# MEM_MUX_2W_1.net
KiCad netlist of a schematic drawn in EAGLE
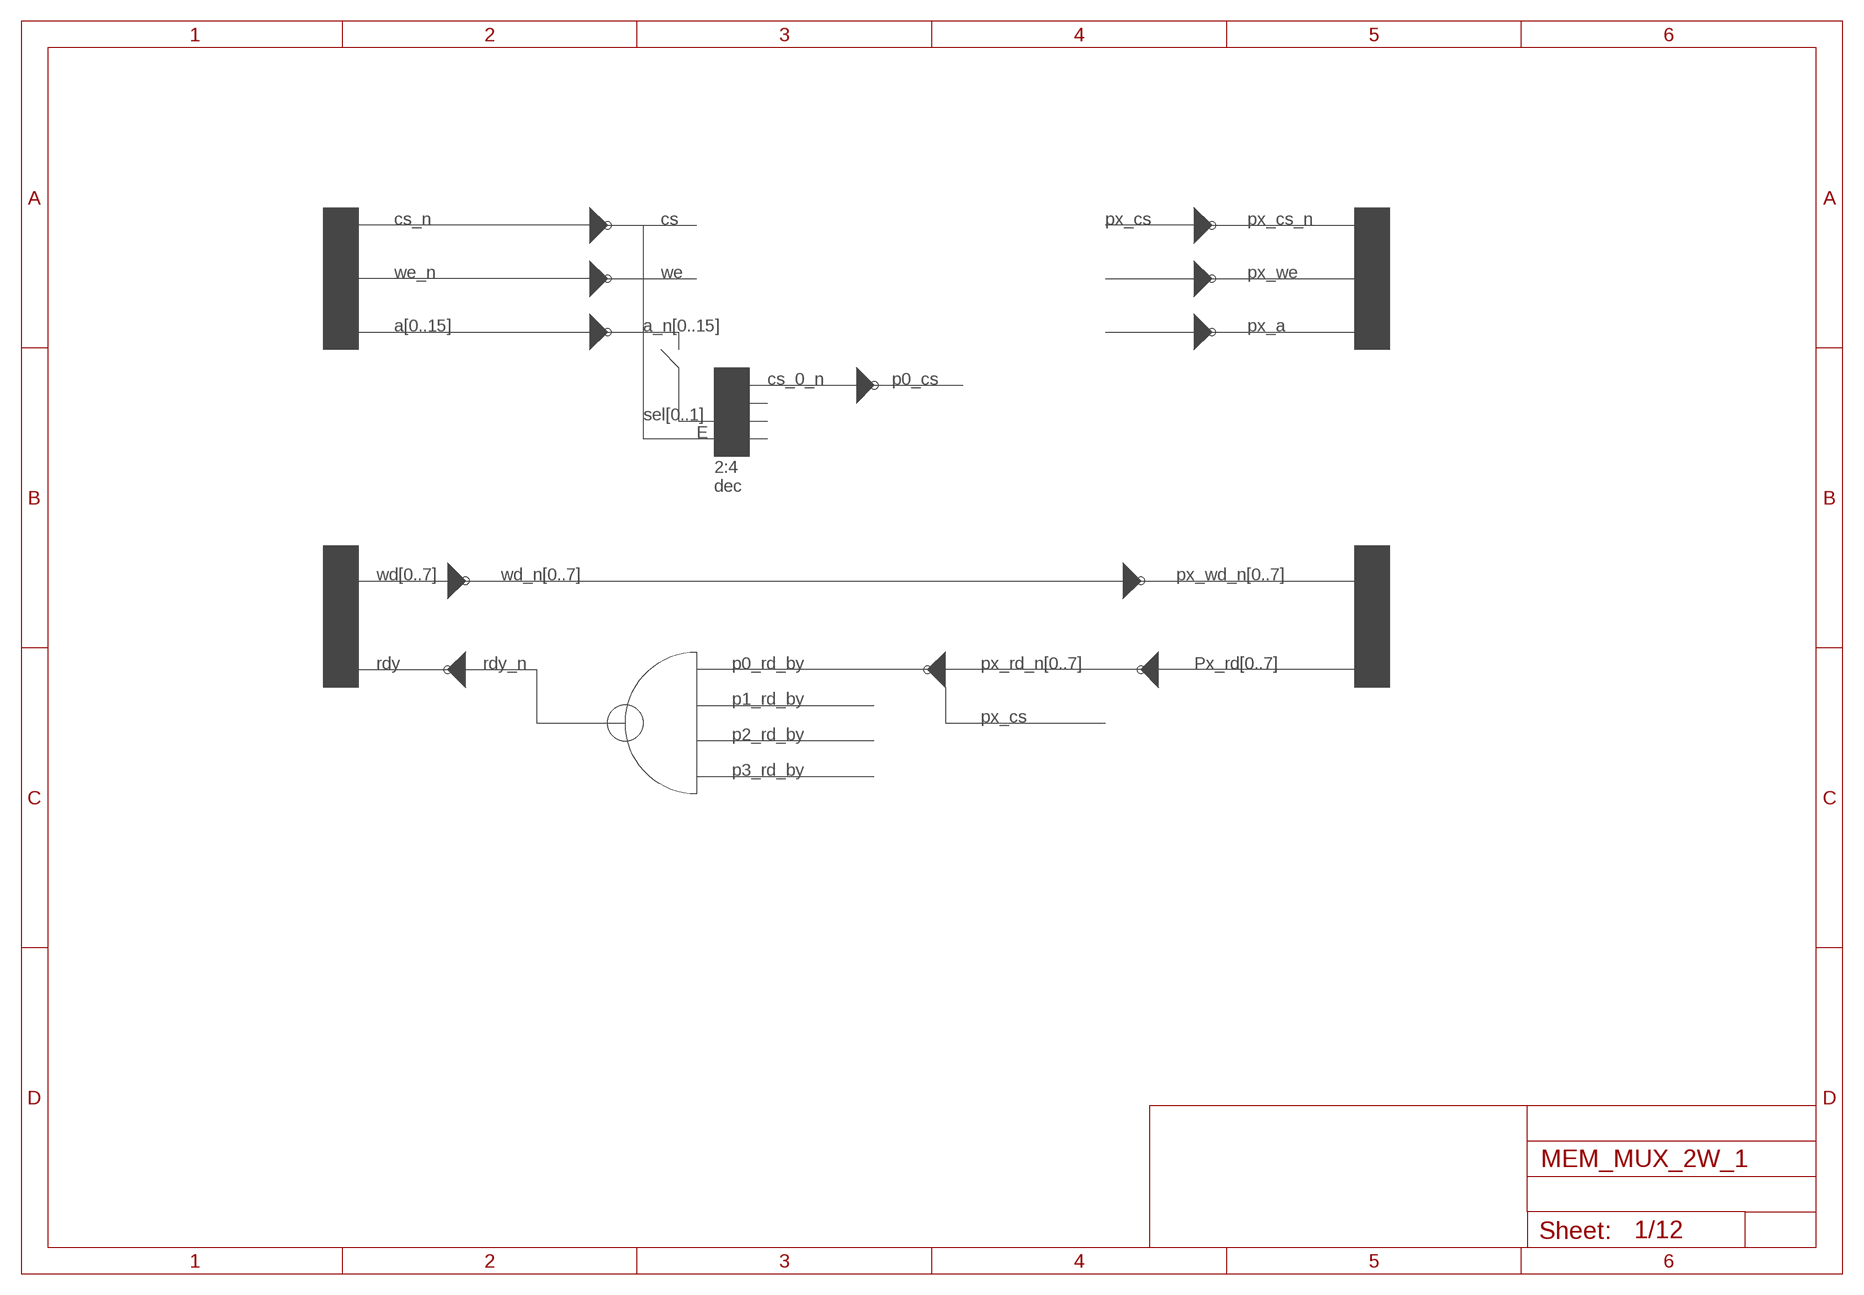
[diagram p0: schematic, sheet 1]
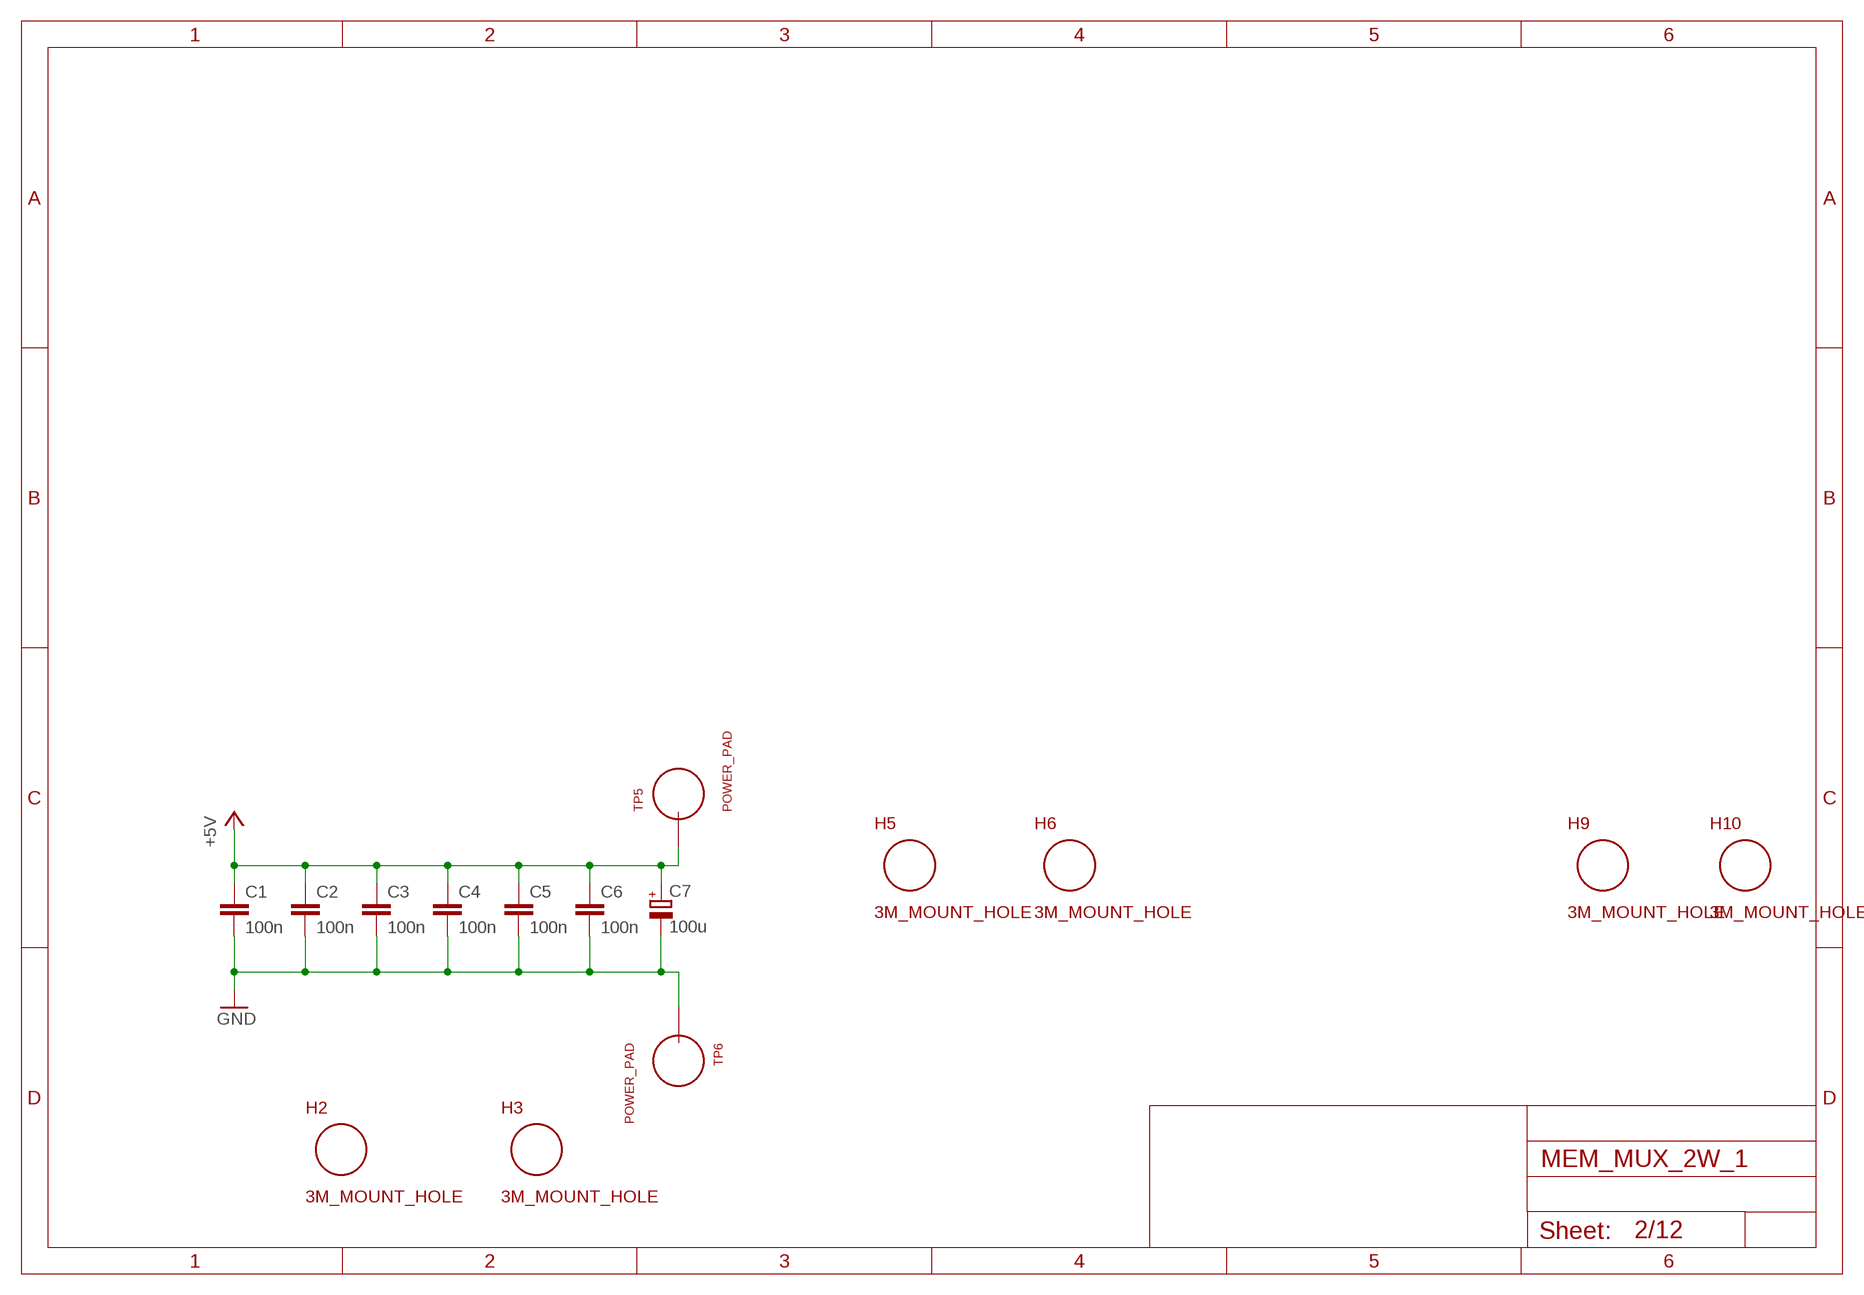
[diagram p1: schematic, sheet 2]
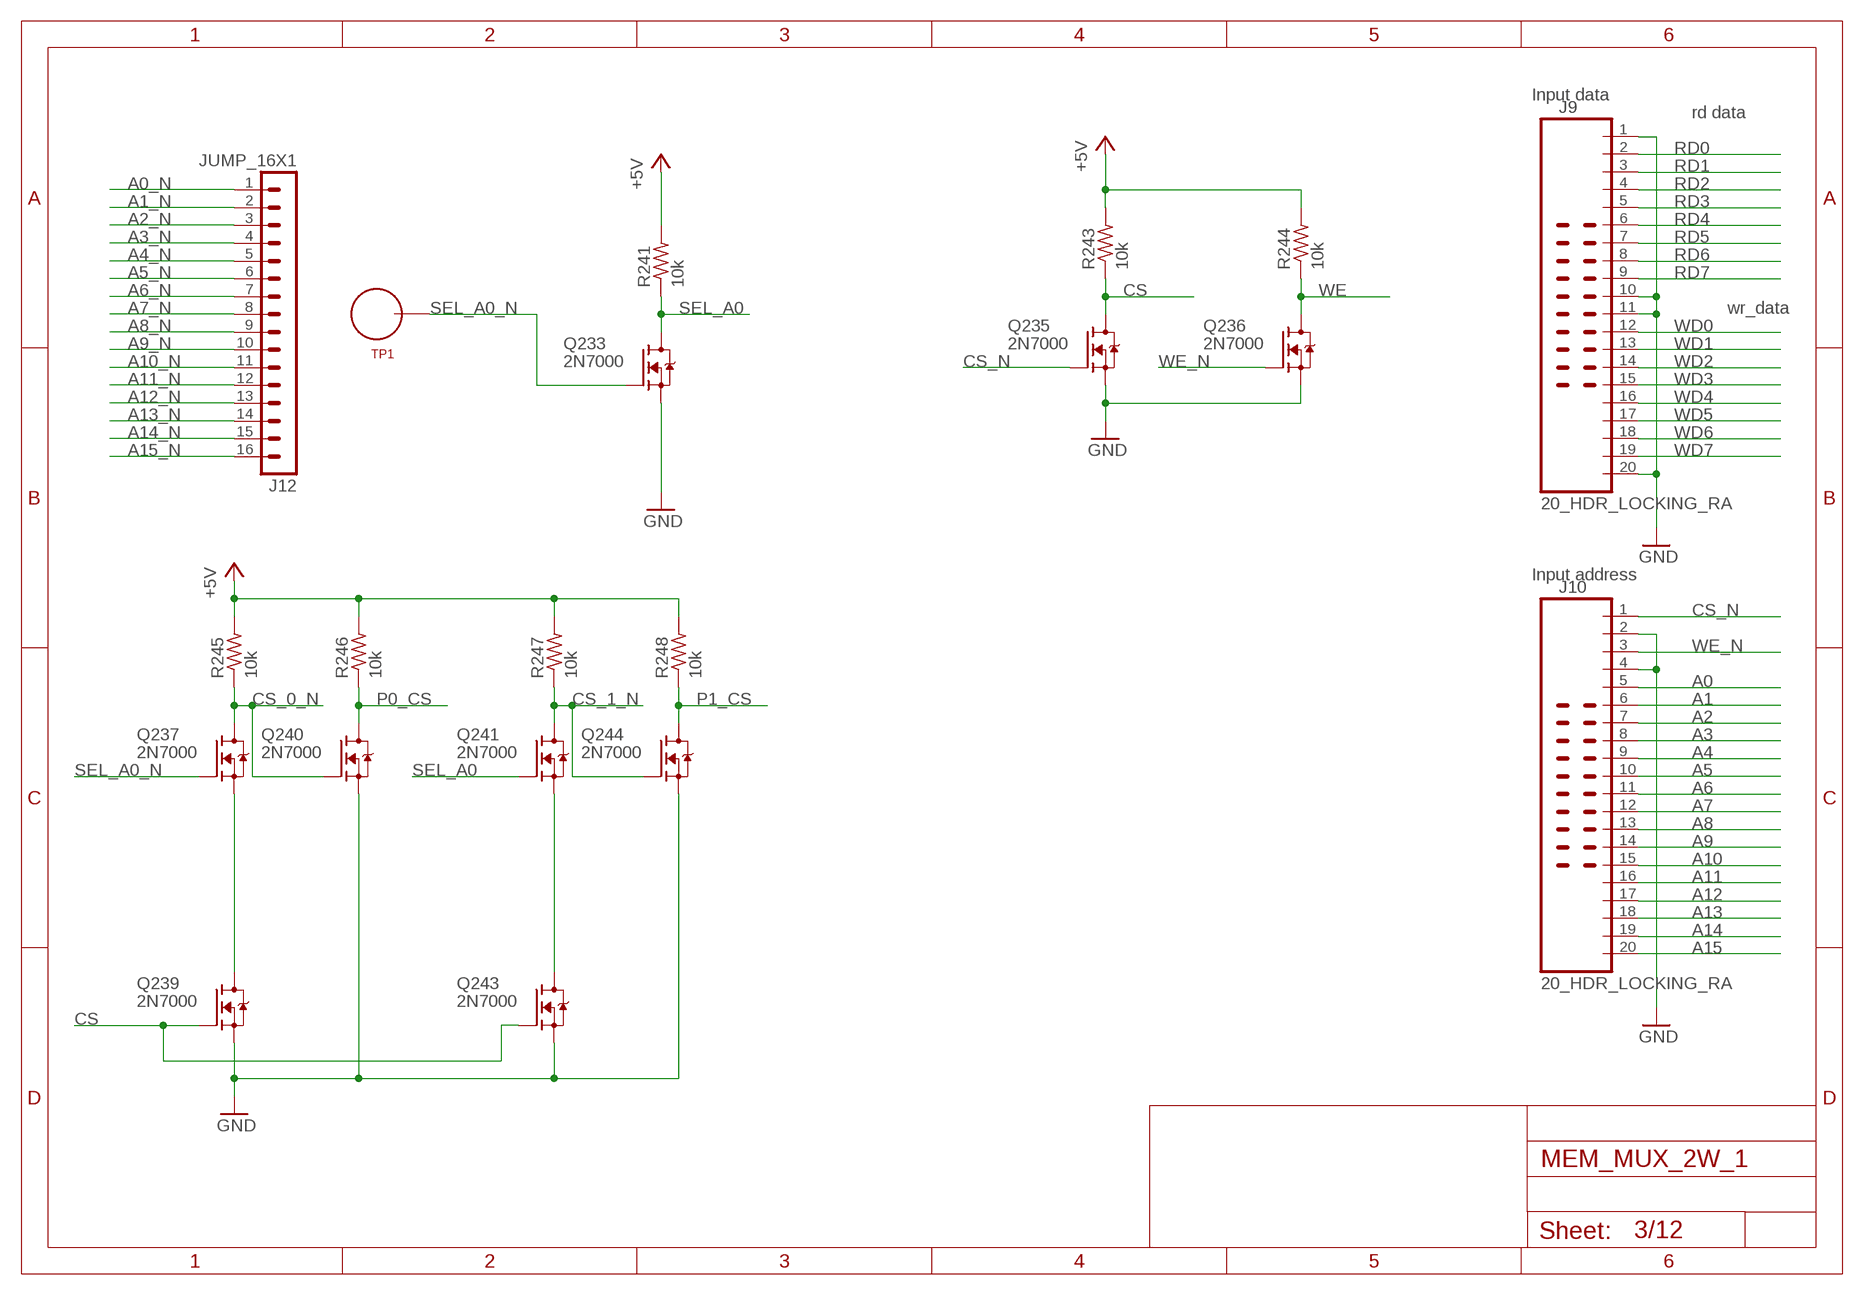
[diagram p2: schematic, sheet 3]
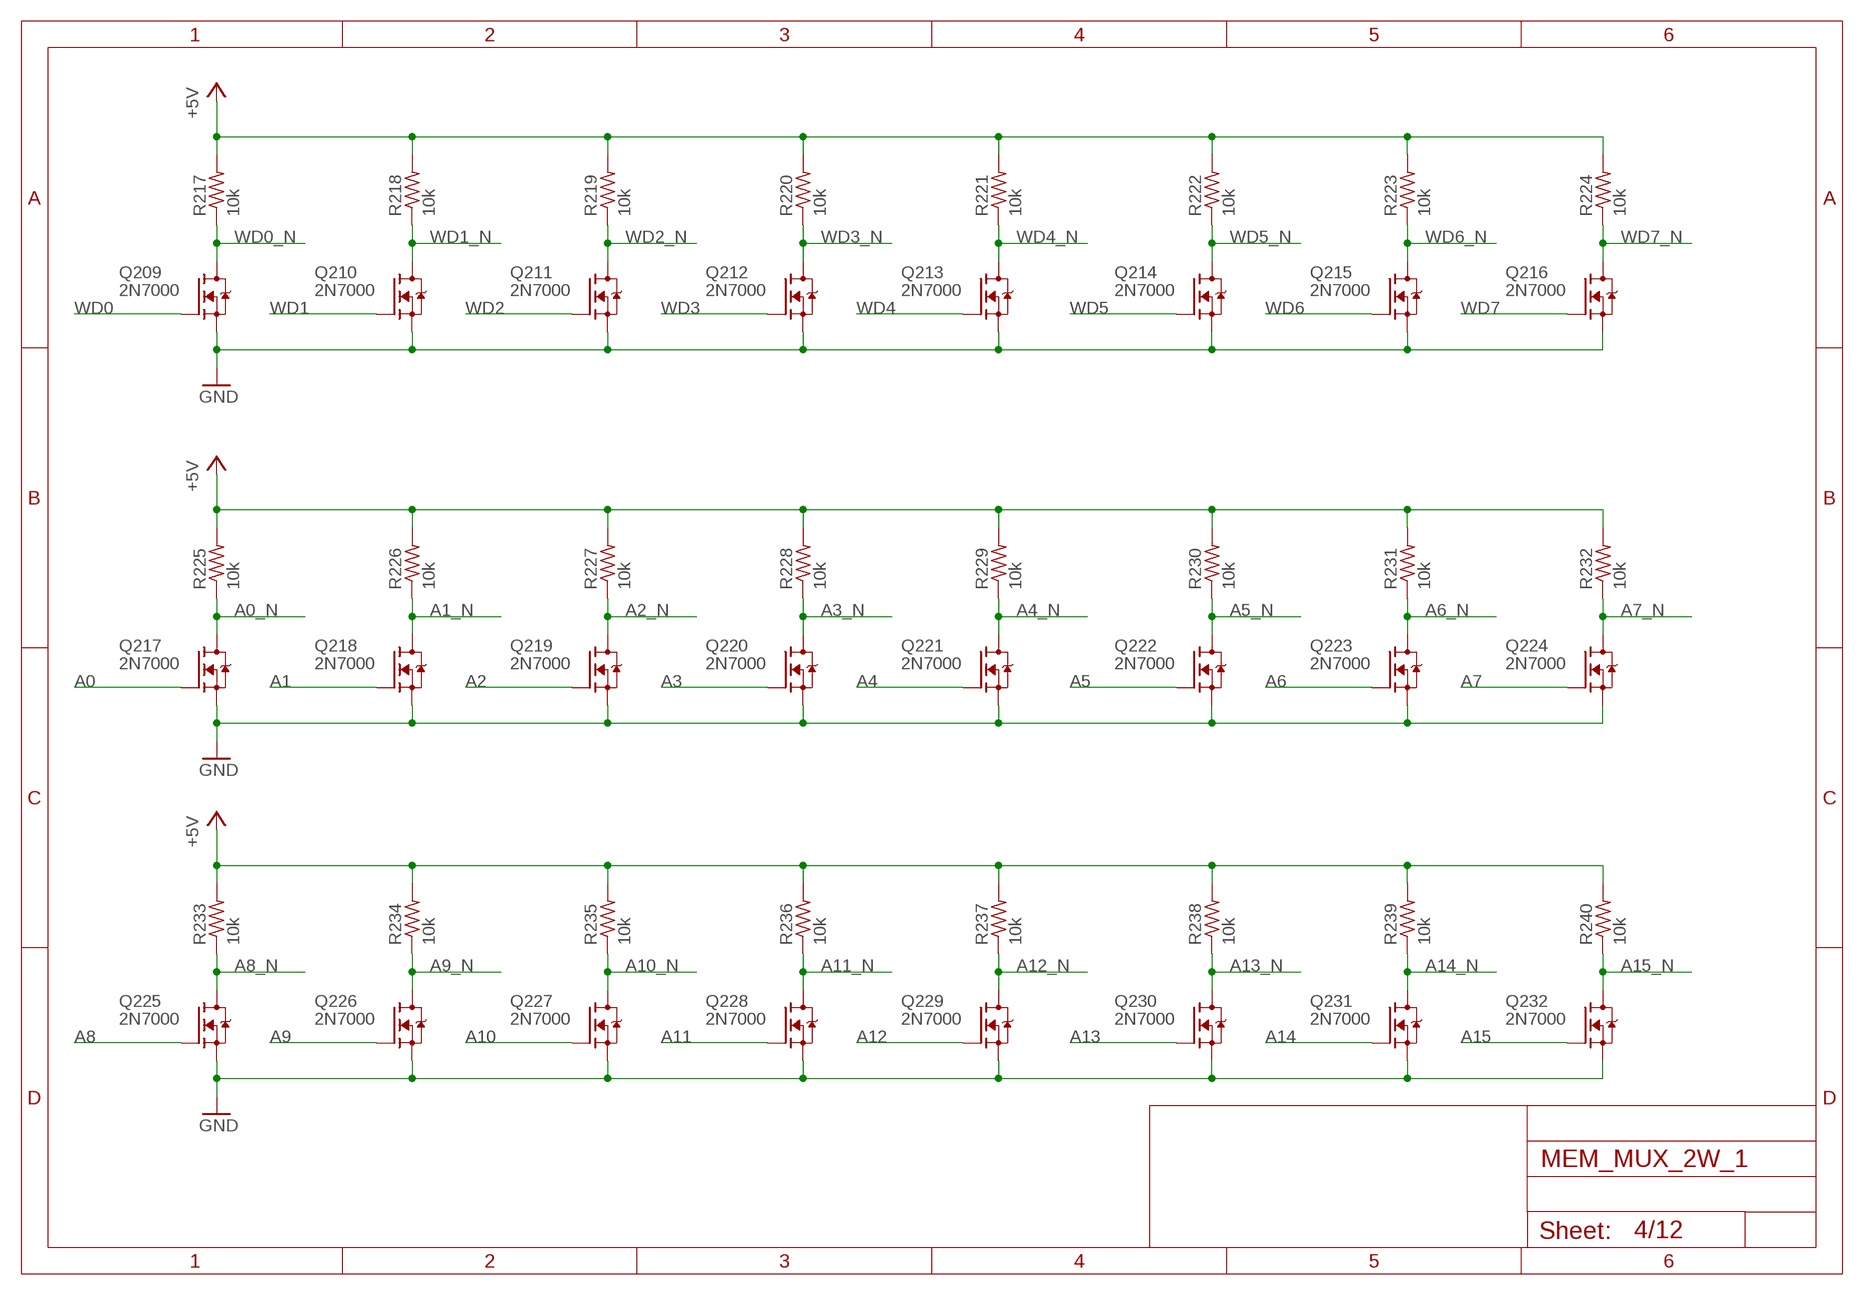
[diagram p3: schematic, sheet 4]
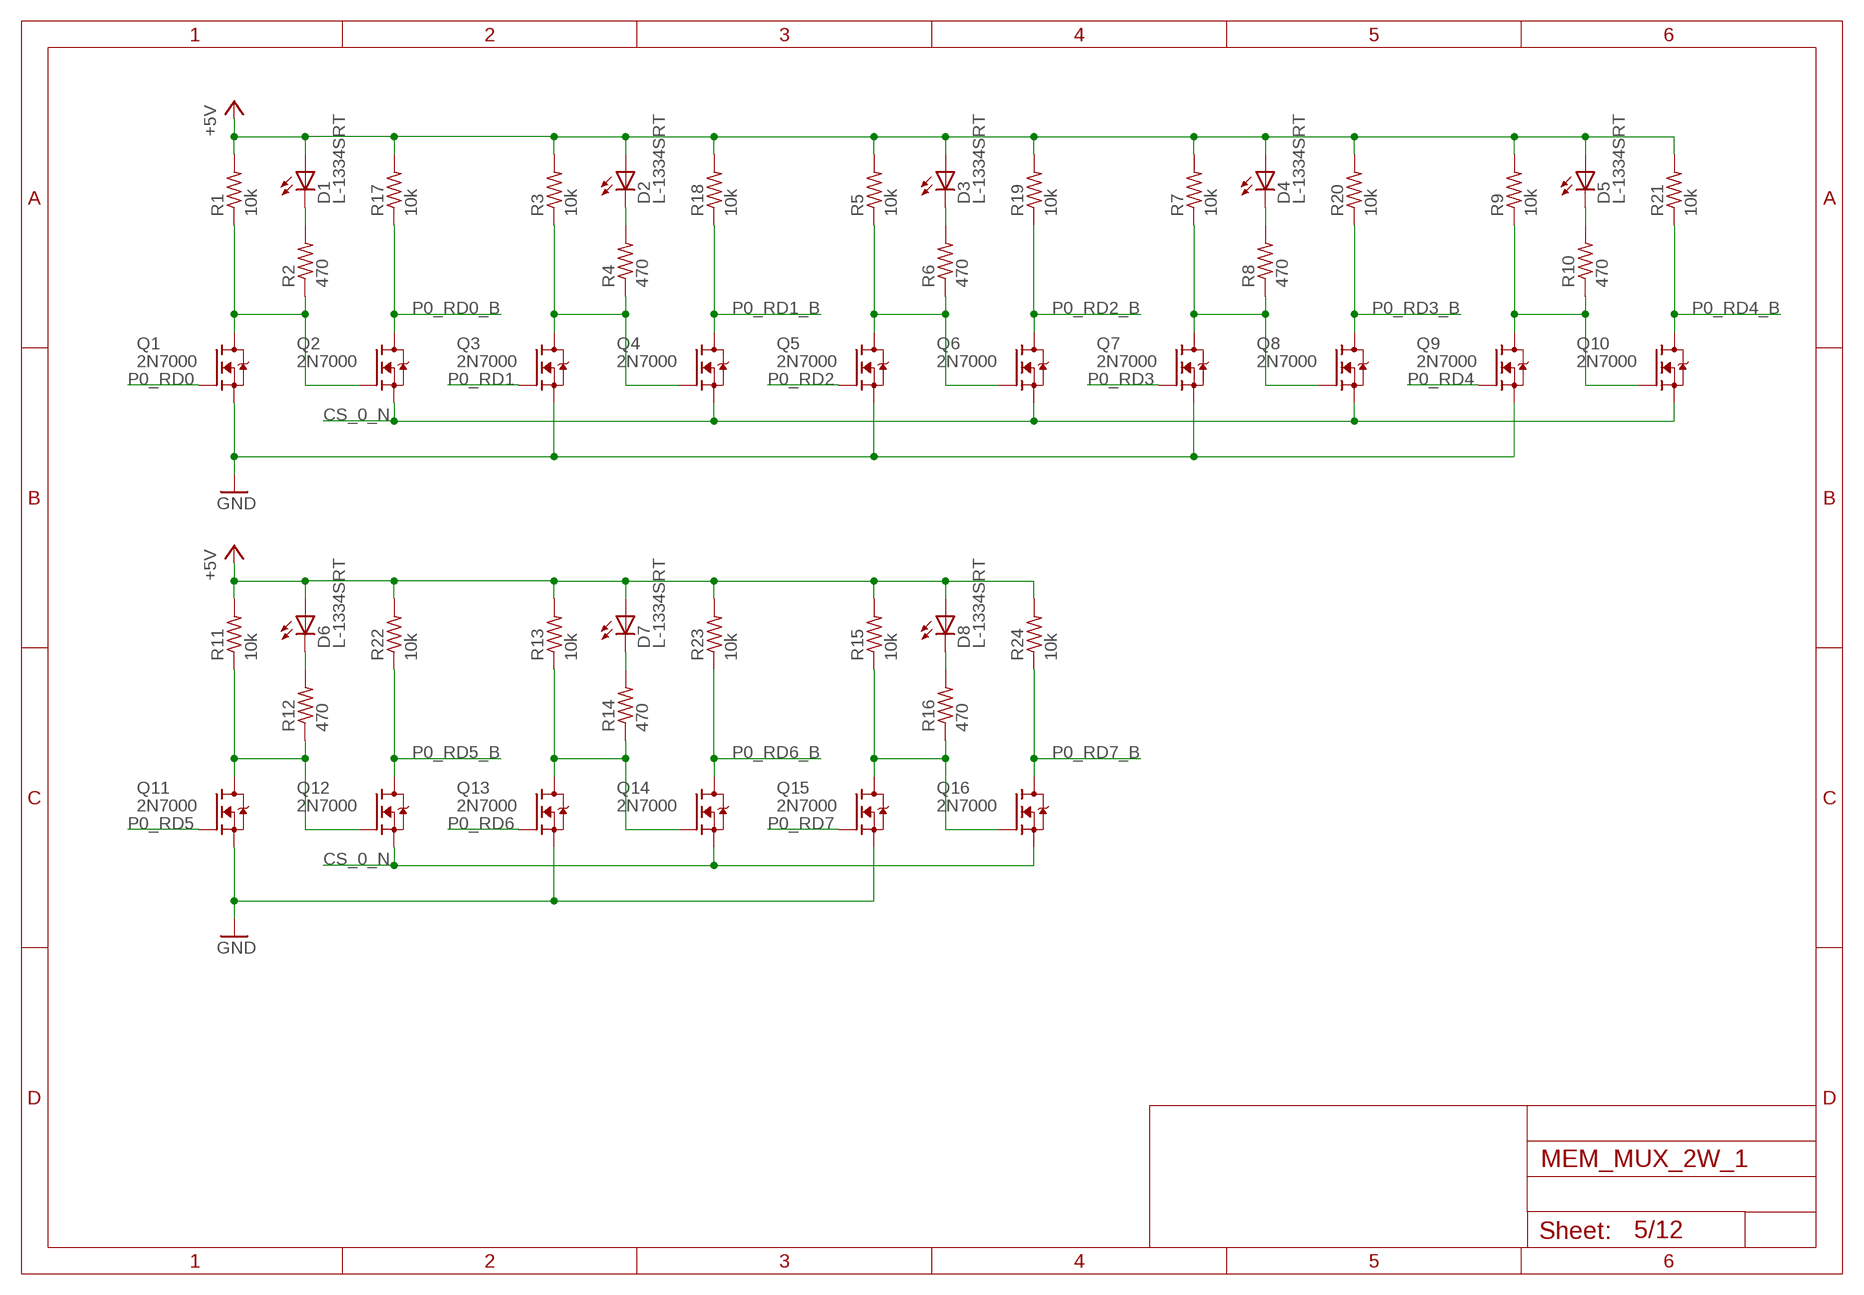
[diagram p4: schematic, sheet 5]
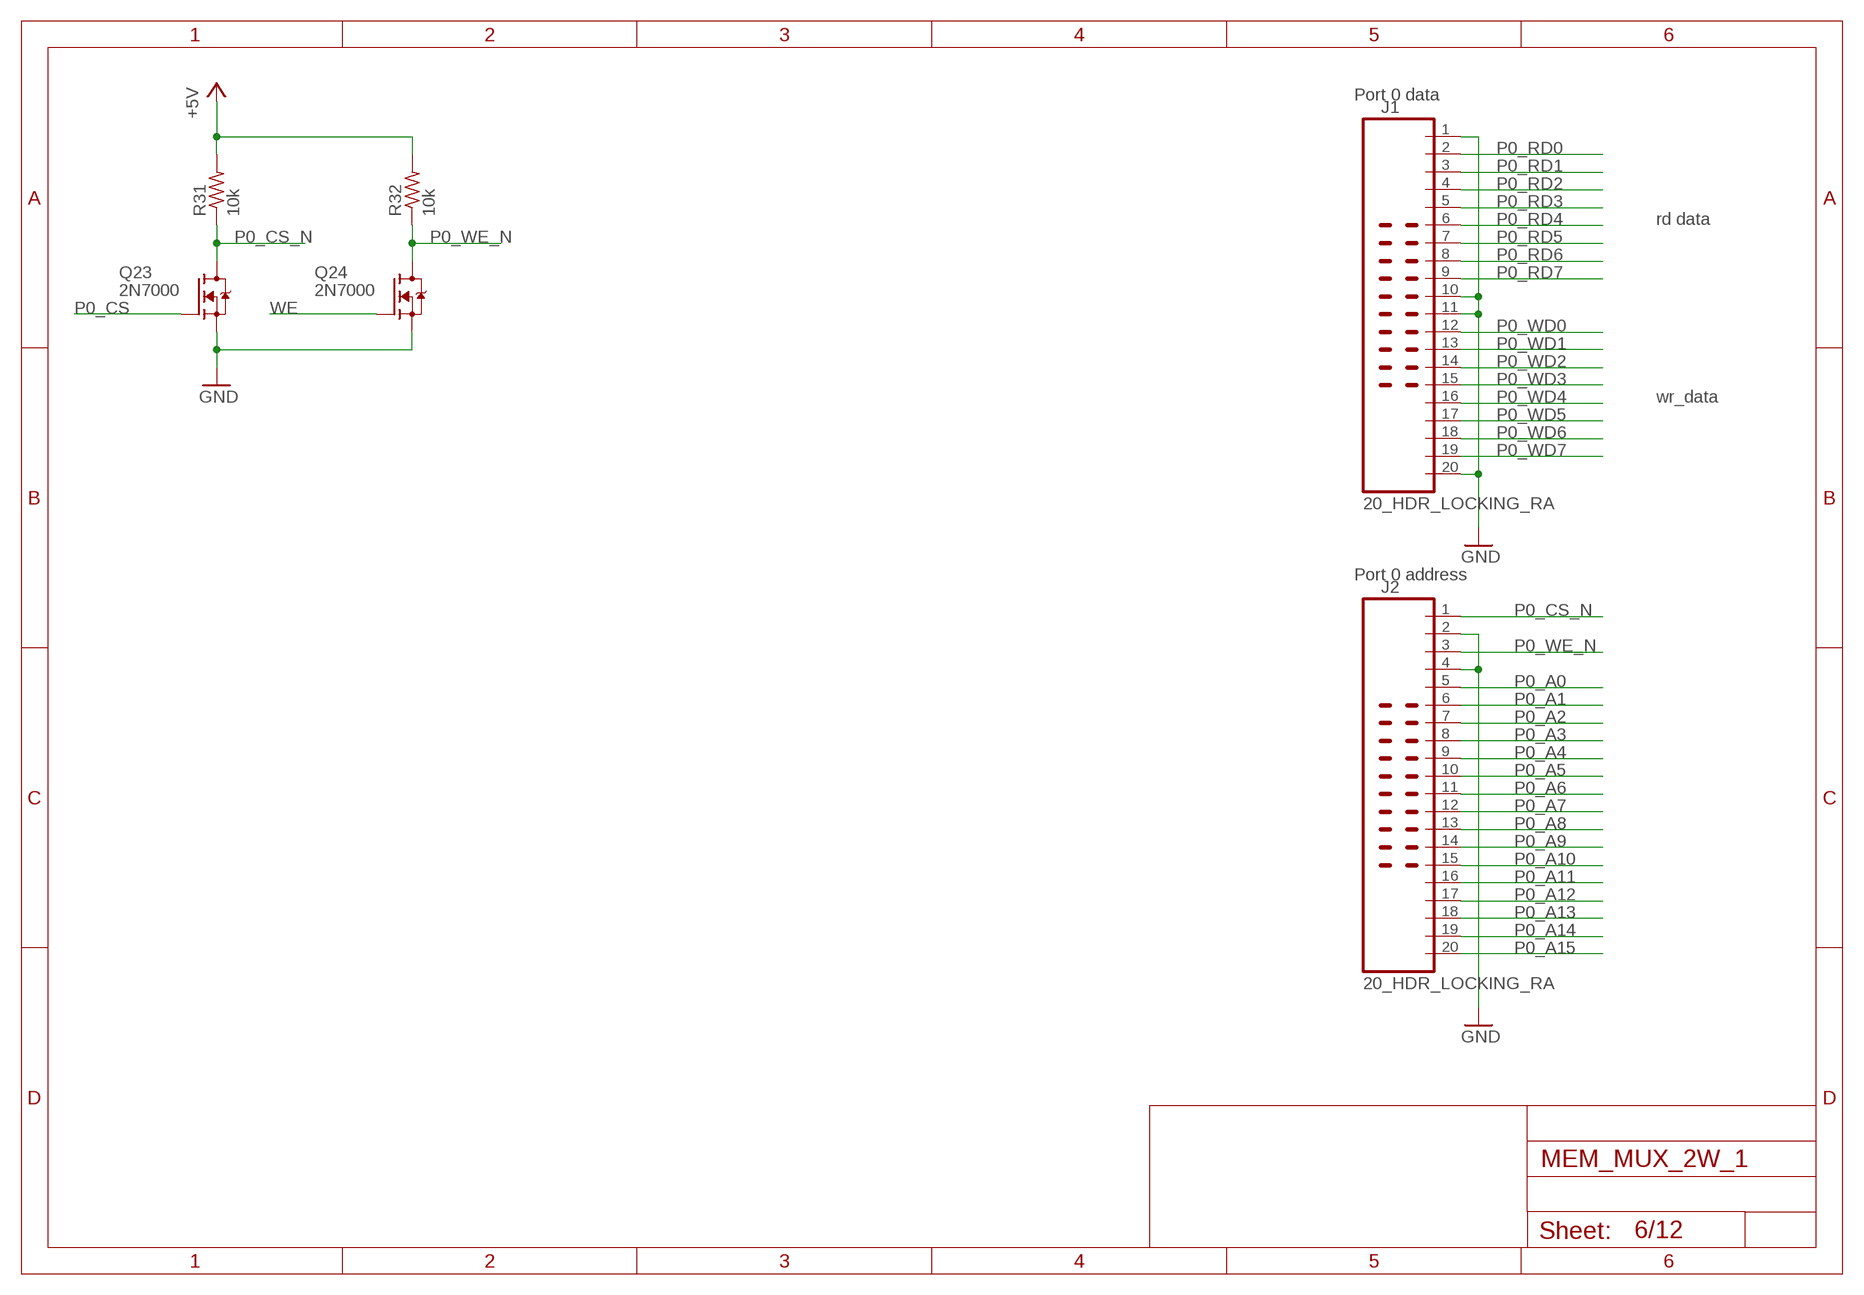
[diagram p5: schematic, sheet 6]
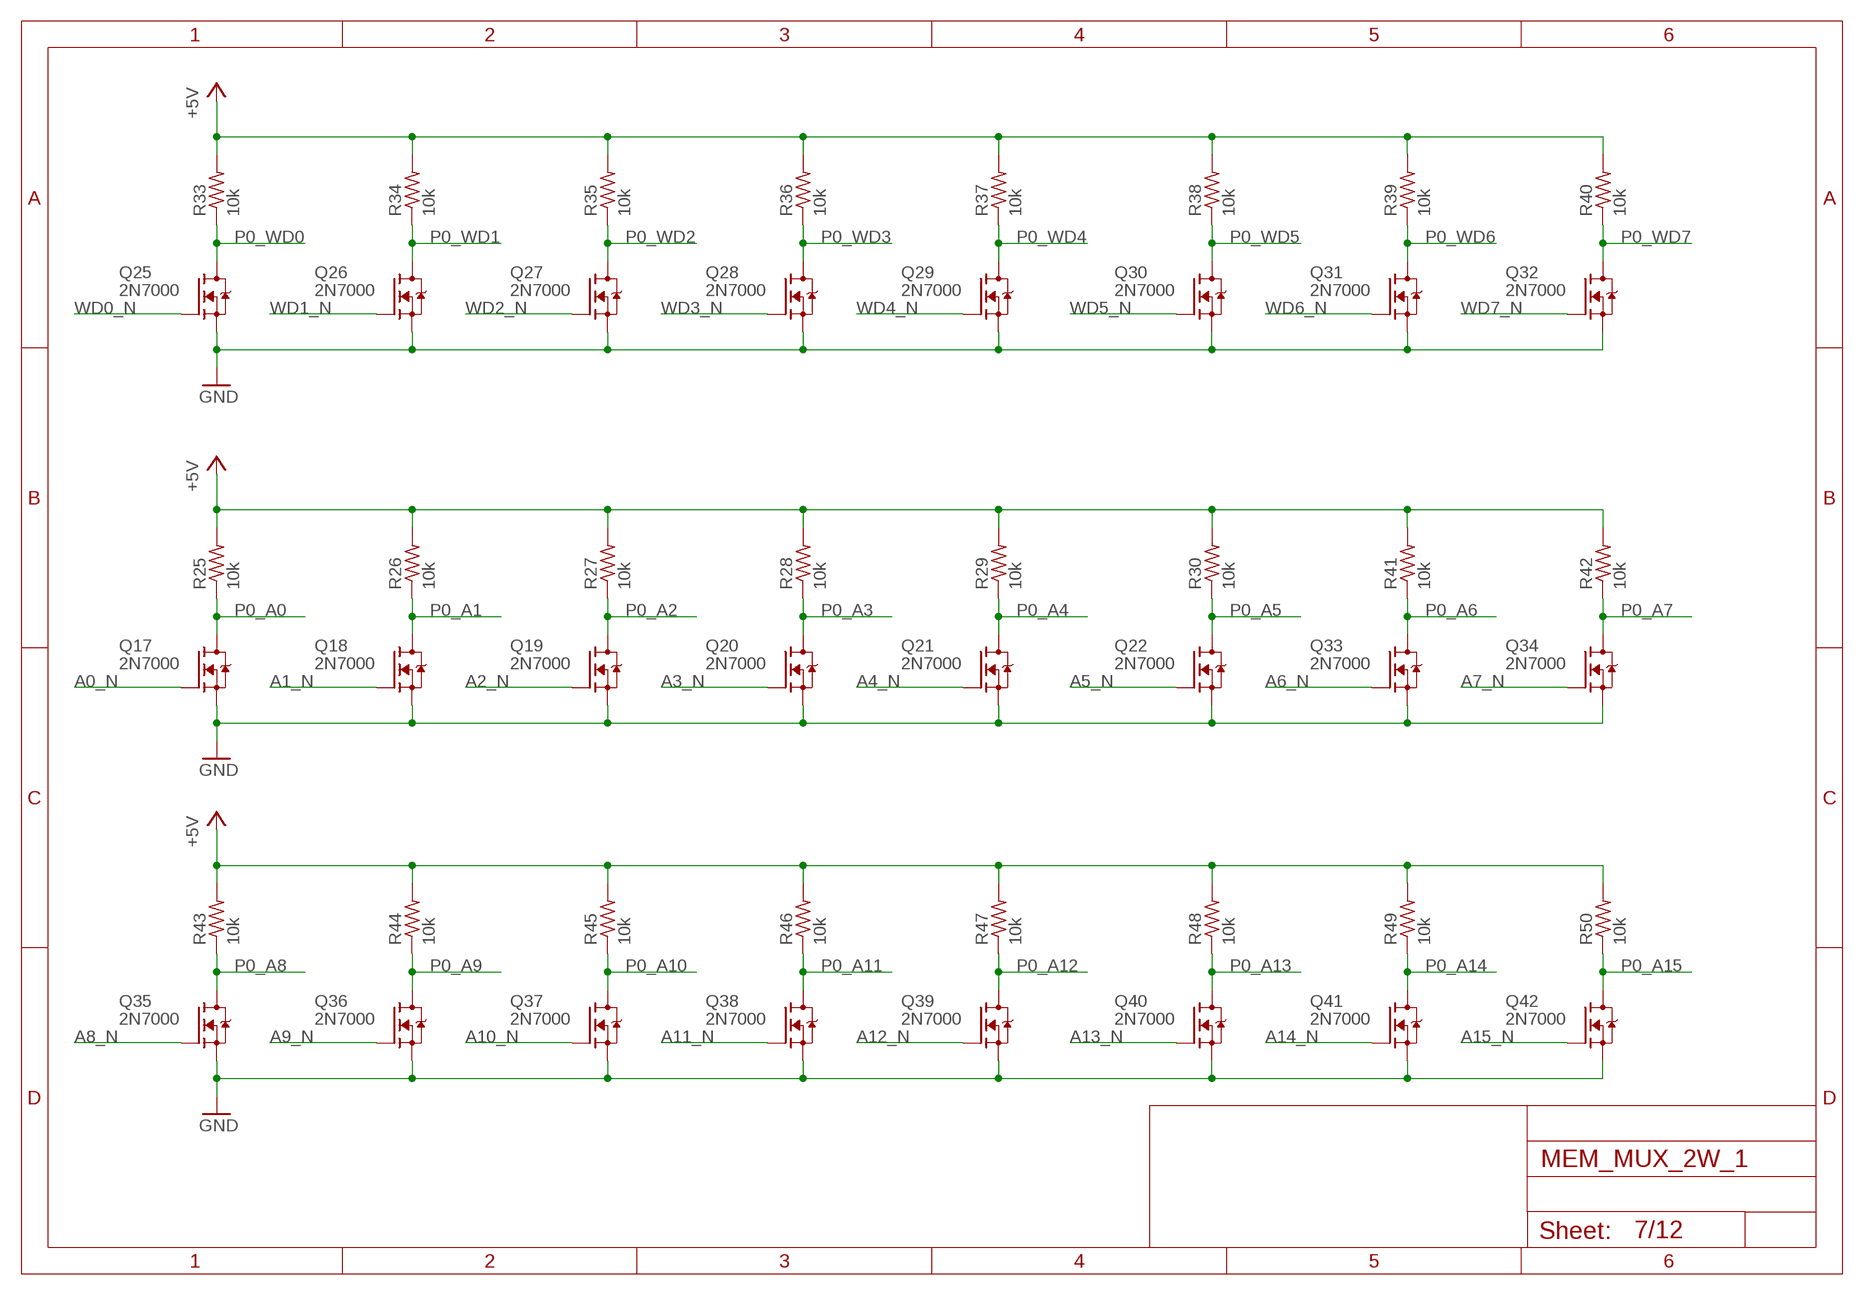
[diagram p6: schematic, sheet 7]
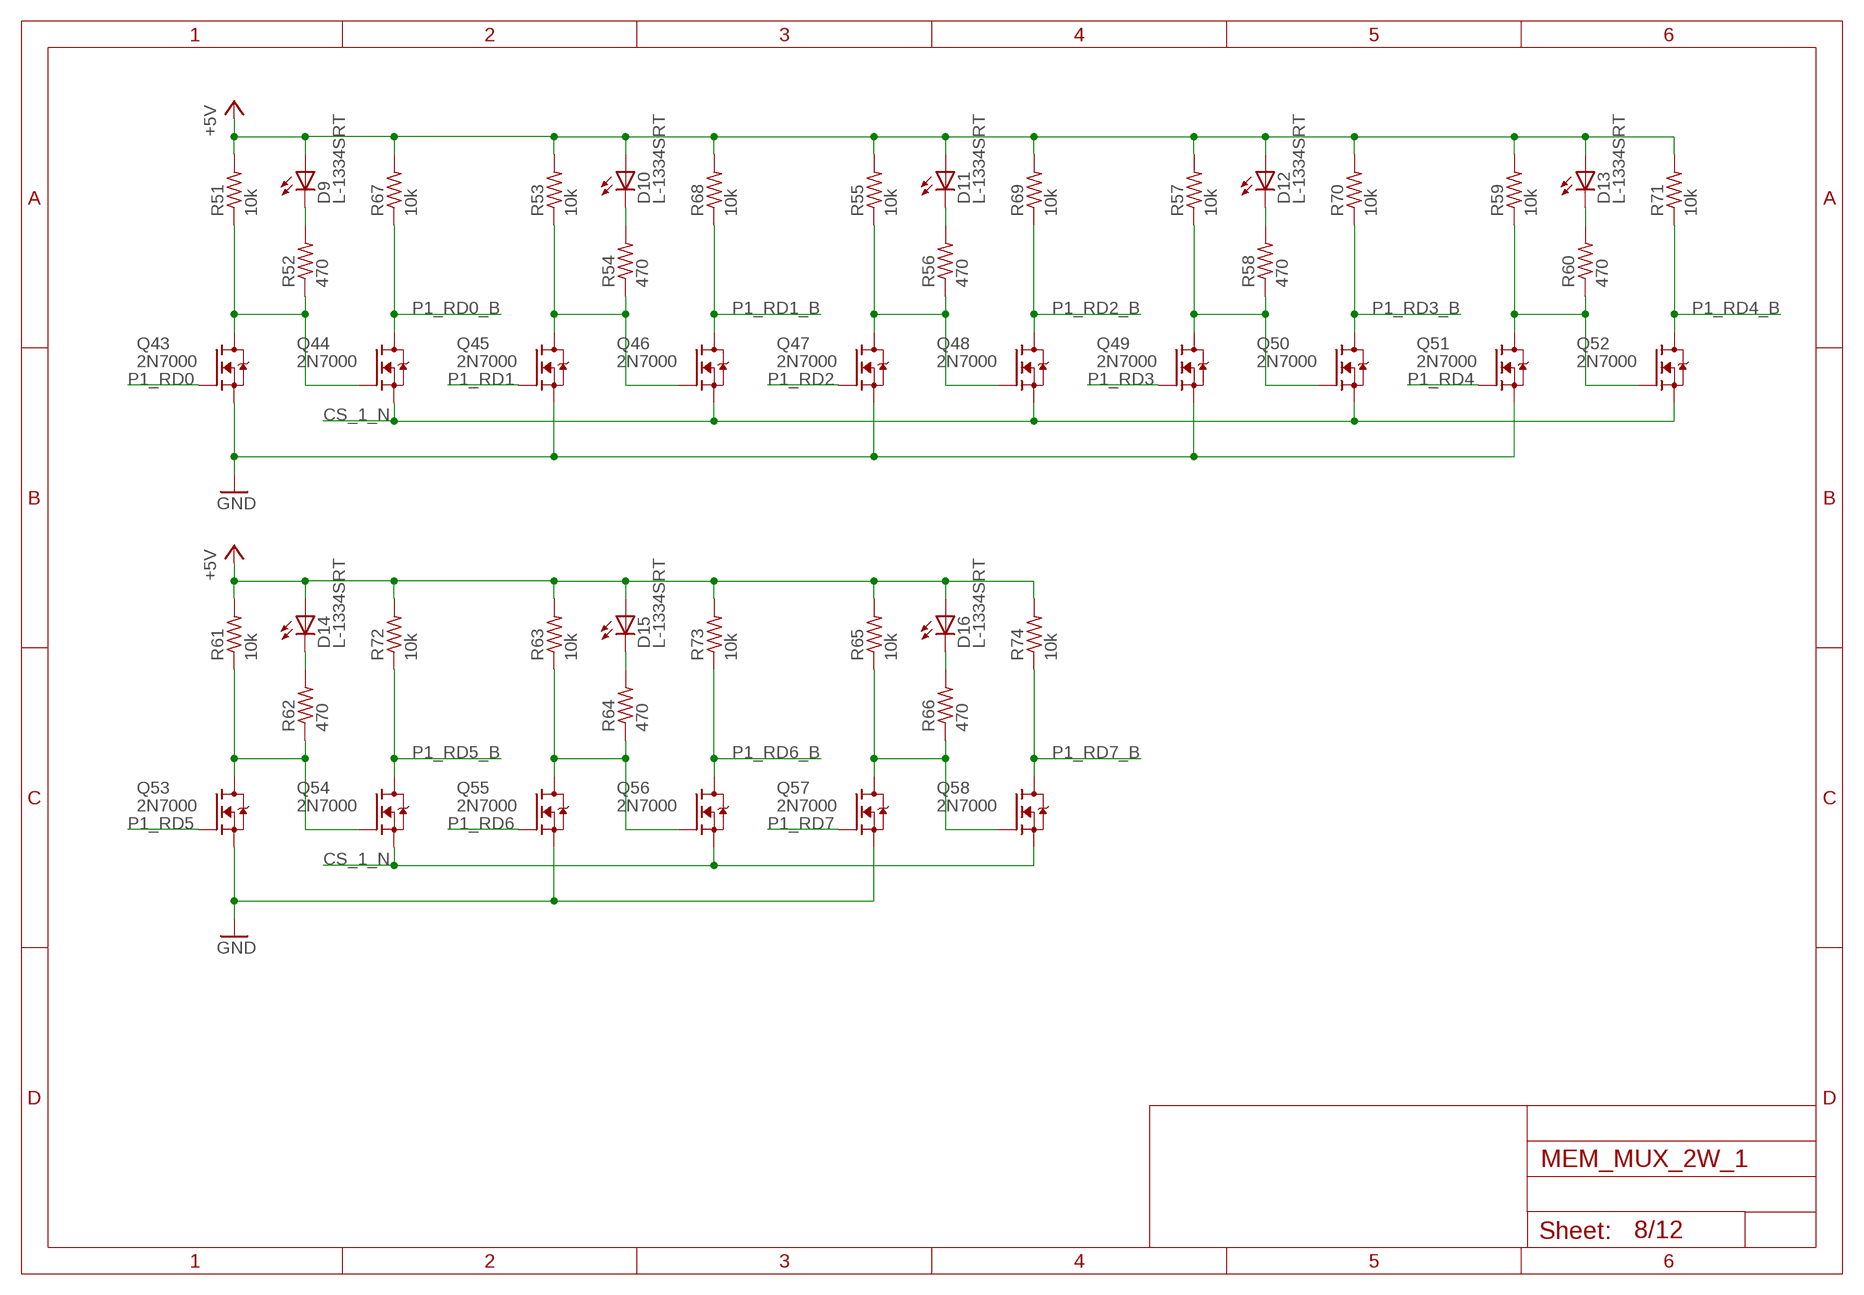
[diagram p7: schematic, sheet 8]
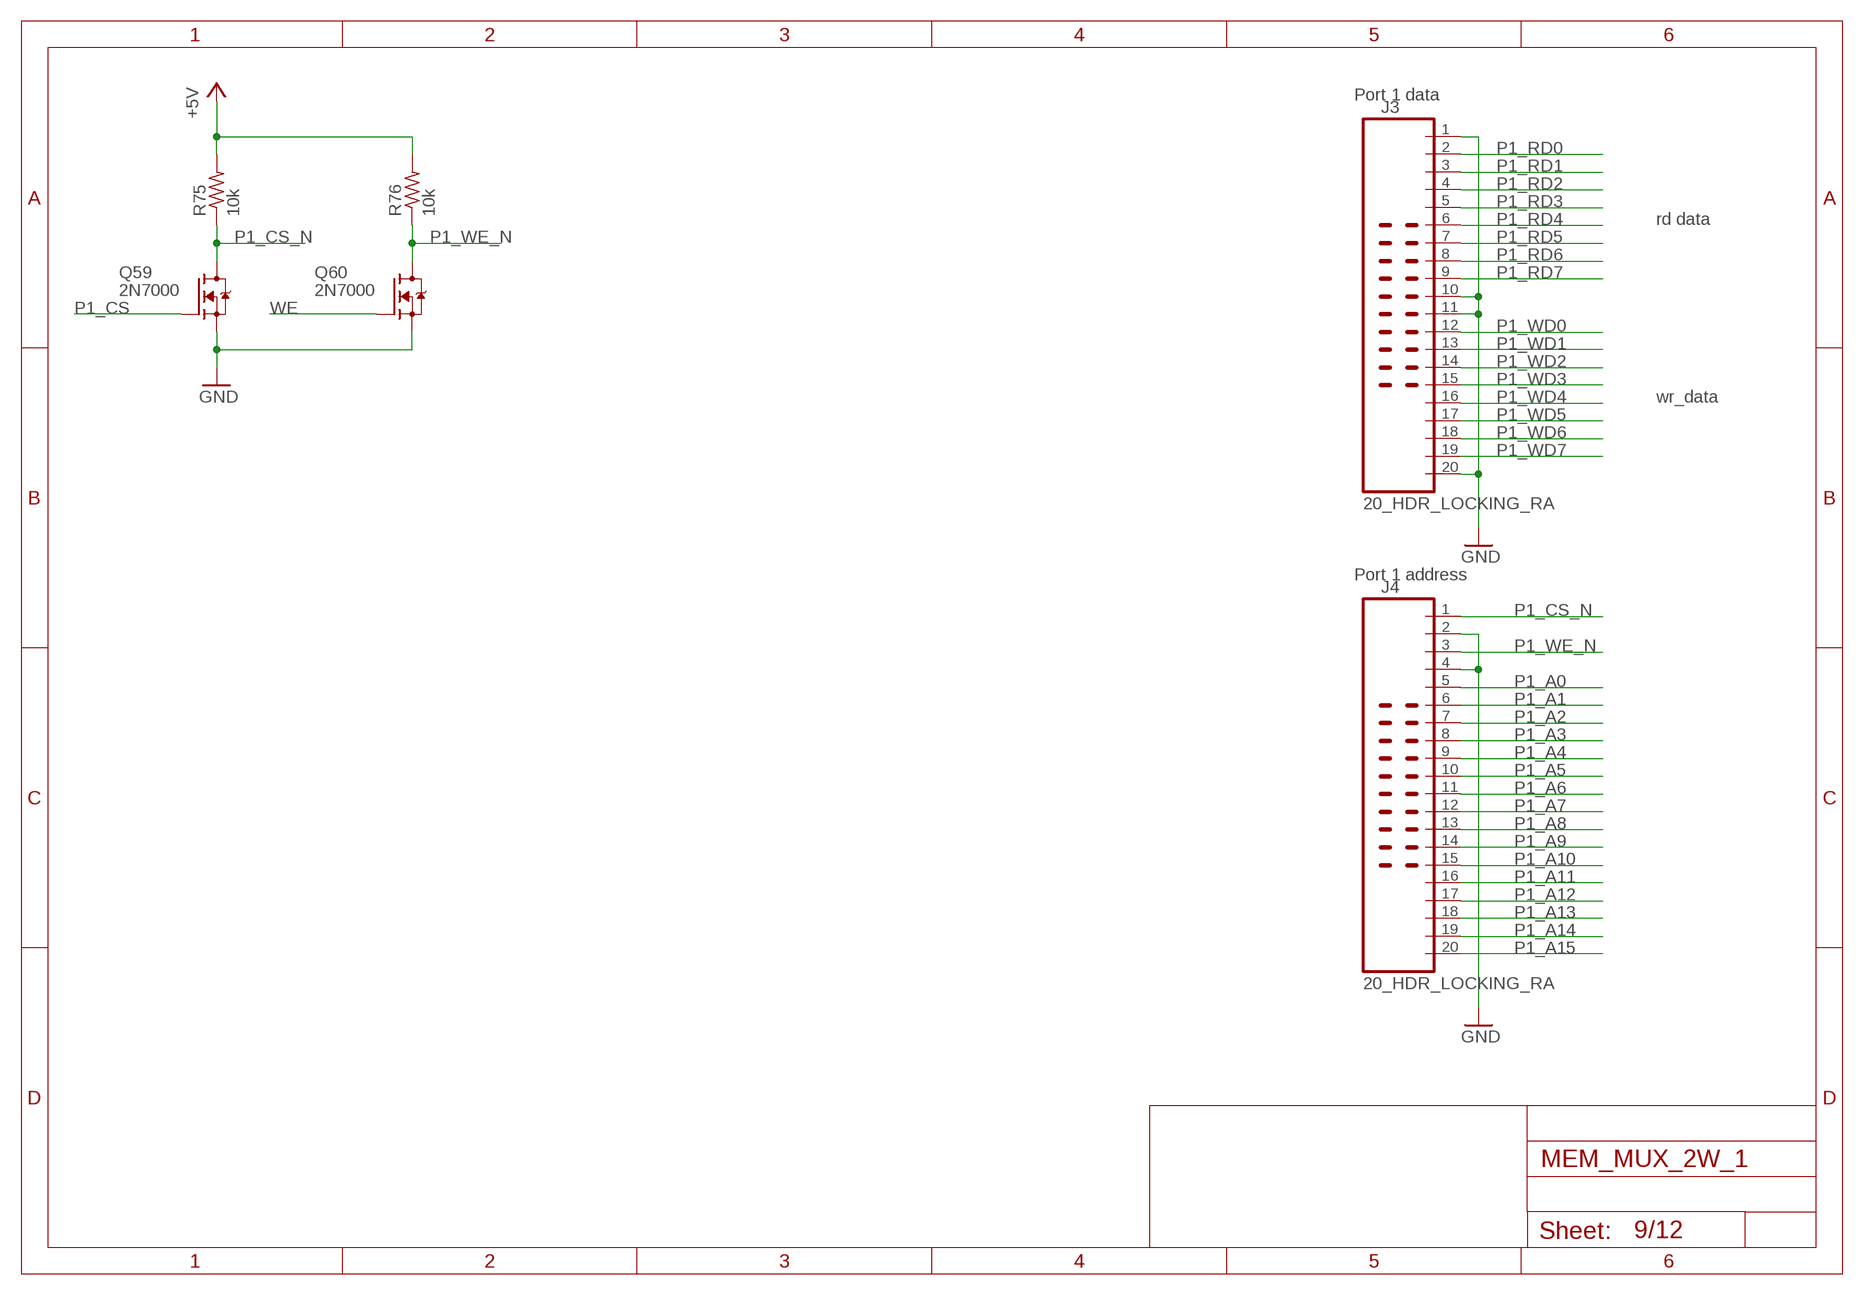
[diagram p8: schematic, sheet 9]
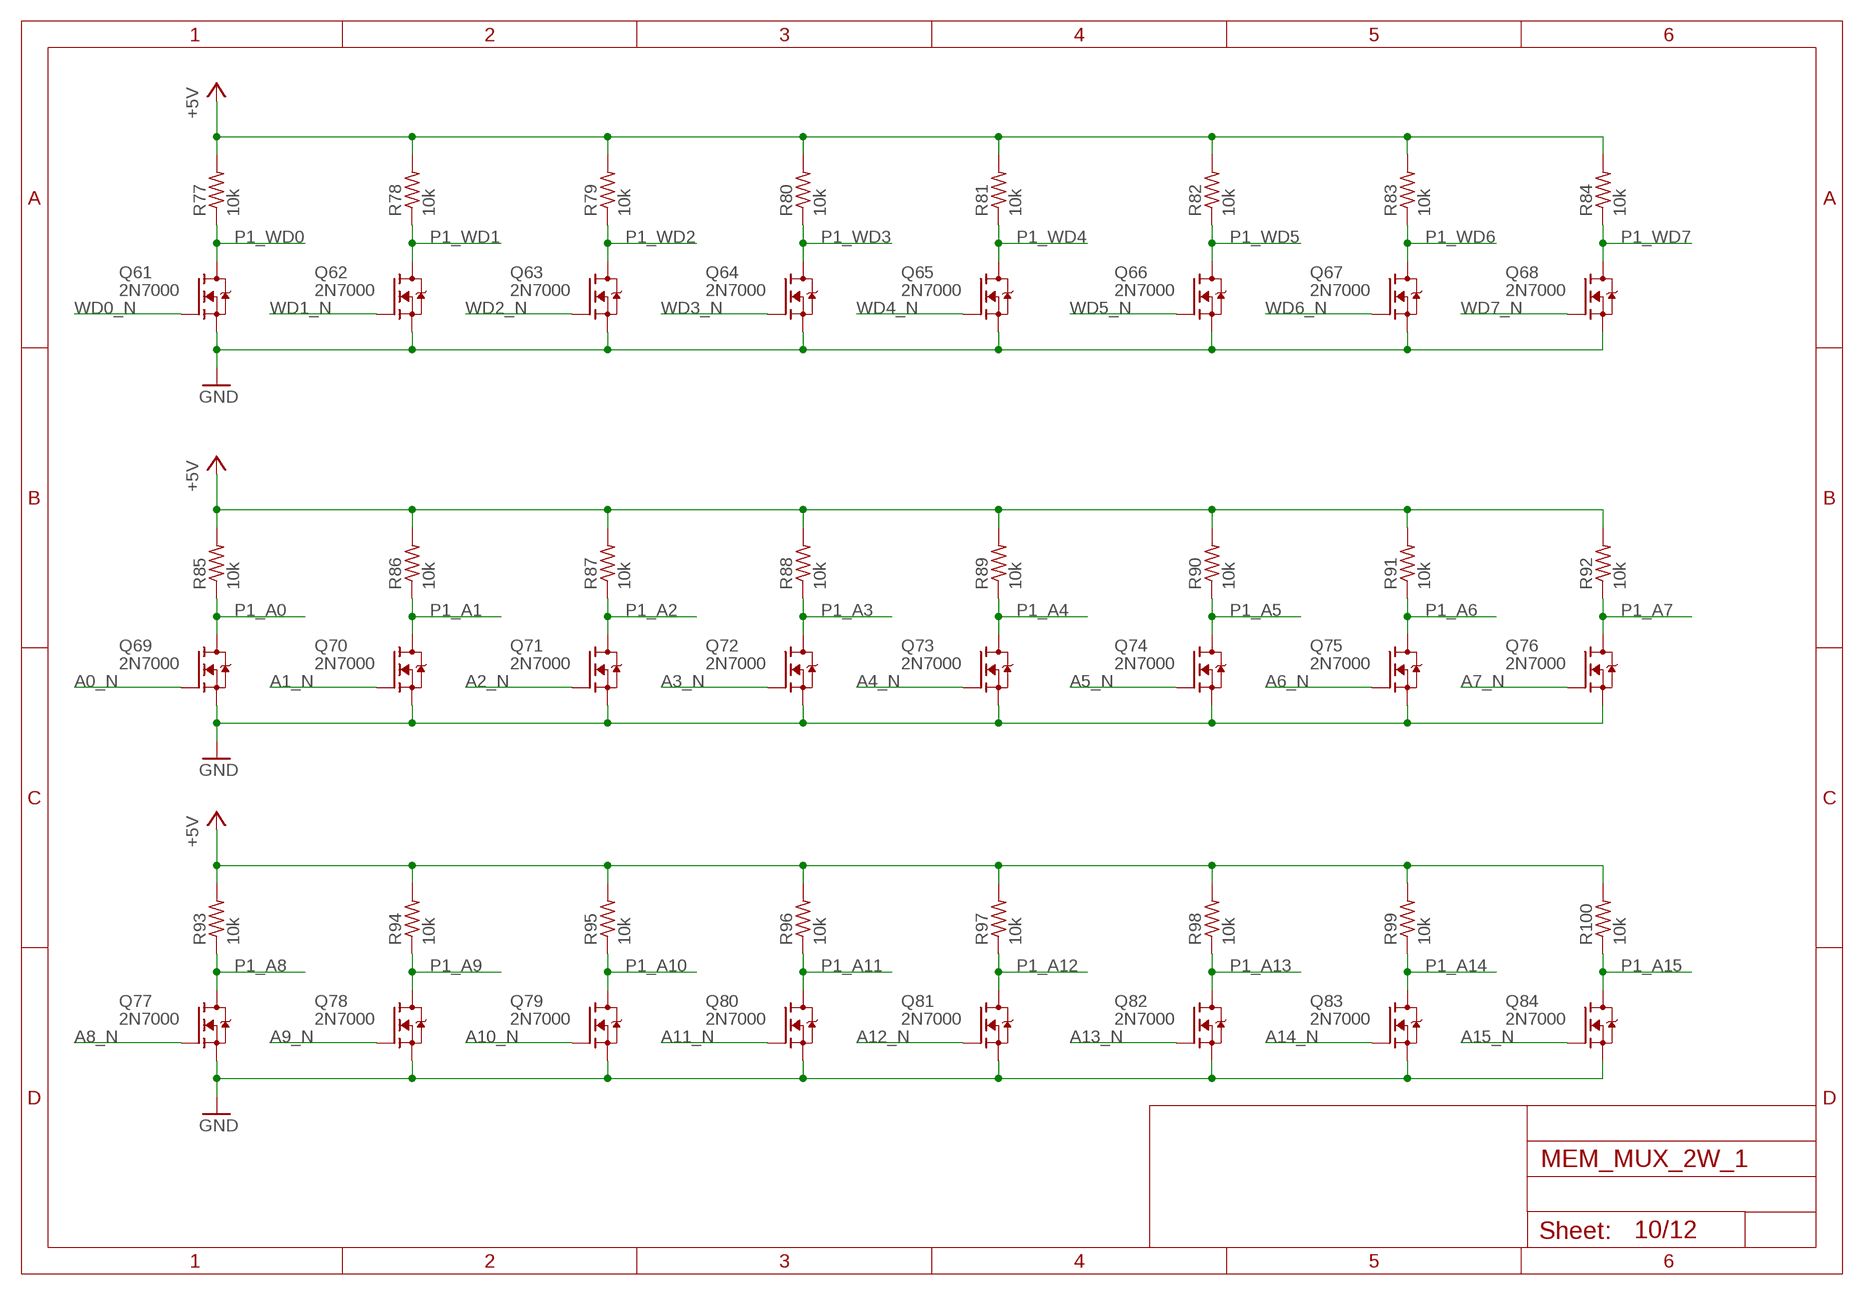
[diagram p9: schematic, sheet 10]
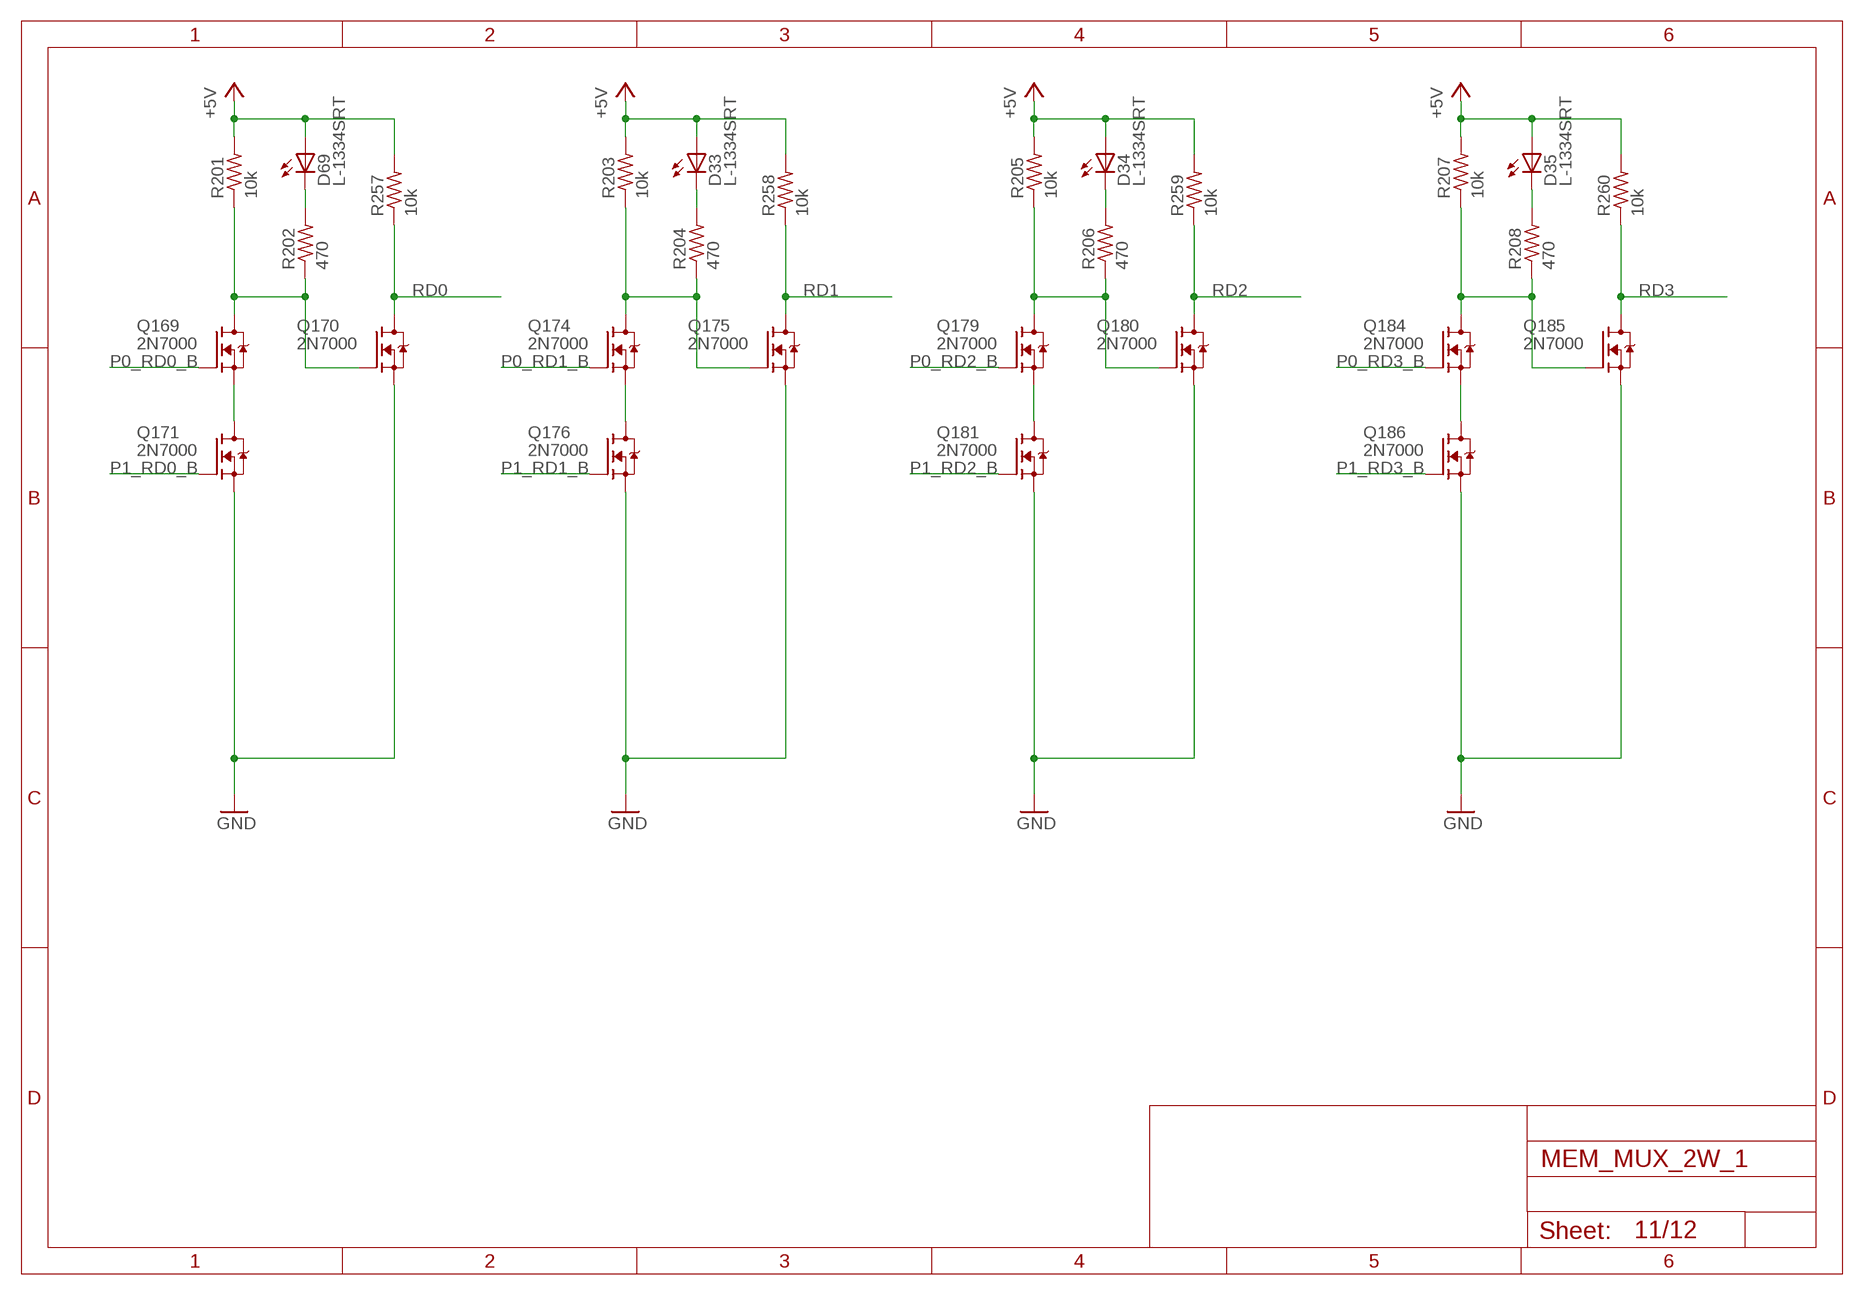
[diagram p10: schematic, sheet 11]
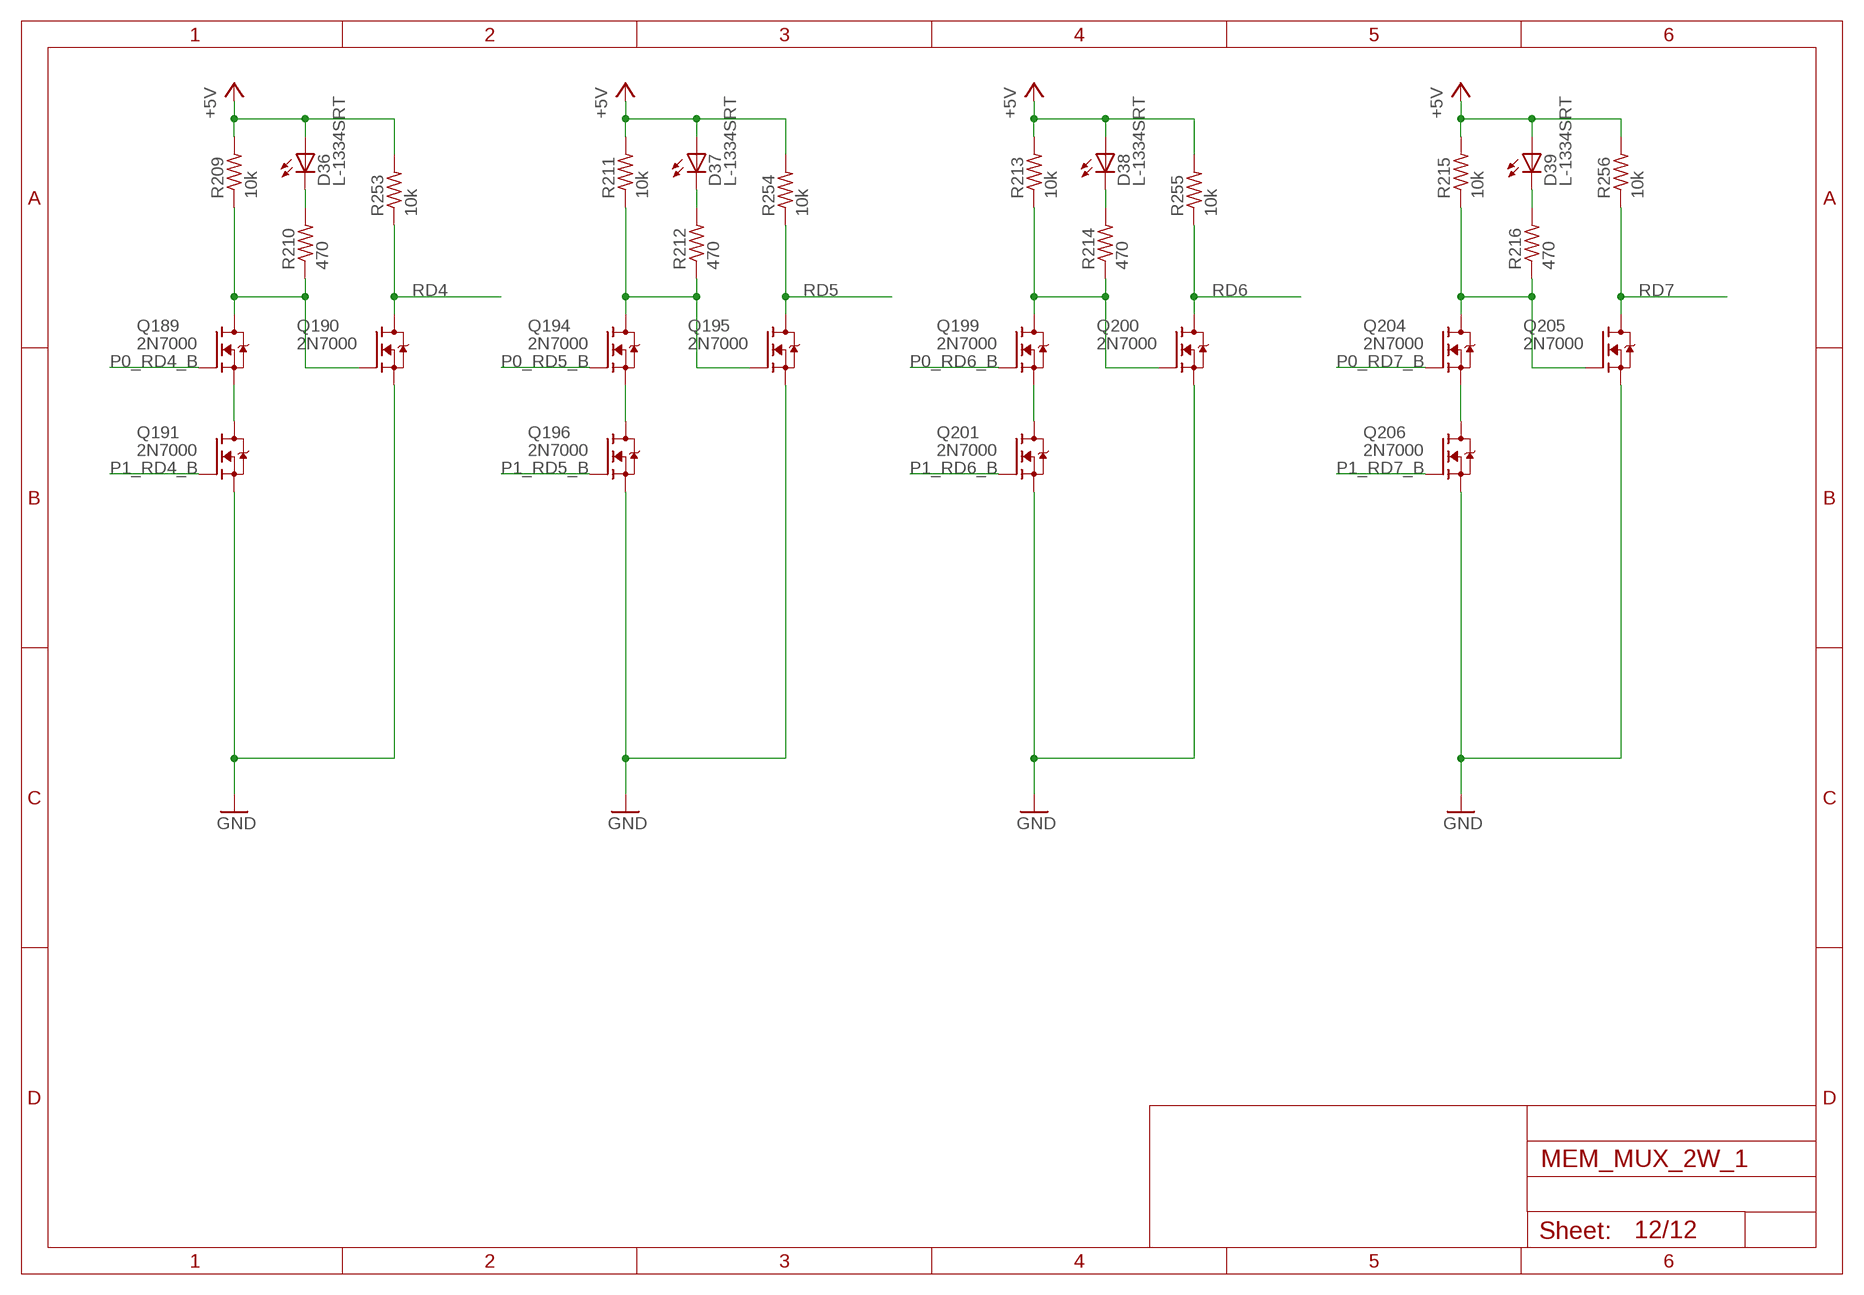
[diagram p11: schematic, sheet 12]

(export (version "E")
  (design (tool "Eeschema 10.0.6"))
  (components
    (comp (ref "Q61")
      (value "2N7000")
      (footprint "eagle-import:TO92-DGS")
      (libsource (lib "eagle-import") (part "2N7000"))
    )
    (comp (ref "Q62")
      (value "2N7000")
      (footprint "eagle-import:TO92-DGS")
      (libsource (lib "eagle-import") (part "2N7000"))
    )
    (comp (ref "Q63")
      (value "2N7000")
      (footprint "eagle-import:TO92-DGS")
      (libsource (lib "eagle-import") (part "2N7000"))
    )
    (comp (ref "Q64")
      (value "2N7000")
      (footprint "eagle-import:TO92-DGS")
      (libsource (lib "eagle-import") (part "2N7000"))
    )
    (comp (ref "Q65")
      (value "2N7000")
      (footprint "eagle-import:TO92-DGS")
      (libsource (lib "eagle-import") (part "2N7000"))
    )
    (comp (ref "Q66")
      (value "2N7000")
      (footprint "eagle-import:TO92-DGS")
      (libsource (lib "eagle-import") (part "2N7000"))
    )
    (comp (ref "Q67")
      (value "2N7000")
      (footprint "eagle-import:TO92-DGS")
      (libsource (lib "eagle-import") (part "2N7000"))
    )
    (comp (ref "Q68")
      (value "2N7000")
      (footprint "eagle-import:TO92-DGS")
      (libsource (lib "eagle-import") (part "2N7000"))
    )
    (comp (ref "Q69")
      (value "2N7000")
      (footprint "eagle-import:TO92-DGS")
      (libsource (lib "eagle-import") (part "2N7000"))
    )
    (comp (ref "Q70")
      (value "2N7000")
      (footprint "eagle-import:TO92-DGS")
      (libsource (lib "eagle-import") (part "2N7000"))
    )
    (comp (ref "Q71")
      (value "2N7000")
      (footprint "eagle-import:TO92-DGS")
      (libsource (lib "eagle-import") (part "2N7000"))
    )
    (comp (ref "Q72")
      (value "2N7000")
      (footprint "eagle-import:TO92-DGS")
      (libsource (lib "eagle-import") (part "2N7000"))
    )
    (comp (ref "Q73")
      (value "2N7000")
      (footprint "eagle-import:TO92-DGS")
      (libsource (lib "eagle-import") (part "2N7000"))
    )
    (comp (ref "Q74")
      (value "2N7000")
      (footprint "eagle-import:TO92-DGS")
      (libsource (lib "eagle-import") (part "2N7000"))
    )
    (comp (ref "Q75")
      (value "2N7000")
      (footprint "eagle-import:TO92-DGS")
      (libsource (lib "eagle-import") (part "2N7000"))
    )
    (comp (ref "Q76")
      (value "2N7000")
      (footprint "eagle-import:TO92-DGS")
      (libsource (lib "eagle-import") (part "2N7000"))
    )
    (comp (ref "Q77")
      (value "2N7000")
      (footprint "eagle-import:TO92-DGS")
      (libsource (lib "eagle-import") (part "2N7000"))
    )
    (comp (ref "Q78")
      (value "2N7000")
      (footprint "eagle-import:TO92-DGS")
      (libsource (lib "eagle-import") (part "2N7000"))
    )
    (comp (ref "Q79")
      (value "2N7000")
      (footprint "eagle-import:TO92-DGS")
      (libsource (lib "eagle-import") (part "2N7000"))
    )
    (comp (ref "Q80")
      (value "2N7000")
      (footprint "eagle-import:TO92-DGS")
      (libsource (lib "eagle-import") (part "2N7000"))
    )
    (comp (ref "Q81")
      (value "2N7000")
      (footprint "eagle-import:TO92-DGS")
      (libsource (lib "eagle-import") (part "2N7000"))
    )
    (comp (ref "Q82")
      (value "2N7000")
      (footprint "eagle-import:TO92-DGS")
      (libsource (lib "eagle-import") (part "2N7000"))
    )
    (comp (ref "Q83")
      (value "2N7000")
      (footprint "eagle-import:TO92-DGS")
      (libsource (lib "eagle-import") (part "2N7000"))
    )
    (comp (ref "Q84")
      (value "2N7000")
      (footprint "eagle-import:TO92-DGS")
      (libsource (lib "eagle-import") (part "2N7000"))
    )
    (comp (ref "R77")
      (value "10k")
      (footprint "eagle-import:R_P2INCH")
      (libsource (lib "eagle-import") (part "R_P2INCH"))
    )
    (comp (ref "R78")
      (value "10k")
      (footprint "eagle-import:R_P2INCH")
      (libsource (lib "eagle-import") (part "R_P2INCH"))
    )
    (comp (ref "R79")
      (value "10k")
      (footprint "eagle-import:R_P2INCH")
      (libsource (lib "eagle-import") (part "R_P2INCH"))
    )
    (comp (ref "R80")
      (value "10k")
      (footprint "eagle-import:R_P2INCH")
      (libsource (lib "eagle-import") (part "R_P2INCH"))
    )
    (comp (ref "R81")
      (value "10k")
      (footprint "eagle-import:R_P2INCH")
      (libsource (lib "eagle-import") (part "R_P2INCH"))
    )
    (comp (ref "R82")
      (value "10k")
      (footprint "eagle-import:R_P2INCH")
      (libsource (lib "eagle-import") (part "R_P2INCH"))
    )
    (comp (ref "R83")
      (value "10k")
      (footprint "eagle-import:R_P2INCH")
      (libsource (lib "eagle-import") (part "R_P2INCH"))
    )
    (comp (ref "R84")
      (value "10k")
      (footprint "eagle-import:R_P2INCH")
      (libsource (lib "eagle-import") (part "R_P2INCH"))
    )
    (comp (ref "R85")
      (value "10k")
      (footprint "eagle-import:R_P2INCH")
      (libsource (lib "eagle-import") (part "R_P2INCH"))
    )
    (comp (ref "R86")
      (value "10k")
      (footprint "eagle-import:R_P2INCH")
      (libsource (lib "eagle-import") (part "R_P2INCH"))
    )
    (comp (ref "R87")
      (value "10k")
      (footprint "eagle-import:R_P2INCH")
      (libsource (lib "eagle-import") (part "R_P2INCH"))
    )
    (comp (ref "R88")
      (value "10k")
      (footprint "eagle-import:R_P2INCH")
      (libsource (lib "eagle-import") (part "R_P2INCH"))
    )
    (comp (ref "R89")
      (value "10k")
      (footprint "eagle-import:R_P2INCH")
      (libsource (lib "eagle-import") (part "R_P2INCH"))
    )
    (comp (ref "R90")
      (value "10k")
      (footprint "eagle-import:R_P2INCH")
      (libsource (lib "eagle-import") (part "R_P2INCH"))
    )
    (comp (ref "R91")
      (value "10k")
      (footprint "eagle-import:R_P2INCH")
      (libsource (lib "eagle-import") (part "R_P2INCH"))
    )
    (comp (ref "R92")
      (value "10k")
      (footprint "eagle-import:R_P2INCH")
      (libsource (lib "eagle-import") (part "R_P2INCH"))
    )
    (comp (ref "R93")
      (value "10k")
      (footprint "eagle-import:R_P2INCH")
      (libsource (lib "eagle-import") (part "R_P2INCH"))
    )
    (comp (ref "R94")
      (value "10k")
      (footprint "eagle-import:R_P2INCH")
      (libsource (lib "eagle-import") (part "R_P2INCH"))
    )
    (comp (ref "R95")
      (value "10k")
      (footprint "eagle-import:R_P2INCH")
      (libsource (lib "eagle-import") (part "R_P2INCH"))
    )
    (comp (ref "R96")
      (value "10k")
      (footprint "eagle-import:R_P2INCH")
      (libsource (lib "eagle-import") (part "R_P2INCH"))
    )
    (comp (ref "R97")
      (value "10k")
      (footprint "eagle-import:R_P2INCH")
      (libsource (lib "eagle-import") (part "R_P2INCH"))
    )
    (comp (ref "R98")
      (value "10k")
      (footprint "eagle-import:R_P2INCH")
      (libsource (lib "eagle-import") (part "R_P2INCH"))
    )
    (comp (ref "R99")
      (value "10k")
      (footprint "eagle-import:R_P2INCH")
      (libsource (lib "eagle-import") (part "R_P2INCH"))
    )
    (comp (ref "R100")
      (value "10k")
      (footprint "eagle-import:R_P2INCH")
      (libsource (lib "eagle-import") (part "R_P2INCH"))
    )
    (comp (ref "D36")
      (value "L-1334SRT")
      (footprint "eagle-import:LED3MM")
      (libsource (lib "eagle-import") (part "L-1334SRT"))
    )
    (comp (ref "D37")
      (value "L-1334SRT")
      (footprint "eagle-import:LED3MM")
      (libsource (lib "eagle-import") (part "L-1334SRT"))
    )
    (comp (ref "D38")
      (value "L-1334SRT")
      (footprint "eagle-import:LED3MM")
      (libsource (lib "eagle-import") (part "L-1334SRT"))
    )
    (comp (ref "D39")
      (value "L-1334SRT")
      (footprint "eagle-import:LED3MM")
      (libsource (lib "eagle-import") (part "L-1334SRT"))
    )
    (comp (ref "Q189")
      (value "2N7000")
      (footprint "eagle-import:TO92-DGS")
      (libsource (lib "eagle-import") (part "2N7000"))
    )
    (comp (ref "Q190")
      (value "2N7000")
      (footprint "eagle-import:TO92-DGS")
      (libsource (lib "eagle-import") (part "2N7000"))
    )
    (comp (ref "Q191")
      (value "2N7000")
      (footprint "eagle-import:TO92-DGS")
      (libsource (lib "eagle-import") (part "2N7000"))
    )
    (comp (ref "Q194")
      (value "2N7000")
      (footprint "eagle-import:TO92-DGS")
      (libsource (lib "eagle-import") (part "2N7000"))
    )
    (comp (ref "Q195")
      (value "2N7000")
      (footprint "eagle-import:TO92-DGS")
      (libsource (lib "eagle-import") (part "2N7000"))
    )
    (comp (ref "Q196")
      (value "2N7000")
      (footprint "eagle-import:TO92-DGS")
      (libsource (lib "eagle-import") (part "2N7000"))
    )
    (comp (ref "Q199")
      (value "2N7000")
      (footprint "eagle-import:TO92-DGS")
      (libsource (lib "eagle-import") (part "2N7000"))
    )
    (comp (ref "Q200")
      (value "2N7000")
      (footprint "eagle-import:TO92-DGS")
      (libsource (lib "eagle-import") (part "2N7000"))
    )
    (comp (ref "Q201")
      (value "2N7000")
      (footprint "eagle-import:TO92-DGS")
      (libsource (lib "eagle-import") (part "2N7000"))
    )
    (comp (ref "Q204")
      (value "2N7000")
      (footprint "eagle-import:TO92-DGS")
      (libsource (lib "eagle-import") (part "2N7000"))
    )
    (comp (ref "Q205")
      (value "2N7000")
      (footprint "eagle-import:TO92-DGS")
      (libsource (lib "eagle-import") (part "2N7000"))
    )
    (comp (ref "Q206")
      (value "2N7000")
      (footprint "eagle-import:TO92-DGS")
      (libsource (lib "eagle-import") (part "2N7000"))
    )
    (comp (ref "R209")
      (value "10k")
      (footprint "eagle-import:R_P2INCH")
      (libsource (lib "eagle-import") (part "R_P2INCH"))
    )
    (comp (ref "R210")
      (value "470")
      (footprint "eagle-import:R_P2INCH")
      (libsource (lib "eagle-import") (part "R_P2INCH"))
    )
    (comp (ref "R211")
      (value "10k")
      (footprint "eagle-import:R_P2INCH")
      (libsource (lib "eagle-import") (part "R_P2INCH"))
    )
    (comp (ref "R212")
      (value "470")
      (footprint "eagle-import:R_P2INCH")
      (libsource (lib "eagle-import") (part "R_P2INCH"))
    )
    (comp (ref "R213")
      (value "10k")
      (footprint "eagle-import:R_P2INCH")
      (libsource (lib "eagle-import") (part "R_P2INCH"))
    )
    (comp (ref "R214")
      (value "470")
      (footprint "eagle-import:R_P2INCH")
      (libsource (lib "eagle-import") (part "R_P2INCH"))
    )
    (comp (ref "R215")
      (value "10k")
      (footprint "eagle-import:R_P2INCH")
      (libsource (lib "eagle-import") (part "R_P2INCH"))
    )
    (comp (ref "R216")
      (value "470")
      (footprint "eagle-import:R_P2INCH")
      (libsource (lib "eagle-import") (part "R_P2INCH"))
    )
    (comp (ref "R253")
      (value "10k")
      (footprint "eagle-import:R_P2INCH")
      (libsource (lib "eagle-import") (part "R_P2INCH"))
    )
    (comp (ref "R254")
      (value "10k")
      (footprint "eagle-import:R_P2INCH")
      (libsource (lib "eagle-import") (part "R_P2INCH"))
    )
    (comp (ref "R255")
      (value "10k")
      (footprint "eagle-import:R_P2INCH")
      (libsource (lib "eagle-import") (part "R_P2INCH"))
    )
    (comp (ref "R256")
      (value "10k")
      (footprint "eagle-import:R_P2INCH")
      (libsource (lib "eagle-import") (part "R_P2INCH"))
    )
    (comp (ref "J3")
      (value "20_HDR_LOCKING_RA")
      (footprint "eagle-import:20_HDR_LOCKING_RA")
      (libsource (lib "eagle-import") (part "20_HDR_LOCKING_RA"))
    )
    (comp (ref "J4")
      (value "20_HDR_LOCKING_RA")
      (footprint "eagle-import:20_HDR_LOCKING_RA")
      (libsource (lib "eagle-import") (part "20_HDR_LOCKING_RA"))
    )
    (comp (ref "Q59")
      (value "2N7000")
      (footprint "eagle-import:TO92-DGS")
      (libsource (lib "eagle-import") (part "2N7000"))
    )
    (comp (ref "Q60")
      (value "2N7000")
      (footprint "eagle-import:TO92-DGS")
      (libsource (lib "eagle-import") (part "2N7000"))
    )
    (comp (ref "R75")
      (value "10k")
      (footprint "eagle-import:R_P2INCH")
      (libsource (lib "eagle-import") (part "R_P2INCH"))
    )
    (comp (ref "R76")
      (value "10k")
      (footprint "eagle-import:R_P2INCH")
      (libsource (lib "eagle-import") (part "R_P2INCH"))
    )
    (comp (ref "D1")
      (value "L-1334SRT")
      (footprint "eagle-import:LED3MM")
      (libsource (lib "eagle-import") (part "L-1334SRT"))
    )
    (comp (ref "D2")
      (value "L-1334SRT")
      (footprint "eagle-import:LED3MM")
      (libsource (lib "eagle-import") (part "L-1334SRT"))
    )
    (comp (ref "D3")
      (value "L-1334SRT")
      (footprint "eagle-import:LED3MM")
      (libsource (lib "eagle-import") (part "L-1334SRT"))
    )
    (comp (ref "D4")
      (value "L-1334SRT")
      (footprint "eagle-import:LED3MM")
      (libsource (lib "eagle-import") (part "L-1334SRT"))
    )
    (comp (ref "D5")
      (value "L-1334SRT")
      (footprint "eagle-import:LED3MM")
      (libsource (lib "eagle-import") (part "L-1334SRT"))
    )
    (comp (ref "D6")
      (value "L-1334SRT")
      (footprint "eagle-import:LED3MM")
      (libsource (lib "eagle-import") (part "L-1334SRT"))
    )
    (comp (ref "D7")
      (value "L-1334SRT")
      (footprint "eagle-import:LED3MM")
      (libsource (lib "eagle-import") (part "L-1334SRT"))
    )
    (comp (ref "D8")
      (value "L-1334SRT")
      (footprint "eagle-import:LED3MM")
      (libsource (lib "eagle-import") (part "L-1334SRT"))
    )
    (comp (ref "Q1")
      (value "2N7000")
      (footprint "eagle-import:TO92-DGS")
      (libsource (lib "eagle-import") (part "2N7000"))
    )
    (comp (ref "Q2")
      (value "2N7000")
      (footprint "eagle-import:TO92-DGS")
      (libsource (lib "eagle-import") (part "2N7000"))
    )
    (comp (ref "Q3")
      (value "2N7000")
      (footprint "eagle-import:TO92-DGS")
      (libsource (lib "eagle-import") (part "2N7000"))
    )
    (comp (ref "Q4")
      (value "2N7000")
      (footprint "eagle-import:TO92-DGS")
      (libsource (lib "eagle-import") (part "2N7000"))
    )
    (comp (ref "Q5")
      (value "2N7000")
      (footprint "eagle-import:TO92-DGS")
      (libsource (lib "eagle-import") (part "2N7000"))
    )
    (comp (ref "Q6")
      (value "2N7000")
      (footprint "eagle-import:TO92-DGS")
      (libsource (lib "eagle-import") (part "2N7000"))
    )
    (comp (ref "Q7")
      (value "2N7000")
      (footprint "eagle-import:TO92-DGS")
      (libsource (lib "eagle-import") (part "2N7000"))
    )
    (comp (ref "Q8")
      (value "2N7000")
      (footprint "eagle-import:TO92-DGS")
      (libsource (lib "eagle-import") (part "2N7000"))
    )
    (comp (ref "Q9")
      (value "2N7000")
      (footprint "eagle-import:TO92-DGS")
      (libsource (lib "eagle-import") (part "2N7000"))
    )
    (comp (ref "Q10")
      (value "2N7000")
      (footprint "eagle-import:TO92-DGS")
      (libsource (lib "eagle-import") (part "2N7000"))
    )
    (comp (ref "Q11")
      (value "2N7000")
      (footprint "eagle-import:TO92-DGS")
      (libsource (lib "eagle-import") (part "2N7000"))
    )
    (comp (ref "Q12")
      (value "2N7000")
      (footprint "eagle-import:TO92-DGS")
      (libsource (lib "eagle-import") (part "2N7000"))
    )
    (comp (ref "Q13")
      (value "2N7000")
      (footprint "eagle-import:TO92-DGS")
      (libsource (lib "eagle-import") (part "2N7000"))
    )
    (comp (ref "Q14")
      (value "2N7000")
      (footprint "eagle-import:TO92-DGS")
      (libsource (lib "eagle-import") (part "2N7000"))
    )
    (comp (ref "Q15")
      (value "2N7000")
      (footprint "eagle-import:TO92-DGS")
      (libsource (lib "eagle-import") (part "2N7000"))
    )
    (comp (ref "Q16")
      (value "2N7000")
      (footprint "eagle-import:TO92-DGS")
      (libsource (lib "eagle-import") (part "2N7000"))
    )
    (comp (ref "R1")
      (value "10k")
      (footprint "eagle-import:R_P2INCH")
      (libsource (lib "eagle-import") (part "R_P2INCH"))
    )
    (comp (ref "R2")
      (value "470")
      (footprint "eagle-import:R_P2INCH")
      (libsource (lib "eagle-import") (part "R_P2INCH"))
    )
    (comp (ref "R3")
      (value "10k")
      (footprint "eagle-import:R_P2INCH")
      (libsource (lib "eagle-import") (part "R_P2INCH"))
    )
    (comp (ref "R4")
      (value "470")
      (footprint "eagle-import:R_P2INCH")
      (libsource (lib "eagle-import") (part "R_P2INCH"))
    )
    (comp (ref "R5")
      (value "10k")
      (footprint "eagle-import:R_P2INCH")
      (libsource (lib "eagle-import") (part "R_P2INCH"))
    )
    (comp (ref "R6")
      (value "470")
      (footprint "eagle-import:R_P2INCH")
      (libsource (lib "eagle-import") (part "R_P2INCH"))
    )
    (comp (ref "R7")
      (value "10k")
      (footprint "eagle-import:R_P2INCH")
      (libsource (lib "eagle-import") (part "R_P2INCH"))
    )
    (comp (ref "R8")
      (value "470")
      (footprint "eagle-import:R_P2INCH")
      (libsource (lib "eagle-import") (part "R_P2INCH"))
    )
    (comp (ref "R9")
      (value "10k")
      (footprint "eagle-import:R_P2INCH")
      (libsource (lib "eagle-import") (part "R_P2INCH"))
    )
    (comp (ref "R10")
      (value "470")
      (footprint "eagle-import:R_P2INCH")
      (libsource (lib "eagle-import") (part "R_P2INCH"))
    )
    (comp (ref "R11")
      (value "10k")
      (footprint "eagle-import:R_P2INCH")
      (libsource (lib "eagle-import") (part "R_P2INCH"))
    )
    (comp (ref "R12")
      (value "470")
      (footprint "eagle-import:R_P2INCH")
      (libsource (lib "eagle-import") (part "R_P2INCH"))
    )
    (comp (ref "R13")
      (value "10k")
      (footprint "eagle-import:R_P2INCH")
      (libsource (lib "eagle-import") (part "R_P2INCH"))
    )
    (comp (ref "R14")
      (value "470")
      (footprint "eagle-import:R_P2INCH")
      (libsource (lib "eagle-import") (part "R_P2INCH"))
    )
    (comp (ref "R15")
      (value "10k")
      (footprint "eagle-import:R_P2INCH")
      (libsource (lib "eagle-import") (part "R_P2INCH"))
    )
    (comp (ref "R16")
      (value "470")
      (footprint "eagle-import:R_P2INCH")
      (libsource (lib "eagle-import") (part "R_P2INCH"))
    )
    (comp (ref "R17")
      (value "10k")
      (footprint "eagle-import:R_P2INCH")
      (libsource (lib "eagle-import") (part "R_P2INCH"))
    )
    (comp (ref "R18")
      (value "10k")
      (footprint "eagle-import:R_P2INCH")
      (libsource (lib "eagle-import") (part "R_P2INCH"))
    )
    (comp (ref "R19")
      (value "10k")
      (footprint "eagle-import:R_P2INCH")
      (libsource (lib "eagle-import") (part "R_P2INCH"))
    )
    (comp (ref "R20")
      (value "10k")
      (footprint "eagle-import:R_P2INCH")
      (libsource (lib "eagle-import") (part "R_P2INCH"))
    )
    (comp (ref "R21")
      (value "10k")
      (footprint "eagle-import:R_P2INCH")
      (libsource (lib "eagle-import") (part "R_P2INCH"))
    )
    (comp (ref "R22")
      (value "10k")
      (footprint "eagle-import:R_P2INCH")
      (libsource (lib "eagle-import") (part "R_P2INCH"))
    )
    (comp (ref "R23")
      (value "10k")
      (footprint "eagle-import:R_P2INCH")
      (libsource (lib "eagle-import") (part "R_P2INCH"))
    )
    (comp (ref "R24")
      (value "10k")
      (footprint "eagle-import:R_P2INCH")
      (libsource (lib "eagle-import") (part "R_P2INCH"))
    )
    (comp (ref "D9")
      (value "L-1334SRT")
      (footprint "eagle-import:LED3MM")
      (libsource (lib "eagle-import") (part "L-1334SRT"))
    )
    (comp (ref "D10")
      (value "L-1334SRT")
      (footprint "eagle-import:LED3MM")
      (libsource (lib "eagle-import") (part "L-1334SRT"))
    )
    (comp (ref "D11")
      (value "L-1334SRT")
      (footprint "eagle-import:LED3MM")
      (libsource (lib "eagle-import") (part "L-1334SRT"))
    )
    (comp (ref "D12")
      (value "L-1334SRT")
      (footprint "eagle-import:LED3MM")
      (libsource (lib "eagle-import") (part "L-1334SRT"))
    )
    (comp (ref "D13")
      (value "L-1334SRT")
      (footprint "eagle-import:LED3MM")
      (libsource (lib "eagle-import") (part "L-1334SRT"))
    )
    (comp (ref "D14")
      (value "L-1334SRT")
      (footprint "eagle-import:LED3MM")
      (libsource (lib "eagle-import") (part "L-1334SRT"))
    )
    (comp (ref "D15")
      (value "L-1334SRT")
      (footprint "eagle-import:LED3MM")
      (libsource (lib "eagle-import") (part "L-1334SRT"))
    )
    (comp (ref "D16")
      (value "L-1334SRT")
      (footprint "eagle-import:LED3MM")
      (libsource (lib "eagle-import") (part "L-1334SRT"))
    )
    (comp (ref "Q43")
      (value "2N7000")
      (footprint "eagle-import:TO92-DGS")
      (libsource (lib "eagle-import") (part "2N7000"))
    )
    (comp (ref "Q44")
      (value "2N7000")
      (footprint "eagle-import:TO92-DGS")
      (libsource (lib "eagle-import") (part "2N7000"))
    )
    (comp (ref "Q45")
      (value "2N7000")
      (footprint "eagle-import:TO92-DGS")
      (libsource (lib "eagle-import") (part "2N7000"))
    )
    (comp (ref "Q46")
      (value "2N7000")
      (footprint "eagle-import:TO92-DGS")
      (libsource (lib "eagle-import") (part "2N7000"))
    )
    (comp (ref "Q47")
      (value "2N7000")
      (footprint "eagle-import:TO92-DGS")
      (libsource (lib "eagle-import") (part "2N7000"))
    )
    (comp (ref "Q48")
      (value "2N7000")
      (footprint "eagle-import:TO92-DGS")
      (libsource (lib "eagle-import") (part "2N7000"))
    )
    (comp (ref "Q49")
      (value "2N7000")
      (footprint "eagle-import:TO92-DGS")
      (libsource (lib "eagle-import") (part "2N7000"))
    )
    (comp (ref "Q50")
      (value "2N7000")
      (footprint "eagle-import:TO92-DGS")
      (libsource (lib "eagle-import") (part "2N7000"))
    )
    (comp (ref "Q51")
      (value "2N7000")
      (footprint "eagle-import:TO92-DGS")
      (libsource (lib "eagle-import") (part "2N7000"))
    )
    (comp (ref "Q52")
      (value "2N7000")
      (footprint "eagle-import:TO92-DGS")
      (libsource (lib "eagle-import") (part "2N7000"))
    )
    (comp (ref "Q53")
      (value "2N7000")
      (footprint "eagle-import:TO92-DGS")
      (libsource (lib "eagle-import") (part "2N7000"))
    )
    (comp (ref "Q54")
      (value "2N7000")
      (footprint "eagle-import:TO92-DGS")
      (libsource (lib "eagle-import") (part "2N7000"))
    )
    (comp (ref "Q55")
      (value "2N7000")
      (footprint "eagle-import:TO92-DGS")
      (libsource (lib "eagle-import") (part "2N7000"))
    )
    (comp (ref "Q56")
      (value "2N7000")
      (footprint "eagle-import:TO92-DGS")
      (libsource (lib "eagle-import") (part "2N7000"))
    )
    (comp (ref "Q57")
      (value "2N7000")
      (footprint "eagle-import:TO92-DGS")
      (libsource (lib "eagle-import") (part "2N7000"))
    )
    (comp (ref "Q58")
      (value "2N7000")
      (footprint "eagle-import:TO92-DGS")
      (libsource (lib "eagle-import") (part "2N7000"))
    )
    (comp (ref "R51")
      (value "10k")
      (footprint "eagle-import:R_P2INCH")
      (libsource (lib "eagle-import") (part "R_P2INCH"))
    )
    (comp (ref "R52")
      (value "470")
      (footprint "eagle-import:R_P2INCH")
      (libsource (lib "eagle-import") (part "R_P2INCH"))
    )
    (comp (ref "R53")
      (value "10k")
      (footprint "eagle-import:R_P2INCH")
      (libsource (lib "eagle-import") (part "R_P2INCH"))
    )
    (comp (ref "R54")
      (value "470")
      (footprint "eagle-import:R_P2INCH")
      (libsource (lib "eagle-import") (part "R_P2INCH"))
    )
    (comp (ref "R55")
      (value "10k")
      (footprint "eagle-import:R_P2INCH")
      (libsource (lib "eagle-import") (part "R_P2INCH"))
    )
    (comp (ref "R56")
      (value "470")
      (footprint "eagle-import:R_P2INCH")
      (libsource (lib "eagle-import") (part "R_P2INCH"))
    )
    (comp (ref "R57")
      (value "10k")
      (footprint "eagle-import:R_P2INCH")
      (libsource (lib "eagle-import") (part "R_P2INCH"))
    )
    (comp (ref "R58")
      (value "470")
      (footprint "eagle-import:R_P2INCH")
      (libsource (lib "eagle-import") (part "R_P2INCH"))
    )
    (comp (ref "R59")
      (value "10k")
      (footprint "eagle-import:R_P2INCH")
      (libsource (lib "eagle-import") (part "R_P2INCH"))
    )
    (comp (ref "R60")
      (value "470")
      (footprint "eagle-import:R_P2INCH")
      (libsource (lib "eagle-import") (part "R_P2INCH"))
    )
    (comp (ref "R61")
      (value "10k")
      (footprint "eagle-import:R_P2INCH")
      (libsource (lib "eagle-import") (part "R_P2INCH"))
    )
    (comp (ref "R62")
      (value "470")
      (footprint "eagle-import:R_P2INCH")
      (libsource (lib "eagle-import") (part "R_P2INCH"))
    )
    (comp (ref "R63")
      (value "10k")
      (footprint "eagle-import:R_P2INCH")
      (libsource (lib "eagle-import") (part "R_P2INCH"))
    )
    (comp (ref "R64")
      (value "470")
      (footprint "eagle-import:R_P2INCH")
      (libsource (lib "eagle-import") (part "R_P2INCH"))
    )
    (comp (ref "R65")
      (value "10k")
      (footprint "eagle-import:R_P2INCH")
      (libsource (lib "eagle-import") (part "R_P2INCH"))
    )
    (comp (ref "R66")
      (value "470")
      (footprint "eagle-import:R_P2INCH")
      (libsource (lib "eagle-import") (part "R_P2INCH"))
    )
    (comp (ref "R67")
      (value "10k")
      (footprint "eagle-import:R_P2INCH")
      (libsource (lib "eagle-import") (part "R_P2INCH"))
    )
    (comp (ref "R68")
      (value "10k")
      (footprint "eagle-import:R_P2INCH")
      (libsource (lib "eagle-import") (part "R_P2INCH"))
    )
    (comp (ref "R69")
      (value "10k")
      (footprint "eagle-import:R_P2INCH")
      (libsource (lib "eagle-import") (part "R_P2INCH"))
    )
    (comp (ref "R70")
      (value "10k")
      (footprint "eagle-import:R_P2INCH")
      (libsource (lib "eagle-import") (part "R_P2INCH"))
    )
    (comp (ref "R71")
      (value "10k")
      (footprint "eagle-import:R_P2INCH")
      (libsource (lib "eagle-import") (part "R_P2INCH"))
    )
    (comp (ref "R72")
      (value "10k")
      (footprint "eagle-import:R_P2INCH")
      (libsource (lib "eagle-import") (part "R_P2INCH"))
    )
    (comp (ref "R73")
      (value "10k")
      (footprint "eagle-import:R_P2INCH")
      (libsource (lib "eagle-import") (part "R_P2INCH"))
    )
    (comp (ref "R74")
      (value "10k")
      (footprint "eagle-import:R_P2INCH")
      (libsource (lib "eagle-import") (part "R_P2INCH"))
    )
    (comp (ref "D33")
      (value "L-1334SRT")
      (footprint "eagle-import:LED3MM")
      (libsource (lib "eagle-import") (part "L-1334SRT"))
    )
    (comp (ref "D34")
      (value "L-1334SRT")
      (footprint "eagle-import:LED3MM")
      (libsource (lib "eagle-import") (part "L-1334SRT"))
    )
    (comp (ref "D35")
      (value "L-1334SRT")
      (footprint "eagle-import:LED3MM")
      (libsource (lib "eagle-import") (part "L-1334SRT"))
    )
    (comp (ref "D69")
      (value "L-1334SRT")
      (footprint "eagle-import:LED3MM")
      (libsource (lib "eagle-import") (part "L-1334SRT"))
    )
    (comp (ref "Q169")
      (value "2N7000")
      (footprint "eagle-import:TO92-DGS")
      (libsource (lib "eagle-import") (part "2N7000"))
    )
    (comp (ref "Q170")
      (value "2N7000")
      (footprint "eagle-import:TO92-DGS")
      (libsource (lib "eagle-import") (part "2N7000"))
    )
    (comp (ref "Q171")
      (value "2N7000")
      (footprint "eagle-import:TO92-DGS")
      (libsource (lib "eagle-import") (part "2N7000"))
    )
    (comp (ref "Q174")
      (value "2N7000")
      (footprint "eagle-import:TO92-DGS")
      (libsource (lib "eagle-import") (part "2N7000"))
    )
    (comp (ref "Q175")
      (value "2N7000")
      (footprint "eagle-import:TO92-DGS")
      (libsource (lib "eagle-import") (part "2N7000"))
    )
    (comp (ref "Q176")
      (value "2N7000")
      (footprint "eagle-import:TO92-DGS")
      (libsource (lib "eagle-import") (part "2N7000"))
    )
    (comp (ref "Q179")
      (value "2N7000")
      (footprint "eagle-import:TO92-DGS")
      (libsource (lib "eagle-import") (part "2N7000"))
    )
    (comp (ref "Q180")
      (value "2N7000")
      (footprint "eagle-import:TO92-DGS")
      (libsource (lib "eagle-import") (part "2N7000"))
    )
    (comp (ref "Q181")
      (value "2N7000")
      (footprint "eagle-import:TO92-DGS")
      (libsource (lib "eagle-import") (part "2N7000"))
    )
    (comp (ref "Q184")
      (value "2N7000")
      (footprint "eagle-import:TO92-DGS")
      (libsource (lib "eagle-import") (part "2N7000"))
    )
    (comp (ref "Q185")
      (value "2N7000")
      (footprint "eagle-import:TO92-DGS")
      (libsource (lib "eagle-import") (part "2N7000"))
    )
    (comp (ref "Q186")
      (value "2N7000")
      (footprint "eagle-import:TO92-DGS")
      (libsource (lib "eagle-import") (part "2N7000"))
    )
    (comp (ref "R201")
      (value "10k")
      (footprint "eagle-import:R_P2INCH")
      (libsource (lib "eagle-import") (part "R_P2INCH"))
    )
    (comp (ref "R202")
      (value "470")
      (footprint "eagle-import:R_P2INCH")
      (libsource (lib "eagle-import") (part "R_P2INCH"))
    )
    (comp (ref "R203")
      (value "10k")
      (footprint "eagle-import:R_P2INCH")
      (libsource (lib "eagle-import") (part "R_P2INCH"))
    )
    (comp (ref "R204")
      (value "470")
      (footprint "eagle-import:R_P2INCH")
      (libsource (lib "eagle-import") (part "R_P2INCH"))
    )
    (comp (ref "R205")
      (value "10k")
      (footprint "eagle-import:R_P2INCH")
      (libsource (lib "eagle-import") (part "R_P2INCH"))
    )
    (comp (ref "R206")
      (value "470")
      (footprint "eagle-import:R_P2INCH")
      (libsource (lib "eagle-import") (part "R_P2INCH"))
    )
    (comp (ref "R207")
      (value "10k")
      (footprint "eagle-import:R_P2INCH")
      (libsource (lib "eagle-import") (part "R_P2INCH"))
    )
    (comp (ref "R208")
      (value "470")
      (footprint "eagle-import:R_P2INCH")
      (libsource (lib "eagle-import") (part "R_P2INCH"))
    )
    (comp (ref "R257")
      (value "10k")
      (footprint "eagle-import:R_P2INCH")
      (libsource (lib "eagle-import") (part "R_P2INCH"))
    )
    (comp (ref "R258")
      (value "10k")
      (footprint "eagle-import:R_P2INCH")
      (libsource (lib "eagle-import") (part "R_P2INCH"))
    )
    (comp (ref "R259")
      (value "10k")
      (footprint "eagle-import:R_P2INCH")
      (libsource (lib "eagle-import") (part "R_P2INCH"))
    )
    (comp (ref "R260")
      (value "10k")
      (footprint "eagle-import:R_P2INCH")
      (libsource (lib "eagle-import") (part "R_P2INCH"))
    )
    (comp (ref "J9")
      (value "20_HDR_LOCKING_RA")
      (footprint "eagle-import:20_HDR_LOCKING_RA")
      (libsource (lib "eagle-import") (part "20_HDR_LOCKING_RA"))
    )
    (comp (ref "J10")
      (value "20_HDR_LOCKING_RA")
      (footprint "eagle-import:20_HDR_LOCKING_RA")
      (libsource (lib "eagle-import") (part "20_HDR_LOCKING_RA"))
    )
    (comp (ref "J12")
      (value "JUMP_16X1")
      (footprint "eagle-import:JUMP_16X1")
      (libsource (lib "eagle-import") (part "JUMP_16X1"))
    )
    (comp (ref "Q233")
      (value "2N7000")
      (footprint "eagle-import:TO92-DGS")
      (libsource (lib "eagle-import") (part "2N7000"))
    )
    (comp (ref "Q235")
      (value "2N7000")
      (footprint "eagle-import:TO92-DGS")
      (libsource (lib "eagle-import") (part "2N7000"))
    )
    (comp (ref "Q236")
      (value "2N7000")
      (footprint "eagle-import:TO92-DGS")
      (libsource (lib "eagle-import") (part "2N7000"))
    )
    (comp (ref "Q237")
      (value "2N7000")
      (footprint "eagle-import:TO92-DGS")
      (libsource (lib "eagle-import") (part "2N7000"))
    )
    (comp (ref "Q239")
      (value "2N7000")
      (footprint "eagle-import:TO92-DGS")
      (libsource (lib "eagle-import") (part "2N7000"))
    )
    (comp (ref "Q240")
      (value "2N7000")
      (footprint "eagle-import:TO92-DGS")
      (libsource (lib "eagle-import") (part "2N7000"))
    )
    (comp (ref "Q241")
      (value "2N7000")
      (footprint "eagle-import:TO92-DGS")
      (libsource (lib "eagle-import") (part "2N7000"))
    )
    (comp (ref "Q243")
      (value "2N7000")
      (footprint "eagle-import:TO92-DGS")
      (libsource (lib "eagle-import") (part "2N7000"))
    )
    (comp (ref "Q244")
      (value "2N7000")
      (footprint "eagle-import:TO92-DGS")
      (libsource (lib "eagle-import") (part "2N7000"))
    )
    (comp (ref "R241")
      (value "10k")
      (footprint "eagle-import:R_P2INCH")
      (libsource (lib "eagle-import") (part "R_P2INCH"))
    )
    (comp (ref "R243")
      (value "10k")
      (footprint "eagle-import:R_P2INCH")
      (libsource (lib "eagle-import") (part "R_P2INCH"))
    )
    (comp (ref "R244")
      (value "10k")
      (footprint "eagle-import:R_P2INCH")
      (libsource (lib "eagle-import") (part "R_P2INCH"))
    )
    (comp (ref "R245")
      (value "10k")
      (footprint "eagle-import:R_P2INCH")
      (libsource (lib "eagle-import") (part "R_P2INCH"))
    )
    (comp (ref "R246")
      (value "10k")
      (footprint "eagle-import:R_P2INCH")
      (libsource (lib "eagle-import") (part "R_P2INCH"))
    )
    (comp (ref "R247")
      (value "10k")
      (footprint "eagle-import:R_P2INCH")
      (libsource (lib "eagle-import") (part "R_P2INCH"))
    )
    (comp (ref "R248")
      (value "10k")
      (footprint "eagle-import:R_P2INCH")
      (libsource (lib "eagle-import") (part "R_P2INCH"))
    )
    (comp (ref "TP1")
      (value "TEST_LOOP")
      (footprint "eagle-import:TEST_LOOP")
      (libsource (lib "eagle-import") (part "TEST_LOOP"))
    )
    (comp (ref "J1")
      (value "20_HDR_LOCKING_RA")
      (footprint "eagle-import:20_HDR_LOCKING_RA")
      (libsource (lib "eagle-import") (part "20_HDR_LOCKING_RA"))
    )
    (comp (ref "J2")
      (value "20_HDR_LOCKING_RA")
      (footprint "eagle-import:20_HDR_LOCKING_RA")
      (libsource (lib "eagle-import") (part "20_HDR_LOCKING_RA"))
    )
    (comp (ref "Q23")
      (value "2N7000")
      (footprint "eagle-import:TO92-DGS")
      (libsource (lib "eagle-import") (part "2N7000"))
    )
    (comp (ref "Q24")
      (value "2N7000")
      (footprint "eagle-import:TO92-DGS")
      (libsource (lib "eagle-import") (part "2N7000"))
    )
    (comp (ref "R31")
      (value "10k")
      (footprint "eagle-import:R_P2INCH")
      (libsource (lib "eagle-import") (part "R_P2INCH"))
    )
    (comp (ref "R32")
      (value "10k")
      (footprint "eagle-import:R_P2INCH")
      (libsource (lib "eagle-import") (part "R_P2INCH"))
    )
    (comp (ref "Q17")
      (value "2N7000")
      (footprint "eagle-import:TO92-DGS")
      (libsource (lib "eagle-import") (part "2N7000"))
    )
    (comp (ref "Q18")
      (value "2N7000")
      (footprint "eagle-import:TO92-DGS")
      (libsource (lib "eagle-import") (part "2N7000"))
    )
    (comp (ref "Q19")
      (value "2N7000")
      (footprint "eagle-import:TO92-DGS")
      (libsource (lib "eagle-import") (part "2N7000"))
    )
    (comp (ref "Q20")
      (value "2N7000")
      (footprint "eagle-import:TO92-DGS")
      (libsource (lib "eagle-import") (part "2N7000"))
    )
    (comp (ref "Q21")
      (value "2N7000")
      (footprint "eagle-import:TO92-DGS")
      (libsource (lib "eagle-import") (part "2N7000"))
    )
    (comp (ref "Q22")
      (value "2N7000")
      (footprint "eagle-import:TO92-DGS")
      (libsource (lib "eagle-import") (part "2N7000"))
    )
    (comp (ref "Q25")
      (value "2N7000")
      (footprint "eagle-import:TO92-DGS")
      (libsource (lib "eagle-import") (part "2N7000"))
    )
    (comp (ref "Q26")
      (value "2N7000")
      (footprint "eagle-import:TO92-DGS")
      (libsource (lib "eagle-import") (part "2N7000"))
    )
    (comp (ref "Q27")
      (value "2N7000")
      (footprint "eagle-import:TO92-DGS")
      (libsource (lib "eagle-import") (part "2N7000"))
    )
    (comp (ref "Q28")
      (value "2N7000")
      (footprint "eagle-import:TO92-DGS")
      (libsource (lib "eagle-import") (part "2N7000"))
    )
    (comp (ref "Q29")
      (value "2N7000")
      (footprint "eagle-import:TO92-DGS")
      (libsource (lib "eagle-import") (part "2N7000"))
    )
    (comp (ref "Q30")
      (value "2N7000")
      (footprint "eagle-import:TO92-DGS")
      (libsource (lib "eagle-import") (part "2N7000"))
    )
    (comp (ref "Q31")
      (value "2N7000")
      (footprint "eagle-import:TO92-DGS")
      (libsource (lib "eagle-import") (part "2N7000"))
    )
    (comp (ref "Q32")
      (value "2N7000")
      (footprint "eagle-import:TO92-DGS")
      (libsource (lib "eagle-import") (part "2N7000"))
    )
    (comp (ref "Q33")
      (value "2N7000")
      (footprint "eagle-import:TO92-DGS")
      (libsource (lib "eagle-import") (part "2N7000"))
    )
    (comp (ref "Q34")
      (value "2N7000")
      (footprint "eagle-import:TO92-DGS")
      (libsource (lib "eagle-import") (part "2N7000"))
    )
    (comp (ref "Q35")
      (value "2N7000")
      (footprint "eagle-import:TO92-DGS")
      (libsource (lib "eagle-import") (part "2N7000"))
    )
    (comp (ref "Q36")
      (value "2N7000")
      (footprint "eagle-import:TO92-DGS")
      (libsource (lib "eagle-import") (part "2N7000"))
    )
    (comp (ref "Q37")
      (value "2N7000")
      (footprint "eagle-import:TO92-DGS")
      (libsource (lib "eagle-import") (part "2N7000"))
    )
    (comp (ref "Q38")
      (value "2N7000")
      (footprint "eagle-import:TO92-DGS")
      (libsource (lib "eagle-import") (part "2N7000"))
    )
    (comp (ref "Q39")
      (value "2N7000")
      (footprint "eagle-import:TO92-DGS")
      (libsource (lib "eagle-import") (part "2N7000"))
    )
    (comp (ref "Q40")
      (value "2N7000")
      (footprint "eagle-import:TO92-DGS")
      (libsource (lib "eagle-import") (part "2N7000"))
    )
    (comp (ref "Q41")
      (value "2N7000")
      (footprint "eagle-import:TO92-DGS")
      (libsource (lib "eagle-import") (part "2N7000"))
    )
    (comp (ref "Q42")
      (value "2N7000")
      (footprint "eagle-import:TO92-DGS")
      (libsource (lib "eagle-import") (part "2N7000"))
    )
    (comp (ref "R25")
      (value "10k")
      (footprint "eagle-import:R_P2INCH")
      (libsource (lib "eagle-import") (part "R_P2INCH"))
    )
    (comp (ref "R26")
      (value "10k")
      (footprint "eagle-import:R_P2INCH")
      (libsource (lib "eagle-import") (part "R_P2INCH"))
    )
    (comp (ref "R27")
      (value "10k")
      (footprint "eagle-import:R_P2INCH")
      (libsource (lib "eagle-import") (part "R_P2INCH"))
    )
    (comp (ref "R28")
      (value "10k")
      (footprint "eagle-import:R_P2INCH")
      (libsource (lib "eagle-import") (part "R_P2INCH"))
    )
    (comp (ref "R29")
      (value "10k")
      (footprint "eagle-import:R_P2INCH")
      (libsource (lib "eagle-import") (part "R_P2INCH"))
    )
    (comp (ref "R30")
      (value "10k")
      (footprint "eagle-import:R_P2INCH")
      (libsource (lib "eagle-import") (part "R_P2INCH"))
    )
    (comp (ref "R33")
      (value "10k")
      (footprint "eagle-import:R_P2INCH")
      (libsource (lib "eagle-import") (part "R_P2INCH"))
    )
    (comp (ref "R34")
      (value "10k")
      (footprint "eagle-import:R_P2INCH")
      (libsource (lib "eagle-import") (part "R_P2INCH"))
    )
    (comp (ref "R35")
      (value "10k")
      (footprint "eagle-import:R_P2INCH")
      (libsource (lib "eagle-import") (part "R_P2INCH"))
    )
    (comp (ref "R36")
      (value "10k")
      (footprint "eagle-import:R_P2INCH")
      (libsource (lib "eagle-import") (part "R_P2INCH"))
    )
    (comp (ref "R37")
      (value "10k")
      (footprint "eagle-import:R_P2INCH")
      (libsource (lib "eagle-import") (part "R_P2INCH"))
    )
    (comp (ref "R38")
      (value "10k")
      (footprint "eagle-import:R_P2INCH")
      (libsource (lib "eagle-import") (part "R_P2INCH"))
    )
    (comp (ref "R39")
      (value "10k")
      (footprint "eagle-import:R_P2INCH")
      (libsource (lib "eagle-import") (part "R_P2INCH"))
    )
    (comp (ref "R40")
      (value "10k")
      (footprint "eagle-import:R_P2INCH")
      (libsource (lib "eagle-import") (part "R_P2INCH"))
    )
    (comp (ref "R41")
      (value "10k")
      (footprint "eagle-import:R_P2INCH")
      (libsource (lib "eagle-import") (part "R_P2INCH"))
    )
    (comp (ref "R42")
      (value "10k")
      (footprint "eagle-import:R_P2INCH")
      (libsource (lib "eagle-import") (part "R_P2INCH"))
    )
    (comp (ref "R43")
      (value "10k")
      (footprint "eagle-import:R_P2INCH")
      (libsource (lib "eagle-import") (part "R_P2INCH"))
    )
    (comp (ref "R44")
      (value "10k")
      (footprint "eagle-import:R_P2INCH")
      (libsource (lib "eagle-import") (part "R_P2INCH"))
    )
    (comp (ref "R45")
      (value "10k")
      (footprint "eagle-import:R_P2INCH")
      (libsource (lib "eagle-import") (part "R_P2INCH"))
    )
    (comp (ref "R46")
      (value "10k")
      (footprint "eagle-import:R_P2INCH")
      (libsource (lib "eagle-import") (part "R_P2INCH"))
    )
    (comp (ref "R47")
      (value "10k")
      (footprint "eagle-import:R_P2INCH")
      (libsource (lib "eagle-import") (part "R_P2INCH"))
    )
    (comp (ref "R48")
      (value "10k")
      (footprint "eagle-import:R_P2INCH")
      (libsource (lib "eagle-import") (part "R_P2INCH"))
    )
    (comp (ref "R49")
      (value "10k")
      (footprint "eagle-import:R_P2INCH")
      (libsource (lib "eagle-import") (part "R_P2INCH"))
    )
    (comp (ref "R50")
      (value "10k")
      (footprint "eagle-import:R_P2INCH")
      (libsource (lib "eagle-import") (part "R_P2INCH"))
    )
    (comp (ref "Q209")
      (value "2N7000")
      (footprint "eagle-import:TO92-DGS")
      (libsource (lib "eagle-import") (part "2N7000"))
    )
    (comp (ref "Q210")
      (value "2N7000")
      (footprint "eagle-import:TO92-DGS")
      (libsource (lib "eagle-import") (part "2N7000"))
    )
    (comp (ref "Q211")
      (value "2N7000")
      (footprint "eagle-import:TO92-DGS")
      (libsource (lib "eagle-import") (part "2N7000"))
    )
    (comp (ref "Q212")
      (value "2N7000")
      (footprint "eagle-import:TO92-DGS")
      (libsource (lib "eagle-import") (part "2N7000"))
    )
    (comp (ref "Q213")
      (value "2N7000")
      (footprint "eagle-import:TO92-DGS")
      (libsource (lib "eagle-import") (part "2N7000"))
    )
    (comp (ref "Q214")
      (value "2N7000")
      (footprint "eagle-import:TO92-DGS")
      (libsource (lib "eagle-import") (part "2N7000"))
    )
    (comp (ref "Q215")
      (value "2N7000")
      (footprint "eagle-import:TO92-DGS")
      (libsource (lib "eagle-import") (part "2N7000"))
    )
    (comp (ref "Q216")
      (value "2N7000")
      (footprint "eagle-import:TO92-DGS")
      (libsource (lib "eagle-import") (part "2N7000"))
    )
    (comp (ref "Q217")
      (value "2N7000")
      (footprint "eagle-import:TO92-DGS")
      (libsource (lib "eagle-import") (part "2N7000"))
    )
    (comp (ref "Q218")
      (value "2N7000")
      (footprint "eagle-import:TO92-DGS")
      (libsource (lib "eagle-import") (part "2N7000"))
    )
    (comp (ref "Q219")
      (value "2N7000")
      (footprint "eagle-import:TO92-DGS")
      (libsource (lib "eagle-import") (part "2N7000"))
    )
    (comp (ref "Q220")
      (value "2N7000")
      (footprint "eagle-import:TO92-DGS")
      (libsource (lib "eagle-import") (part "2N7000"))
    )
    (comp (ref "Q221")
      (value "2N7000")
      (footprint "eagle-import:TO92-DGS")
      (libsource (lib "eagle-import") (part "2N7000"))
    )
    (comp (ref "Q222")
      (value "2N7000")
      (footprint "eagle-import:TO92-DGS")
      (libsource (lib "eagle-import") (part "2N7000"))
    )
    (comp (ref "Q223")
      (value "2N7000")
      (footprint "eagle-import:TO92-DGS")
      (libsource (lib "eagle-import") (part "2N7000"))
    )
    (comp (ref "Q224")
      (value "2N7000")
      (footprint "eagle-import:TO92-DGS")
      (libsource (lib "eagle-import") (part "2N7000"))
    )
    (comp (ref "Q225")
      (value "2N7000")
      (footprint "eagle-import:TO92-DGS")
      (libsource (lib "eagle-import") (part "2N7000"))
    )
    (comp (ref "Q226")
      (value "2N7000")
      (footprint "eagle-import:TO92-DGS")
      (libsource (lib "eagle-import") (part "2N7000"))
    )
    (comp (ref "Q227")
      (value "2N7000")
      (footprint "eagle-import:TO92-DGS")
      (libsource (lib "eagle-import") (part "2N7000"))
    )
    (comp (ref "Q228")
      (value "2N7000")
      (footprint "eagle-import:TO92-DGS")
      (libsource (lib "eagle-import") (part "2N7000"))
    )
    (comp (ref "Q229")
      (value "2N7000")
      (footprint "eagle-import:TO92-DGS")
      (libsource (lib "eagle-import") (part "2N7000"))
    )
    (comp (ref "Q230")
      (value "2N7000")
      (footprint "eagle-import:TO92-DGS")
      (libsource (lib "eagle-import") (part "2N7000"))
    )
    (comp (ref "Q231")
      (value "2N7000")
      (footprint "eagle-import:TO92-DGS")
      (libsource (lib "eagle-import") (part "2N7000"))
    )
    (comp (ref "Q232")
      (value "2N7000")
      (footprint "eagle-import:TO92-DGS")
      (libsource (lib "eagle-import") (part "2N7000"))
    )
    (comp (ref "R217")
      (value "10k")
      (footprint "eagle-import:R_P2INCH")
      (libsource (lib "eagle-import") (part "R_P2INCH"))
    )
    (comp (ref "R218")
      (value "10k")
      (footprint "eagle-import:R_P2INCH")
      (libsource (lib "eagle-import") (part "R_P2INCH"))
    )
    (comp (ref "R219")
      (value "10k")
      (footprint "eagle-import:R_P2INCH")
      (libsource (lib "eagle-import") (part "R_P2INCH"))
    )
    (comp (ref "R220")
      (value "10k")
      (footprint "eagle-import:R_P2INCH")
      (libsource (lib "eagle-import") (part "R_P2INCH"))
    )
    (comp (ref "R221")
      (value "10k")
      (footprint "eagle-import:R_P2INCH")
      (libsource (lib "eagle-import") (part "R_P2INCH"))
    )
    (comp (ref "R222")
      (value "10k")
      (footprint "eagle-import:R_P2INCH")
      (libsource (lib "eagle-import") (part "R_P2INCH"))
    )
    (comp (ref "R223")
      (value "10k")
      (footprint "eagle-import:R_P2INCH")
      (libsource (lib "eagle-import") (part "R_P2INCH"))
    )
    (comp (ref "R224")
      (value "10k")
      (footprint "eagle-import:R_P2INCH")
      (libsource (lib "eagle-import") (part "R_P2INCH"))
    )
    (comp (ref "R225")
      (value "10k")
      (footprint "eagle-import:R_P2INCH")
      (libsource (lib "eagle-import") (part "R_P2INCH"))
    )
    (comp (ref "R226")
      (value "10k")
      (footprint "eagle-import:R_P2INCH")
      (libsource (lib "eagle-import") (part "R_P2INCH"))
    )
    (comp (ref "R227")
      (value "10k")
      (footprint "eagle-import:R_P2INCH")
      (libsource (lib "eagle-import") (part "R_P2INCH"))
    )
    (comp (ref "R228")
      (value "10k")
      (footprint "eagle-import:R_P2INCH")
      (libsource (lib "eagle-import") (part "R_P2INCH"))
    )
    (comp (ref "R229")
      (value "10k")
      (footprint "eagle-import:R_P2INCH")
      (libsource (lib "eagle-import") (part "R_P2INCH"))
    )
    (comp (ref "R230")
      (value "10k")
      (footprint "eagle-import:R_P2INCH")
      (libsource (lib "eagle-import") (part "R_P2INCH"))
    )
    (comp (ref "R231")
      (value "10k")
      (footprint "eagle-import:R_P2INCH")
      (libsource (lib "eagle-import") (part "R_P2INCH"))
    )
    (comp (ref "R232")
      (value "10k")
      (footprint "eagle-import:R_P2INCH")
      (libsource (lib "eagle-import") (part "R_P2INCH"))
    )
    (comp (ref "R233")
      (value "10k")
      (footprint "eagle-import:R_P2INCH")
      (libsource (lib "eagle-import") (part "R_P2INCH"))
    )
    (comp (ref "R234")
      (value "10k")
      (footprint "eagle-import:R_P2INCH")
      (libsource (lib "eagle-import") (part "R_P2INCH"))
    )
    (comp (ref "R235")
      (value "10k")
      (footprint "eagle-import:R_P2INCH")
      (libsource (lib "eagle-import") (part "R_P2INCH"))
    )
    (comp (ref "R236")
      (value "10k")
      (footprint "eagle-import:R_P2INCH")
      (libsource (lib "eagle-import") (part "R_P2INCH"))
    )
    (comp (ref "R237")
      (value "10k")
      (footprint "eagle-import:R_P2INCH")
      (libsource (lib "eagle-import") (part "R_P2INCH"))
    )
    (comp (ref "R238")
      (value "10k")
      (footprint "eagle-import:R_P2INCH")
      (libsource (lib "eagle-import") (part "R_P2INCH"))
    )
    (comp (ref "R239")
      (value "10k")
      (footprint "eagle-import:R_P2INCH")
      (libsource (lib "eagle-import") (part "R_P2INCH"))
    )
    (comp (ref "R240")
      (value "10k")
      (footprint "eagle-import:R_P2INCH")
      (libsource (lib "eagle-import") (part "R_P2INCH"))
    )
    (comp (ref "C1")
      (value "100n")
      (footprint "eagle-import:CAP_P2INCH")
      (libsource (lib "eagle-import") (part "C_P2INCH"))
    )
    (comp (ref "C2")
      (value "100n")
      (footprint "eagle-import:CAP_P2INCH")
      (libsource (lib "eagle-import") (part "C_P2INCH"))
    )
    (comp (ref "C3")
      (value "100n")
      (footprint "eagle-import:CAP_P2INCH")
      (libsource (lib "eagle-import") (part "C_P2INCH"))
    )
    (comp (ref "C4")
      (value "100n")
      (footprint "eagle-import:CAP_P2INCH")
      (libsource (lib "eagle-import") (part "C_P2INCH"))
    )
    (comp (ref "C5")
      (value "100n")
      (footprint "eagle-import:CAP_P2INCH")
      (libsource (lib "eagle-import") (part "C_P2INCH"))
    )
    (comp (ref "C6")
      (value "100n")
      (footprint "eagle-import:CAP_P2INCH")
      (libsource (lib "eagle-import") (part "C_P2INCH"))
    )
    (comp (ref "C7")
      (value "100u")
      (footprint "eagle-import:POLARISED_CAP_2P5_6P3MM")
      (libsource (lib "eagle-import") (part "POLARISED_CAP_2P5_6P3MM"))
    )
    (comp (ref "H2")
      (value "3M_MOUNT_HOLE")
      (footprint "eagle-import:3M_HOLE")
      (libsource (lib "eagle-import") (part "3M_MOUNT_HOLE"))
    )
    (comp (ref "H3")
      (value "3M_MOUNT_HOLE")
      (footprint "eagle-import:3M_HOLE")
      (libsource (lib "eagle-import") (part "3M_MOUNT_HOLE"))
    )
    (comp (ref "H5")
      (value "3M_MOUNT_HOLE")
      (footprint "eagle-import:3M_HOLE")
      (libsource (lib "eagle-import") (part "3M_MOUNT_HOLE"))
    )
    (comp (ref "H6")
      (value "3M_MOUNT_HOLE")
      (footprint "eagle-import:3M_HOLE")
      (libsource (lib "eagle-import") (part "3M_MOUNT_HOLE"))
    )
    (comp (ref "H9")
      (value "3M_MOUNT_HOLE")
      (footprint "eagle-import:3M_HOLE")
      (libsource (lib "eagle-import") (part "3M_MOUNT_HOLE"))
    )
    (comp (ref "H10")
      (value "3M_MOUNT_HOLE")
      (footprint "eagle-import:3M_HOLE")
      (libsource (lib "eagle-import") (part "3M_MOUNT_HOLE"))
    )
    (comp (ref "TP5")
      (value "POWER_PAD")
      (footprint "eagle-import:POWER_PAD")
      (libsource (lib "eagle-import") (part "POWER_PAD"))
    )
    (comp (ref "TP6")
      (value "POWER_PAD")
      (footprint "eagle-import:POWER_PAD")
      (libsource (lib "eagle-import") (part "POWER_PAD"))
    )
  )
  (nets
    (net (code "1") (name "+5V") (class "Default")
      (node (ref "C1") (pin "1") (pinfunction "1_1") (pintype "passive"))
      (node (ref "C2") (pin "1") (pinfunction "1_1") (pintype "passive"))
      (node (ref "C3") (pin "1") (pinfunction "1_1") (pintype "passive"))
      (node (ref "C4") (pin "1") (pinfunction "1_1") (pintype "passive"))
      (node (ref "C5") (pin "1") (pinfunction "1_1") (pintype "passive"))
      (node (ref "C6") (pin "1") (pinfunction "1_1") (pintype "passive"))
      (node (ref "C7") (pin "A") (pinfunction "A_A") (pintype "passive"))
      (node (ref "D1") (pin "A") (pinfunction "A_A") (pintype "passive"))
      (node (ref "D10") (pin "A") (pinfunction "A_A") (pintype "passive"))
      (node (ref "D11") (pin "A") (pinfunction "A_A") (pintype "passive"))
      (node (ref "D12") (pin "A") (pinfunction "A_A") (pintype "passive"))
      (node (ref "D13") (pin "A") (pinfunction "A_A") (pintype "passive"))
      (node (ref "D14") (pin "A") (pinfunction "A_A") (pintype "passive"))
      (node (ref "D15") (pin "A") (pinfunction "A_A") (pintype "passive"))
      (node (ref "D16") (pin "A") (pinfunction "A_A") (pintype "passive"))
      (node (ref "D2") (pin "A") (pinfunction "A_A") (pintype "passive"))
      (node (ref "D3") (pin "A") (pinfunction "A_A") (pintype "passive"))
      (node (ref "D33") (pin "A") (pinfunction "A_A") (pintype "passive"))
      (node (ref "D34") (pin "A") (pinfunction "A_A") (pintype "passive"))
      (node (ref "D35") (pin "A") (pinfunction "A_A") (pintype "passive"))
      (node (ref "D36") (pin "A") (pinfunction "A_A") (pintype "passive"))
      (node (ref "D37") (pin "A") (pinfunction "A_A") (pintype "passive"))
      (node (ref "D38") (pin "A") (pinfunction "A_A") (pintype "passive"))
      (node (ref "D39") (pin "A") (pinfunction "A_A") (pintype "passive"))
      (node (ref "D4") (pin "A") (pinfunction "A_A") (pintype "passive"))
      (node (ref "D5") (pin "A") (pinfunction "A_A") (pintype "passive"))
      (node (ref "D6") (pin "A") (pinfunction "A_A") (pintype "passive"))
      (node (ref "D69") (pin "A") (pinfunction "A_A") (pintype "passive"))
      (node (ref "D7") (pin "A") (pinfunction "A_A") (pintype "passive"))
      (node (ref "D8") (pin "A") (pinfunction "A_A") (pintype "passive"))
      (node (ref "D9") (pin "A") (pinfunction "A_A") (pintype "passive"))
      (node (ref "R1") (pin "2") (pinfunction "2_2") (pintype "passive"))
      (node (ref "R100") (pin "2") (pinfunction "2_2") (pintype "passive"))
      (node (ref "R11") (pin "2") (pinfunction "2_2") (pintype "passive"))
      (node (ref "R13") (pin "2") (pinfunction "2_2") (pintype "passive"))
      (node (ref "R15") (pin "2") (pinfunction "2_2") (pintype "passive"))
      (node (ref "R17") (pin "2") (pinfunction "2_2") (pintype "passive"))
      (node (ref "R18") (pin "2") (pinfunction "2_2") (pintype "passive"))
      (node (ref "R19") (pin "2") (pinfunction "2_2") (pintype "passive"))
      (node (ref "R20") (pin "2") (pinfunction "2_2") (pintype "passive"))
      (node (ref "R201") (pin "2") (pinfunction "2_2") (pintype "passive"))
      (node (ref "R203") (pin "2") (pinfunction "2_2") (pintype "passive"))
      (node (ref "R205") (pin "2") (pinfunction "2_2") (pintype "passive"))
      (node (ref "R207") (pin "2") (pinfunction "2_2") (pintype "passive"))
      (node (ref "R209") (pin "2") (pinfunction "2_2") (pintype "passive"))
      (node (ref "R21") (pin "2") (pinfunction "2_2") (pintype "passive"))
      (node (ref "R211") (pin "2") (pinfunction "2_2") (pintype "passive"))
      (node (ref "R213") (pin "2") (pinfunction "2_2") (pintype "passive"))
      (node (ref "R215") (pin "2") (pinfunction "2_2") (pintype "passive"))
      (node (ref "R217") (pin "2") (pinfunction "2_2") (pintype "passive"))
      (node (ref "R218") (pin "2") (pinfunction "2_2") (pintype "passive"))
      (node (ref "R219") (pin "2") (pinfunction "2_2") (pintype "passive"))
      (node (ref "R22") (pin "2") (pinfunction "2_2") (pintype "passive"))
      (node (ref "R220") (pin "2") (pinfunction "2_2") (pintype "passive"))
      (node (ref "R221") (pin "2") (pinfunction "2_2") (pintype "passive"))
      (node (ref "R222") (pin "2") (pinfunction "2_2") (pintype "passive"))
      (node (ref "R223") (pin "2") (pinfunction "2_2") (pintype "passive"))
      (node (ref "R224") (pin "2") (pinfunction "2_2") (pintype "passive"))
      (node (ref "R225") (pin "2") (pinfunction "2_2") (pintype "passive"))
      (node (ref "R226") (pin "2") (pinfunction "2_2") (pintype "passive"))
      (node (ref "R227") (pin "2") (pinfunction "2_2") (pintype "passive"))
      (node (ref "R228") (pin "2") (pinfunction "2_2") (pintype "passive"))
      (node (ref "R229") (pin "2") (pinfunction "2_2") (pintype "passive"))
      (node (ref "R23") (pin "2") (pinfunction "2_2") (pintype "passive"))
      (node (ref "R230") (pin "2") (pinfunction "2_2") (pintype "passive"))
      (node (ref "R231") (pin "2") (pinfunction "2_2") (pintype "passive"))
      (node (ref "R232") (pin "2") (pinfunction "2_2") (pintype "passive"))
      (node (ref "R233") (pin "2") (pinfunction "2_2") (pintype "passive"))
      (node (ref "R234") (pin "2") (pinfunction "2_2") (pintype "passive"))
      (node (ref "R235") (pin "2") (pinfunction "2_2") (pintype "passive"))
      (node (ref "R236") (pin "2") (pinfunction "2_2") (pintype "passive"))
      (node (ref "R237") (pin "2") (pinfunction "2_2") (pintype "passive"))
      (node (ref "R238") (pin "2") (pinfunction "2_2") (pintype "passive"))
      (node (ref "R239") (pin "2") (pinfunction "2_2") (pintype "passive"))
      (node (ref "R24") (pin "2") (pinfunction "2_2") (pintype "passive"))
      (node (ref "R240") (pin "2") (pinfunction "2_2") (pintype "passive"))
      (node (ref "R241") (pin "2") (pinfunction "2_2") (pintype "passive"))
      (node (ref "R243") (pin "2") (pinfunction "2_2") (pintype "passive"))
      (node (ref "R244") (pin "2") (pinfunction "2_2") (pintype "passive"))
      (node (ref "R245") (pin "2") (pinfunction "2_2") (pintype "passive"))
      (node (ref "R246") (pin "2") (pinfunction "2_2") (pintype "passive"))
      (node (ref "R247") (pin "2") (pinfunction "2_2") (pintype "passive"))
      (node (ref "R248") (pin "2") (pinfunction "2_2") (pintype "passive"))
      (node (ref "R25") (pin "2") (pinfunction "2_2") (pintype "passive"))
      (node (ref "R253") (pin "2") (pinfunction "2_2") (pintype "passive"))
      (node (ref "R254") (pin "2") (pinfunction "2_2") (pintype "passive"))
      (node (ref "R255") (pin "2") (pinfunction "2_2") (pintype "passive"))
      (node (ref "R256") (pin "2") (pinfunction "2_2") (pintype "passive"))
      (node (ref "R257") (pin "2") (pinfunction "2_2") (pintype "passive"))
      (node (ref "R258") (pin "2") (pinfunction "2_2") (pintype "passive"))
      (node (ref "R259") (pin "2") (pinfunction "2_2") (pintype "passive"))
      (node (ref "R26") (pin "2") (pinfunction "2_2") (pintype "passive"))
      (node (ref "R260") (pin "2") (pinfunction "2_2") (pintype "passive"))
      (node (ref "R27") (pin "2") (pinfunction "2_2") (pintype "passive"))
      (node (ref "R28") (pin "2") (pinfunction "2_2") (pintype "passive"))
      (node (ref "R29") (pin "2") (pinfunction "2_2") (pintype "passive"))
      (node (ref "R3") (pin "2") (pinfunction "2_2") (pintype "passive"))
      (node (ref "R30") (pin "2") (pinfunction "2_2") (pintype "passive"))
      (node (ref "R31") (pin "2") (pinfunction "2_2") (pintype "passive"))
      (node (ref "R32") (pin "2") (pinfunction "2_2") (pintype "passive"))
      (node (ref "R33") (pin "2") (pinfunction "2_2") (pintype "passive"))
      (node (ref "R34") (pin "2") (pinfunction "2_2") (pintype "passive"))
      (node (ref "R35") (pin "2") (pinfunction "2_2") (pintype "passive"))
      (node (ref "R36") (pin "2") (pinfunction "2_2") (pintype "passive"))
      (node (ref "R37") (pin "2") (pinfunction "2_2") (pintype "passive"))
      (node (ref "R38") (pin "2") (pinfunction "2_2") (pintype "passive"))
      (node (ref "R39") (pin "2") (pinfunction "2_2") (pintype "passive"))
      (node (ref "R40") (pin "2") (pinfunction "2_2") (pintype "passive"))
      (node (ref "R41") (pin "2") (pinfunction "2_2") (pintype "passive"))
      (node (ref "R42") (pin "2") (pinfunction "2_2") (pintype "passive"))
      (node (ref "R43") (pin "2") (pinfunction "2_2") (pintype "passive"))
      (node (ref "R44") (pin "2") (pinfunction "2_2") (pintype "passive"))
      (node (ref "R45") (pin "2") (pinfunction "2_2") (pintype "passive"))
      (node (ref "R46") (pin "2") (pinfunction "2_2") (pintype "passive"))
      (node (ref "R47") (pin "2") (pinfunction "2_2") (pintype "passive"))
      (node (ref "R48") (pin "2") (pinfunction "2_2") (pintype "passive"))
      (node (ref "R49") (pin "2") (pinfunction "2_2") (pintype "passive"))
      (node (ref "R5") (pin "2") (pinfunction "2_2") (pintype "passive"))
      (node (ref "R50") (pin "2") (pinfunction "2_2") (pintype "passive"))
      (node (ref "R51") (pin "2") (pinfunction "2_2") (pintype "passive"))
      (node (ref "R53") (pin "2") (pinfunction "2_2") (pintype "passive"))
      (node (ref "R55") (pin "2") (pinfunction "2_2") (pintype "passive"))
      (node (ref "R57") (pin "2") (pinfunction "2_2") (pintype "passive"))
      (node (ref "R59") (pin "2") (pinfunction "2_2") (pintype "passive"))
      (node (ref "R61") (pin "2") (pinfunction "2_2") (pintype "passive"))
      (node (ref "R63") (pin "2") (pinfunction "2_2") (pintype "passive"))
      (node (ref "R65") (pin "2") (pinfunction "2_2") (pintype "passive"))
      (node (ref "R67") (pin "2") (pinfunction "2_2") (pintype "passive"))
      (node (ref "R68") (pin "2") (pinfunction "2_2") (pintype "passive"))
      (node (ref "R69") (pin "2") (pinfunction "2_2") (pintype "passive"))
      (node (ref "R7") (pin "2") (pinfunction "2_2") (pintype "passive"))
      (node (ref "R70") (pin "2") (pinfunction "2_2") (pintype "passive"))
      (node (ref "R71") (pin "2") (pinfunction "2_2") (pintype "passive"))
      (node (ref "R72") (pin "2") (pinfunction "2_2") (pintype "passive"))
      (node (ref "R73") (pin "2") (pinfunction "2_2") (pintype "passive"))
      (node (ref "R74") (pin "2") (pinfunction "2_2") (pintype "passive"))
      (node (ref "R75") (pin "2") (pinfunction "2_2") (pintype "passive"))
      (node (ref "R76") (pin "2") (pinfunction "2_2") (pintype "passive"))
      (node (ref "R77") (pin "2") (pinfunction "2_2") (pintype "passive"))
      (node (ref "R78") (pin "2") (pinfunction "2_2") (pintype "passive"))
      (node (ref "R79") (pin "2") (pinfunction "2_2") (pintype "passive"))
      (node (ref "R80") (pin "2") (pinfunction "2_2") (pintype "passive"))
      (node (ref "R81") (pin "2") (pinfunction "2_2") (pintype "passive"))
      (node (ref "R82") (pin "2") (pinfunction "2_2") (pintype "passive"))
      (node (ref "R83") (pin "2") (pinfunction "2_2") (pintype "passive"))
      (node (ref "R84") (pin "2") (pinfunction "2_2") (pintype "passive"))
      (node (ref "R85") (pin "2") (pinfunction "2_2") (pintype "passive"))
      (node (ref "R86") (pin "2") (pinfunction "2_2") (pintype "passive"))
      (node (ref "R87") (pin "2") (pinfunction "2_2") (pintype "passive"))
      (node (ref "R88") (pin "2") (pinfunction "2_2") (pintype "passive"))
      (node (ref "R89") (pin "2") (pinfunction "2_2") (pintype "passive"))
      (node (ref "R9") (pin "2") (pinfunction "2_2") (pintype "passive"))
      (node (ref "R90") (pin "2") (pinfunction "2_2") (pintype "passive"))
      (node (ref "R91") (pin "2") (pinfunction "2_2") (pintype "passive"))
      (node (ref "R92") (pin "2") (pinfunction "2_2") (pintype "passive"))
      (node (ref "R93") (pin "2") (pinfunction "2_2") (pintype "passive"))
      (node (ref "R94") (pin "2") (pinfunction "2_2") (pintype "passive"))
      (node (ref "R95") (pin "2") (pinfunction "2_2") (pintype "passive"))
      (node (ref "R96") (pin "2") (pinfunction "2_2") (pintype "passive"))
      (node (ref "R97") (pin "2") (pinfunction "2_2") (pintype "passive"))
      (node (ref "R98") (pin "2") (pinfunction "2_2") (pintype "passive"))
      (node (ref "R99") (pin "2") (pinfunction "2_2") (pintype "passive"))
      (node (ref "TP5") (pin "1") (pinfunction "P$1_1") (pintype "bidirectional"))
    )
    (net (code "2") (name "A0") (class "Default")
      (node (ref "J10") (pin "5") (pinfunction "5_5") (pintype "bidirectional"))
      (node (ref "Q217") (pin "G") (pinfunction "G_G") (pintype "passive"))
    )
    (net (code "3") (name "A0_N") (class "Default")
      (node (ref "J12") (pin "1") (pinfunction "1_1") (pintype "passive"))
      (node (ref "Q17") (pin "G") (pinfunction "G_G") (pintype "passive"))
      (node (ref "Q217") (pin "D") (pinfunction "D_D") (pintype "passive"))
      (node (ref "Q69") (pin "G") (pinfunction "G_G") (pintype "passive"))
      (node (ref "R225") (pin "1") (pinfunction "1_1") (pintype "passive"))
    )
    (net (code "4") (name "A1") (class "Default")
      (node (ref "J10") (pin "6") (pinfunction "6_6") (pintype "bidirectional"))
      (node (ref "Q218") (pin "G") (pinfunction "G_G") (pintype "passive"))
    )
    (net (code "5") (name "A1_N") (class "Default")
      (node (ref "J12") (pin "2") (pinfunction "2_2") (pintype "passive"))
      (node (ref "Q18") (pin "G") (pinfunction "G_G") (pintype "passive"))
      (node (ref "Q218") (pin "D") (pinfunction "D_D") (pintype "passive"))
      (node (ref "Q70") (pin "G") (pinfunction "G_G") (pintype "passive"))
      (node (ref "R226") (pin "1") (pinfunction "1_1") (pintype "passive"))
    )
    (net (code "6") (name "A2") (class "Default")
      (node (ref "J10") (pin "7") (pinfunction "7_7") (pintype "bidirectional"))
      (node (ref "Q219") (pin "G") (pinfunction "G_G") (pintype "passive"))
    )
    (net (code "7") (name "A2_N") (class "Default")
      (node (ref "J12") (pin "3") (pinfunction "3_3") (pintype "passive"))
      (node (ref "Q19") (pin "G") (pinfunction "G_G") (pintype "passive"))
      (node (ref "Q219") (pin "D") (pinfunction "D_D") (pintype "passive"))
      (node (ref "Q71") (pin "G") (pinfunction "G_G") (pintype "passive"))
      (node (ref "R227") (pin "1") (pinfunction "1_1") (pintype "passive"))
    )
    (net (code "8") (name "A3") (class "Default")
      (node (ref "J10") (pin "8") (pinfunction "8_8") (pintype "bidirectional"))
      (node (ref "Q220") (pin "G") (pinfunction "G_G") (pintype "passive"))
    )
    (net (code "9") (name "A3_N") (class "Default")
      (node (ref "J12") (pin "4") (pinfunction "4_4") (pintype "passive"))
      (node (ref "Q20") (pin "G") (pinfunction "G_G") (pintype "passive"))
      (node (ref "Q220") (pin "D") (pinfunction "D_D") (pintype "passive"))
      (node (ref "Q72") (pin "G") (pinfunction "G_G") (pintype "passive"))
      (node (ref "R228") (pin "1") (pinfunction "1_1") (pintype "passive"))
    )
    (net (code "10") (name "A4") (class "Default")
      (node (ref "J10") (pin "9") (pinfunction "9_9") (pintype "bidirectional"))
      (node (ref "Q221") (pin "G") (pinfunction "G_G") (pintype "passive"))
    )
    (net (code "11") (name "A4_N") (class "Default")
      (node (ref "J12") (pin "5") (pinfunction "5_5") (pintype "passive"))
      (node (ref "Q21") (pin "G") (pinfunction "G_G") (pintype "passive"))
      (node (ref "Q221") (pin "D") (pinfunction "D_D") (pintype "passive"))
      (node (ref "Q73") (pin "G") (pinfunction "G_G") (pintype "passive"))
      (node (ref "R229") (pin "1") (pinfunction "1_1") (pintype "passive"))
    )
    (net (code "12") (name "A5") (class "Default")
      (node (ref "J10") (pin "10") (pinfunction "10_10") (pintype "bidirectional"))
      (node (ref "Q222") (pin "G") (pinfunction "G_G") (pintype "passive"))
    )
    (net (code "13") (name "A5_N") (class "Default")
      (node (ref "J12") (pin "6") (pinfunction "6_6") (pintype "passive"))
      (node (ref "Q22") (pin "G") (pinfunction "G_G") (pintype "passive"))
      (node (ref "Q222") (pin "D") (pinfunction "D_D") (pintype "passive"))
      (node (ref "Q74") (pin "G") (pinfunction "G_G") (pintype "passive"))
      (node (ref "R230") (pin "1") (pinfunction "1_1") (pintype "passive"))
    )
    (net (code "14") (name "A6") (class "Default")
      (node (ref "J10") (pin "11") (pinfunction "11_11") (pintype "bidirectional"))
      (node (ref "Q223") (pin "G") (pinfunction "G_G") (pintype "passive"))
    )
    (net (code "15") (name "A6_N") (class "Default")
      (node (ref "J12") (pin "7") (pinfunction "7_7") (pintype "passive"))
      (node (ref "Q223") (pin "D") (pinfunction "D_D") (pintype "passive"))
      (node (ref "Q33") (pin "G") (pinfunction "G_G") (pintype "passive"))
      (node (ref "Q75") (pin "G") (pinfunction "G_G") (pintype "passive"))
      (node (ref "R231") (pin "1") (pinfunction "1_1") (pintype "passive"))
    )
    (net (code "16") (name "A7") (class "Default")
      (node (ref "J10") (pin "12") (pinfunction "12_12") (pintype "bidirectional"))
      (node (ref "Q224") (pin "G") (pinfunction "G_G") (pintype "passive"))
    )
    (net (code "17") (name "A7_N") (class "Default")
      (node (ref "J12") (pin "8") (pinfunction "8_8") (pintype "passive"))
      (node (ref "Q224") (pin "D") (pinfunction "D_D") (pintype "passive"))
      (node (ref "Q34") (pin "G") (pinfunction "G_G") (pintype "passive"))
      (node (ref "Q76") (pin "G") (pinfunction "G_G") (pintype "passive"))
      (node (ref "R232") (pin "1") (pinfunction "1_1") (pintype "passive"))
    )
    (net (code "18") (name "A8") (class "Default")
      (node (ref "J10") (pin "13") (pinfunction "13_13") (pintype "bidirectional"))
      (node (ref "Q225") (pin "G") (pinfunction "G_G") (pintype "passive"))
    )
    (net (code "19") (name "A8_N") (class "Default")
      (node (ref "J12") (pin "9") (pinfunction "9_9") (pintype "passive"))
      (node (ref "Q225") (pin "D") (pinfunction "D_D") (pintype "passive"))
      (node (ref "Q35") (pin "G") (pinfunction "G_G") (pintype "passive"))
      (node (ref "Q77") (pin "G") (pinfunction "G_G") (pintype "passive"))
      (node (ref "R233") (pin "1") (pinfunction "1_1") (pintype "passive"))
    )
    (net (code "20") (name "A9") (class "Default")
      (node (ref "J10") (pin "14") (pinfunction "14_14") (pintype "bidirectional"))
      (node (ref "Q226") (pin "G") (pinfunction "G_G") (pintype "passive"))
    )
    (net (code "21") (name "A9_N") (class "Default")
      (node (ref "J12") (pin "10") (pinfunction "10_10") (pintype "passive"))
      (node (ref "Q226") (pin "D") (pinfunction "D_D") (pintype "passive"))
      (node (ref "Q36") (pin "G") (pinfunction "G_G") (pintype "passive"))
      (node (ref "Q78") (pin "G") (pinfunction "G_G") (pintype "passive"))
      (node (ref "R234") (pin "1") (pinfunction "1_1") (pintype "passive"))
    )
    (net (code "22") (name "A10") (class "Default")
      (node (ref "J10") (pin "15") (pinfunction "15_15") (pintype "bidirectional"))
      (node (ref "Q227") (pin "G") (pinfunction "G_G") (pintype "passive"))
    )
    (net (code "23") (name "A10_N") (class "Default")
      (node (ref "J12") (pin "11") (pinfunction "11_11") (pintype "passive"))
      (node (ref "Q227") (pin "D") (pinfunction "D_D") (pintype "passive"))
      (node (ref "Q37") (pin "G") (pinfunction "G_G") (pintype "passive"))
      (node (ref "Q79") (pin "G") (pinfunction "G_G") (pintype "passive"))
      (node (ref "R235") (pin "1") (pinfunction "1_1") (pintype "passive"))
    )
    (net (code "24") (name "A11") (class "Default")
      (node (ref "J10") (pin "16") (pinfunction "16_16") (pintype "bidirectional"))
      (node (ref "Q228") (pin "G") (pinfunction "G_G") (pintype "passive"))
    )
    (net (code "25") (name "A11_N") (class "Default")
      (node (ref "J12") (pin "12") (pinfunction "12_12") (pintype "passive"))
      (node (ref "Q228") (pin "D") (pinfunction "D_D") (pintype "passive"))
      (node (ref "Q38") (pin "G") (pinfunction "G_G") (pintype "passive"))
      (node (ref "Q80") (pin "G") (pinfunction "G_G") (pintype "passive"))
      (node (ref "R236") (pin "1") (pinfunction "1_1") (pintype "passive"))
    )
    (net (code "26") (name "A12") (class "Default")
      (node (ref "J10") (pin "17") (pinfunction "17_17") (pintype "bidirectional"))
      (node (ref "Q229") (pin "G") (pinfunction "G_G") (pintype "passive"))
    )
    (net (code "27") (name "A12_N") (class "Default")
      (node (ref "J12") (pin "13") (pinfunction "13_13") (pintype "passive"))
      (node (ref "Q229") (pin "D") (pinfunction "D_D") (pintype "passive"))
      (node (ref "Q39") (pin "G") (pinfunction "G_G") (pintype "passive"))
      (node (ref "Q81") (pin "G") (pinfunction "G_G") (pintype "passive"))
      (node (ref "R237") (pin "1") (pinfunction "1_1") (pintype "passive"))
    )
    (net (code "28") (name "A13") (class "Default")
      (node (ref "J10") (pin "18") (pinfunction "18_18") (pintype "bidirectional"))
      (node (ref "Q230") (pin "G") (pinfunction "G_G") (pintype "passive"))
    )
    (net (code "29") (name "A13_N") (class "Default")
      (node (ref "J12") (pin "14") (pinfunction "14_14") (pintype "passive"))
      (node (ref "Q230") (pin "D") (pinfunction "D_D") (pintype "passive"))
      (node (ref "Q40") (pin "G") (pinfunction "G_G") (pintype "passive"))
      (node (ref "Q82") (pin "G") (pinfunction "G_G") (pintype "passive"))
      (node (ref "R238") (pin "1") (pinfunction "1_1") (pintype "passive"))
    )
    (net (code "30") (name "A14") (class "Default")
      (node (ref "J10") (pin "19") (pinfunction "19_19") (pintype "bidirectional"))
      (node (ref "Q231") (pin "G") (pinfunction "G_G") (pintype "passive"))
    )
    (net (code "31") (name "A14_N") (class "Default")
      (node (ref "J12") (pin "15") (pinfunction "15_15") (pintype "passive"))
      (node (ref "Q231") (pin "D") (pinfunction "D_D") (pintype "passive"))
      (node (ref "Q41") (pin "G") (pinfunction "G_G") (pintype "passive"))
      (node (ref "Q83") (pin "G") (pinfunction "G_G") (pintype "passive"))
      (node (ref "R239") (pin "1") (pinfunction "1_1") (pintype "passive"))
    )
    (net (code "32") (name "A15") (class "Default")
      (node (ref "J10") (pin "20") (pinfunction "20_20") (pintype "bidirectional"))
      (node (ref "Q232") (pin "G") (pinfunction "G_G") (pintype "passive"))
    )
    (net (code "33") (name "A15_N") (class "Default")
      (node (ref "J12") (pin "16") (pinfunction "16_16") (pintype "passive"))
      (node (ref "Q232") (pin "D") (pinfunction "D_D") (pintype "passive"))
      (node (ref "Q42") (pin "G") (pinfunction "G_G") (pintype "passive"))
      (node (ref "Q84") (pin "G") (pinfunction "G_G") (pintype "passive"))
      (node (ref "R240") (pin "1") (pinfunction "1_1") (pintype "passive"))
    )
    (net (code "34") (name "CS") (class "Default")
      (node (ref "Q235") (pin "D") (pinfunction "D_D") (pintype "passive"))
      (node (ref "Q239") (pin "G") (pinfunction "G_G") (pintype "passive"))
      (node (ref "Q243") (pin "G") (pinfunction "G_G") (pintype "passive"))
      (node (ref "R243") (pin "1") (pinfunction "1_1") (pintype "passive"))
    )
    (net (code "35") (name "CS_0_N") (class "Default")
      (node (ref "Q10") (pin "S") (pinfunction "S_S") (pintype "passive"))
      (node (ref "Q12") (pin "S") (pinfunction "S_S") (pintype "passive"))
      (node (ref "Q14") (pin "S") (pinfunction "S_S") (pintype "passive"))
      (node (ref "Q16") (pin "S") (pinfunction "S_S") (pintype "passive"))
      (node (ref "Q2") (pin "S") (pinfunction "S_S") (pintype "passive"))
      (node (ref "Q237") (pin "D") (pinfunction "D_D") (pintype "passive"))
      (node (ref "Q240") (pin "G") (pinfunction "G_G") (pintype "passive"))
      (node (ref "Q4") (pin "S") (pinfunction "S_S") (pintype "passive"))
      (node (ref "Q6") (pin "S") (pinfunction "S_S") (pintype "passive"))
      (node (ref "Q8") (pin "S") (pinfunction "S_S") (pintype "passive"))
      (node (ref "R245") (pin "1") (pinfunction "1_1") (pintype "passive"))
    )
    (net (code "36") (name "CS_1_N") (class "Default")
      (node (ref "Q241") (pin "D") (pinfunction "D_D") (pintype "passive"))
      (node (ref "Q244") (pin "G") (pinfunction "G_G") (pintype "passive"))
      (node (ref "Q44") (pin "S") (pinfunction "S_S") (pintype "passive"))
      (node (ref "Q46") (pin "S") (pinfunction "S_S") (pintype "passive"))
      (node (ref "Q48") (pin "S") (pinfunction "S_S") (pintype "passive"))
      (node (ref "Q50") (pin "S") (pinfunction "S_S") (pintype "passive"))
      (node (ref "Q52") (pin "S") (pinfunction "S_S") (pintype "passive"))
      (node (ref "Q54") (pin "S") (pinfunction "S_S") (pintype "passive"))
      (node (ref "Q56") (pin "S") (pinfunction "S_S") (pintype "passive"))
      (node (ref "Q58") (pin "S") (pinfunction "S_S") (pintype "passive"))
      (node (ref "R247") (pin "1") (pinfunction "1_1") (pintype "passive"))
    )
    (net (code "37") (name "CS_N") (class "Default")
      (node (ref "J10") (pin "1") (pinfunction "1_1") (pintype "bidirectional"))
      (node (ref "Q235") (pin "G") (pinfunction "G_G") (pintype "passive"))
    )
    (net (code "38") (name "GND") (class "Default")
      (node (ref "C1") (pin "2") (pinfunction "2_2") (pintype "passive"))
      (node (ref "C2") (pin "2") (pinfunction "2_2") (pintype "passive"))
      (node (ref "C3") (pin "2") (pinfunction "2_2") (pintype "passive"))
      (node (ref "C4") (pin "2") (pinfunction "2_2") (pintype "passive"))
      (node (ref "C5") (pin "2") (pinfunction "2_2") (pintype "passive"))
      (node (ref "C6") (pin "2") (pinfunction "2_2") (pintype "passive"))
      (node (ref "C7") (pin "K") (pinfunction "K_K") (pintype "passive"))
      (node (ref "J1") (pin "1") (pinfunction "1_1") (pintype "bidirectional"))
      (node (ref "J1") (pin "10") (pinfunction "10_10") (pintype "bidirectional"))
      (node (ref "J1") (pin "11") (pinfunction "11_11") (pintype "bidirectional"))
      (node (ref "J1") (pin "20") (pinfunction "20_20") (pintype "bidirectional"))
      (node (ref "J10") (pin "2") (pinfunction "2_2") (pintype "bidirectional"))
      (node (ref "J10") (pin "4") (pinfunction "4_4") (pintype "bidirectional"))
      (node (ref "J2") (pin "2") (pinfunction "2_2") (pintype "bidirectional"))
      (node (ref "J2") (pin "4") (pinfunction "4_4") (pintype "bidirectional"))
      (node (ref "J3") (pin "1") (pinfunction "1_1") (pintype "bidirectional"))
      (node (ref "J3") (pin "10") (pinfunction "10_10") (pintype "bidirectional"))
      (node (ref "J3") (pin "11") (pinfunction "11_11") (pintype "bidirectional"))
      (node (ref "J3") (pin "20") (pinfunction "20_20") (pintype "bidirectional"))
      (node (ref "J4") (pin "2") (pinfunction "2_2") (pintype "bidirectional"))
      (node (ref "J4") (pin "4") (pinfunction "4_4") (pintype "bidirectional"))
      (node (ref "J9") (pin "1") (pinfunction "1_1") (pintype "bidirectional"))
      (node (ref "J9") (pin "10") (pinfunction "10_10") (pintype "bidirectional"))
      (node (ref "J9") (pin "11") (pinfunction "11_11") (pintype "bidirectional"))
      (node (ref "J9") (pin "20") (pinfunction "20_20") (pintype "bidirectional"))
      (node (ref "Q1") (pin "S") (pinfunction "S_S") (pintype "passive"))
      (node (ref "Q11") (pin "S") (pinfunction "S_S") (pintype "passive"))
      (node (ref "Q13") (pin "S") (pinfunction "S_S") (pintype "passive"))
      (node (ref "Q15") (pin "S") (pinfunction "S_S") (pintype "passive"))
      (node (ref "Q17") (pin "S") (pinfunction "S_S") (pintype "passive"))
      (node (ref "Q170") (pin "S") (pinfunction "S_S") (pintype "passive"))
      (node (ref "Q171") (pin "S") (pinfunction "S_S") (pintype "passive"))
      (node (ref "Q175") (pin "S") (pinfunction "S_S") (pintype "passive"))
      (node (ref "Q176") (pin "S") (pinfunction "S_S") (pintype "passive"))
      (node (ref "Q18") (pin "S") (pinfunction "S_S") (pintype "passive"))
      (node (ref "Q180") (pin "S") (pinfunction "S_S") (pintype "passive"))
      (node (ref "Q181") (pin "S") (pinfunction "S_S") (pintype "passive"))
      (node (ref "Q185") (pin "S") (pinfunction "S_S") (pintype "passive"))
      (node (ref "Q186") (pin "S") (pinfunction "S_S") (pintype "passive"))
      (node (ref "Q19") (pin "S") (pinfunction "S_S") (pintype "passive"))
      (node (ref "Q190") (pin "S") (pinfunction "S_S") (pintype "passive"))
      (node (ref "Q191") (pin "S") (pinfunction "S_S") (pintype "passive"))
      (node (ref "Q195") (pin "S") (pinfunction "S_S") (pintype "passive"))
      (node (ref "Q196") (pin "S") (pinfunction "S_S") (pintype "passive"))
      (node (ref "Q20") (pin "S") (pinfunction "S_S") (pintype "passive"))
      (node (ref "Q200") (pin "S") (pinfunction "S_S") (pintype "passive"))
      (node (ref "Q201") (pin "S") (pinfunction "S_S") (pintype "passive"))
      (node (ref "Q205") (pin "S") (pinfunction "S_S") (pintype "passive"))
      (node (ref "Q206") (pin "S") (pinfunction "S_S") (pintype "passive"))
      (node (ref "Q209") (pin "S") (pinfunction "S_S") (pintype "passive"))
      (node (ref "Q21") (pin "S") (pinfunction "S_S") (pintype "passive"))
      (node (ref "Q210") (pin "S") (pinfunction "S_S") (pintype "passive"))
      (node (ref "Q211") (pin "S") (pinfunction "S_S") (pintype "passive"))
      (node (ref "Q212") (pin "S") (pinfunction "S_S") (pintype "passive"))
      (node (ref "Q213") (pin "S") (pinfunction "S_S") (pintype "passive"))
      (node (ref "Q214") (pin "S") (pinfunction "S_S") (pintype "passive"))
      (node (ref "Q215") (pin "S") (pinfunction "S_S") (pintype "passive"))
      (node (ref "Q216") (pin "S") (pinfunction "S_S") (pintype "passive"))
      (node (ref "Q217") (pin "S") (pinfunction "S_S") (pintype "passive"))
      (node (ref "Q218") (pin "S") (pinfunction "S_S") (pintype "passive"))
      (node (ref "Q219") (pin "S") (pinfunction "S_S") (pintype "passive"))
      (node (ref "Q22") (pin "S") (pinfunction "S_S") (pintype "passive"))
      (node (ref "Q220") (pin "S") (pinfunction "S_S") (pintype "passive"))
      (node (ref "Q221") (pin "S") (pinfunction "S_S") (pintype "passive"))
      (node (ref "Q222") (pin "S") (pinfunction "S_S") (pintype "passive"))
      (node (ref "Q223") (pin "S") (pinfunction "S_S") (pintype "passive"))
      (node (ref "Q224") (pin "S") (pinfunction "S_S") (pintype "passive"))
      (node (ref "Q225") (pin "S") (pinfunction "S_S") (pintype "passive"))
      (node (ref "Q226") (pin "S") (pinfunction "S_S") (pintype "passive"))
      (node (ref "Q227") (pin "S") (pinfunction "S_S") (pintype "passive"))
      (node (ref "Q228") (pin "S") (pinfunction "S_S") (pintype "passive"))
      (node (ref "Q229") (pin "S") (pinfunction "S_S") (pintype "passive"))
      (node (ref "Q23") (pin "S") (pinfunction "S_S") (pintype "passive"))
      (node (ref "Q230") (pin "S") (pinfunction "S_S") (pintype "passive"))
      (node (ref "Q231") (pin "S") (pinfunction "S_S") (pintype "passive"))
      (node (ref "Q232") (pin "S") (pinfunction "S_S") (pintype "passive"))
      (node (ref "Q233") (pin "S") (pinfunction "S_S") (pintype "passive"))
      (node (ref "Q235") (pin "S") (pinfunction "S_S") (pintype "passive"))
      (node (ref "Q236") (pin "S") (pinfunction "S_S") (pintype "passive"))
      (node (ref "Q239") (pin "S") (pinfunction "S_S") (pintype "passive"))
      (node (ref "Q24") (pin "S") (pinfunction "S_S") (pintype "passive"))
      (node (ref "Q240") (pin "S") (pinfunction "S_S") (pintype "passive"))
      (node (ref "Q243") (pin "S") (pinfunction "S_S") (pintype "passive"))
      (node (ref "Q244") (pin "S") (pinfunction "S_S") (pintype "passive"))
      (node (ref "Q25") (pin "S") (pinfunction "S_S") (pintype "passive"))
      (node (ref "Q26") (pin "S") (pinfunction "S_S") (pintype "passive"))
      (node (ref "Q27") (pin "S") (pinfunction "S_S") (pintype "passive"))
      (node (ref "Q28") (pin "S") (pinfunction "S_S") (pintype "passive"))
      (node (ref "Q29") (pin "S") (pinfunction "S_S") (pintype "passive"))
      (node (ref "Q3") (pin "S") (pinfunction "S_S") (pintype "passive"))
      (node (ref "Q30") (pin "S") (pinfunction "S_S") (pintype "passive"))
      (node (ref "Q31") (pin "S") (pinfunction "S_S") (pintype "passive"))
      (node (ref "Q32") (pin "S") (pinfunction "S_S") (pintype "passive"))
      (node (ref "Q33") (pin "S") (pinfunction "S_S") (pintype "passive"))
      (node (ref "Q34") (pin "S") (pinfunction "S_S") (pintype "passive"))
      (node (ref "Q35") (pin "S") (pinfunction "S_S") (pintype "passive"))
      (node (ref "Q36") (pin "S") (pinfunction "S_S") (pintype "passive"))
      (node (ref "Q37") (pin "S") (pinfunction "S_S") (pintype "passive"))
      (node (ref "Q38") (pin "S") (pinfunction "S_S") (pintype "passive"))
      (node (ref "Q39") (pin "S") (pinfunction "S_S") (pintype "passive"))
      (node (ref "Q40") (pin "S") (pinfunction "S_S") (pintype "passive"))
      (node (ref "Q41") (pin "S") (pinfunction "S_S") (pintype "passive"))
      (node (ref "Q42") (pin "S") (pinfunction "S_S") (pintype "passive"))
      (node (ref "Q43") (pin "S") (pinfunction "S_S") (pintype "passive"))
      (node (ref "Q45") (pin "S") (pinfunction "S_S") (pintype "passive"))
      (node (ref "Q47") (pin "S") (pinfunction "S_S") (pintype "passive"))
      (node (ref "Q49") (pin "S") (pinfunction "S_S") (pintype "passive"))
      (node (ref "Q5") (pin "S") (pinfunction "S_S") (pintype "passive"))
      (node (ref "Q51") (pin "S") (pinfunction "S_S") (pintype "passive"))
      (node (ref "Q53") (pin "S") (pinfunction "S_S") (pintype "passive"))
      (node (ref "Q55") (pin "S") (pinfunction "S_S") (pintype "passive"))
      (node (ref "Q57") (pin "S") (pinfunction "S_S") (pintype "passive"))
      (node (ref "Q59") (pin "S") (pinfunction "S_S") (pintype "passive"))
      (node (ref "Q60") (pin "S") (pinfunction "S_S") (pintype "passive"))
      (node (ref "Q61") (pin "S") (pinfunction "S_S") (pintype "passive"))
      (node (ref "Q62") (pin "S") (pinfunction "S_S") (pintype "passive"))
      (node (ref "Q63") (pin "S") (pinfunction "S_S") (pintype "passive"))
      (node (ref "Q64") (pin "S") (pinfunction "S_S") (pintype "passive"))
      (node (ref "Q65") (pin "S") (pinfunction "S_S") (pintype "passive"))
      (node (ref "Q66") (pin "S") (pinfunction "S_S") (pintype "passive"))
      (node (ref "Q67") (pin "S") (pinfunction "S_S") (pintype "passive"))
      (node (ref "Q68") (pin "S") (pinfunction "S_S") (pintype "passive"))
      (node (ref "Q69") (pin "S") (pinfunction "S_S") (pintype "passive"))
      (node (ref "Q7") (pin "S") (pinfunction "S_S") (pintype "passive"))
      (node (ref "Q70") (pin "S") (pinfunction "S_S") (pintype "passive"))
      (node (ref "Q71") (pin "S") (pinfunction "S_S") (pintype "passive"))
      (node (ref "Q72") (pin "S") (pinfunction "S_S") (pintype "passive"))
      (node (ref "Q73") (pin "S") (pinfunction "S_S") (pintype "passive"))
      (node (ref "Q74") (pin "S") (pinfunction "S_S") (pintype "passive"))
      (node (ref "Q75") (pin "S") (pinfunction "S_S") (pintype "passive"))
      (node (ref "Q76") (pin "S") (pinfunction "S_S") (pintype "passive"))
      (node (ref "Q77") (pin "S") (pinfunction "S_S") (pintype "passive"))
      (node (ref "Q78") (pin "S") (pinfunction "S_S") (pintype "passive"))
      (node (ref "Q79") (pin "S") (pinfunction "S_S") (pintype "passive"))
      (node (ref "Q80") (pin "S") (pinfunction "S_S") (pintype "passive"))
      (node (ref "Q81") (pin "S") (pinfunction "S_S") (pintype "passive"))
      (node (ref "Q82") (pin "S") (pinfunction "S_S") (pintype "passive"))
      (node (ref "Q83") (pin "S") (pinfunction "S_S") (pintype "passive"))
      (node (ref "Q84") (pin "S") (pinfunction "S_S") (pintype "passive"))
      (node (ref "Q9") (pin "S") (pinfunction "S_S") (pintype "passive"))
      (node (ref "TP6") (pin "1") (pinfunction "P$1_1") (pintype "bidirectional"))
    )
    (net (code "39") (name "Net-(D1-C)") (class "Default")
      (node (ref "D1") (pin "K") (pinfunction "C_K") (pintype "passive"))
      (node (ref "R2") (pin "2") (pinfunction "2_2") (pintype "passive"))
    )
    (net (code "40") (name "Net-(D2-C)") (class "Default")
      (node (ref "D2") (pin "K") (pinfunction "C_K") (pintype "passive"))
      (node (ref "R4") (pin "2") (pinfunction "2_2") (pintype "passive"))
    )
    (net (code "41") (name "Net-(D3-C)") (class "Default")
      (node (ref "D3") (pin "K") (pinfunction "C_K") (pintype "passive"))
      (node (ref "R6") (pin "2") (pinfunction "2_2") (pintype "passive"))
    )
    (net (code "42") (name "Net-(D4-C)") (class "Default")
      (node (ref "D4") (pin "K") (pinfunction "C_K") (pintype "passive"))
      (node (ref "R8") (pin "2") (pinfunction "2_2") (pintype "passive"))
    )
    (net (code "43") (name "Net-(D5-C)") (class "Default")
      (node (ref "D5") (pin "K") (pinfunction "C_K") (pintype "passive"))
      (node (ref "R10") (pin "2") (pinfunction "2_2") (pintype "passive"))
    )
    (net (code "44") (name "Net-(D6-C)") (class "Default")
      (node (ref "D6") (pin "K") (pinfunction "C_K") (pintype "passive"))
      (node (ref "R12") (pin "2") (pinfunction "2_2") (pintype "passive"))
    )
    (net (code "45") (name "Net-(D7-C)") (class "Default")
      (node (ref "D7") (pin "K") (pinfunction "C_K") (pintype "passive"))
      (node (ref "R14") (pin "2") (pinfunction "2_2") (pintype "passive"))
    )
    (net (code "46") (name "Net-(D8-C)") (class "Default")
      (node (ref "D8") (pin "K") (pinfunction "C_K") (pintype "passive"))
      (node (ref "R16") (pin "2") (pinfunction "2_2") (pintype "passive"))
    )
    (net (code "47") (name "Net-(D9-C)") (class "Default")
      (node (ref "D9") (pin "K") (pinfunction "C_K") (pintype "passive"))
      (node (ref "R52") (pin "2") (pinfunction "2_2") (pintype "passive"))
    )
    (net (code "48") (name "Net-(D10-C)") (class "Default")
      (node (ref "D10") (pin "K") (pinfunction "C_K") (pintype "passive"))
      (node (ref "R54") (pin "2") (pinfunction "2_2") (pintype "passive"))
    )
    (net (code "49") (name "Net-(D11-C)") (class "Default")
      (node (ref "D11") (pin "K") (pinfunction "C_K") (pintype "passive"))
      (node (ref "R56") (pin "2") (pinfunction "2_2") (pintype "passive"))
    )
    (net (code "50") (name "Net-(D12-C)") (class "Default")
      (node (ref "D12") (pin "K") (pinfunction "C_K") (pintype "passive"))
      (node (ref "R58") (pin "2") (pinfunction "2_2") (pintype "passive"))
    )
    (net (code "51") (name "Net-(D13-C)") (class "Default")
      (node (ref "D13") (pin "K") (pinfunction "C_K") (pintype "passive"))
      (node (ref "R60") (pin "2") (pinfunction "2_2") (pintype "passive"))
    )
    (net (code "52") (name "Net-(D14-C)") (class "Default")
      (node (ref "D14") (pin "K") (pinfunction "C_K") (pintype "passive"))
      (node (ref "R62") (pin "2") (pinfunction "2_2") (pintype "passive"))
    )
    (net (code "53") (name "Net-(D15-C)") (class "Default")
      (node (ref "D15") (pin "K") (pinfunction "C_K") (pintype "passive"))
      (node (ref "R64") (pin "2") (pinfunction "2_2") (pintype "passive"))
    )
    (net (code "54") (name "Net-(D16-C)") (class "Default")
      (node (ref "D16") (pin "K") (pinfunction "C_K") (pintype "passive"))
      (node (ref "R66") (pin "2") (pinfunction "2_2") (pintype "passive"))
    )
    (net (code "55") (name "Net-(D33-C)") (class "Default")
      (node (ref "D33") (pin "K") (pinfunction "C_K") (pintype "passive"))
      (node (ref "R204") (pin "2") (pinfunction "2_2") (pintype "passive"))
    )
    (net (code "56") (name "Net-(D34-C)") (class "Default")
      (node (ref "D34") (pin "K") (pinfunction "C_K") (pintype "passive"))
      (node (ref "R206") (pin "2") (pinfunction "2_2") (pintype "passive"))
    )
    (net (code "57") (name "Net-(D35-C)") (class "Default")
      (node (ref "D35") (pin "K") (pinfunction "C_K") (pintype "passive"))
      (node (ref "R208") (pin "2") (pinfunction "2_2") (pintype "passive"))
    )
    (net (code "58") (name "Net-(D36-C)") (class "Default")
      (node (ref "D36") (pin "K") (pinfunction "C_K") (pintype "passive"))
      (node (ref "R210") (pin "2") (pinfunction "2_2") (pintype "passive"))
    )
    (net (code "59") (name "Net-(D37-C)") (class "Default")
      (node (ref "D37") (pin "K") (pinfunction "C_K") (pintype "passive"))
      (node (ref "R212") (pin "2") (pinfunction "2_2") (pintype "passive"))
    )
    (net (code "60") (name "Net-(D38-C)") (class "Default")
      (node (ref "D38") (pin "K") (pinfunction "C_K") (pintype "passive"))
      (node (ref "R214") (pin "2") (pinfunction "2_2") (pintype "passive"))
    )
    (net (code "61") (name "Net-(D39-C)") (class "Default")
      (node (ref "D39") (pin "K") (pinfunction "C_K") (pintype "passive"))
      (node (ref "R216") (pin "2") (pinfunction "2_2") (pintype "passive"))
    )
    (net (code "62") (name "Net-(D69-C)") (class "Default")
      (node (ref "D69") (pin "K") (pinfunction "C_K") (pintype "passive"))
      (node (ref "R202") (pin "2") (pinfunction "2_2") (pintype "passive"))
    )
    (net (code "63") (name "Net-(Q1-PadD)") (class "Default")
      (node (ref "Q1") (pin "D") (pinfunction "D_D") (pintype "passive"))
      (node (ref "Q2") (pin "G") (pinfunction "G_G") (pintype "passive"))
      (node (ref "R1") (pin "1") (pinfunction "1_1") (pintype "passive"))
      (node (ref "R2") (pin "1") (pinfunction "1_1") (pintype "passive"))
    )
    (net (code "64") (name "Net-(Q3-PadD)") (class "Default")
      (node (ref "Q3") (pin "D") (pinfunction "D_D") (pintype "passive"))
      (node (ref "Q4") (pin "G") (pinfunction "G_G") (pintype "passive"))
      (node (ref "R3") (pin "1") (pinfunction "1_1") (pintype "passive"))
      (node (ref "R4") (pin "1") (pinfunction "1_1") (pintype "passive"))
    )
    (net (code "65") (name "Net-(Q5-PadD)") (class "Default")
      (node (ref "Q5") (pin "D") (pinfunction "D_D") (pintype "passive"))
      (node (ref "Q6") (pin "G") (pinfunction "G_G") (pintype "passive"))
      (node (ref "R5") (pin "1") (pinfunction "1_1") (pintype "passive"))
      (node (ref "R6") (pin "1") (pinfunction "1_1") (pintype "passive"))
    )
    (net (code "66") (name "Net-(Q7-PadD)") (class "Default")
      (node (ref "Q7") (pin "D") (pinfunction "D_D") (pintype "passive"))
      (node (ref "Q8") (pin "G") (pinfunction "G_G") (pintype "passive"))
      (node (ref "R7") (pin "1") (pinfunction "1_1") (pintype "passive"))
      (node (ref "R8") (pin "1") (pinfunction "1_1") (pintype "passive"))
    )
    (net (code "67") (name "Net-(Q10-PadG)") (class "Default")
      (node (ref "Q10") (pin "G") (pinfunction "G_G") (pintype "passive"))
      (node (ref "Q9") (pin "D") (pinfunction "D_D") (pintype "passive"))
      (node (ref "R10") (pin "1") (pinfunction "1_1") (pintype "passive"))
      (node (ref "R9") (pin "1") (pinfunction "1_1") (pintype "passive"))
    )
    (net (code "68") (name "Net-(Q11-PadD)") (class "Default")
      (node (ref "Q11") (pin "D") (pinfunction "D_D") (pintype "passive"))
      (node (ref "Q12") (pin "G") (pinfunction "G_G") (pintype "passive"))
      (node (ref "R11") (pin "1") (pinfunction "1_1") (pintype "passive"))
      (node (ref "R12") (pin "1") (pinfunction "1_1") (pintype "passive"))
    )
    (net (code "69") (name "Net-(Q13-PadD)") (class "Default")
      (node (ref "Q13") (pin "D") (pinfunction "D_D") (pintype "passive"))
      (node (ref "Q14") (pin "G") (pinfunction "G_G") (pintype "passive"))
      (node (ref "R13") (pin "1") (pinfunction "1_1") (pintype "passive"))
      (node (ref "R14") (pin "1") (pinfunction "1_1") (pintype "passive"))
    )
    (net (code "70") (name "Net-(Q15-PadD)") (class "Default")
      (node (ref "Q15") (pin "D") (pinfunction "D_D") (pintype "passive"))
      (node (ref "Q16") (pin "G") (pinfunction "G_G") (pintype "passive"))
      (node (ref "R15") (pin "1") (pinfunction "1_1") (pintype "passive"))
      (node (ref "R16") (pin "1") (pinfunction "1_1") (pintype "passive"))
    )
    (net (code "71") (name "Net-(Q43-PadD)") (class "Default")
      (node (ref "Q43") (pin "D") (pinfunction "D_D") (pintype "passive"))
      (node (ref "Q44") (pin "G") (pinfunction "G_G") (pintype "passive"))
      (node (ref "R51") (pin "1") (pinfunction "1_1") (pintype "passive"))
      (node (ref "R52") (pin "1") (pinfunction "1_1") (pintype "passive"))
    )
    (net (code "72") (name "Net-(Q45-PadD)") (class "Default")
      (node (ref "Q45") (pin "D") (pinfunction "D_D") (pintype "passive"))
      (node (ref "Q46") (pin "G") (pinfunction "G_G") (pintype "passive"))
      (node (ref "R53") (pin "1") (pinfunction "1_1") (pintype "passive"))
      (node (ref "R54") (pin "1") (pinfunction "1_1") (pintype "passive"))
    )
    (net (code "73") (name "Net-(Q47-PadD)") (class "Default")
      (node (ref "Q47") (pin "D") (pinfunction "D_D") (pintype "passive"))
      (node (ref "Q48") (pin "G") (pinfunction "G_G") (pintype "passive"))
      (node (ref "R55") (pin "1") (pinfunction "1_1") (pintype "passive"))
      (node (ref "R56") (pin "1") (pinfunction "1_1") (pintype "passive"))
    )
    (net (code "74") (name "Net-(Q49-PadD)") (class "Default")
      (node (ref "Q49") (pin "D") (pinfunction "D_D") (pintype "passive"))
      (node (ref "Q50") (pin "G") (pinfunction "G_G") (pintype "passive"))
      (node (ref "R57") (pin "1") (pinfunction "1_1") (pintype "passive"))
      (node (ref "R58") (pin "1") (pinfunction "1_1") (pintype "passive"))
    )
    (net (code "75") (name "Net-(Q51-PadD)") (class "Default")
      (node (ref "Q51") (pin "D") (pinfunction "D_D") (pintype "passive"))
      (node (ref "Q52") (pin "G") (pinfunction "G_G") (pintype "passive"))
      (node (ref "R59") (pin "1") (pinfunction "1_1") (pintype "passive"))
      (node (ref "R60") (pin "1") (pinfunction "1_1") (pintype "passive"))
    )
    (net (code "76") (name "Net-(Q53-PadD)") (class "Default")
      (node (ref "Q53") (pin "D") (pinfunction "D_D") (pintype "passive"))
      (node (ref "Q54") (pin "G") (pinfunction "G_G") (pintype "passive"))
      (node (ref "R61") (pin "1") (pinfunction "1_1") (pintype "passive"))
      (node (ref "R62") (pin "1") (pinfunction "1_1") (pintype "passive"))
    )
    (net (code "77") (name "Net-(Q55-PadD)") (class "Default")
      (node (ref "Q55") (pin "D") (pinfunction "D_D") (pintype "passive"))
      (node (ref "Q56") (pin "G") (pinfunction "G_G") (pintype "passive"))
      (node (ref "R63") (pin "1") (pinfunction "1_1") (pintype "passive"))
      (node (ref "R64") (pin "1") (pinfunction "1_1") (pintype "passive"))
    )
    (net (code "78") (name "Net-(Q57-PadD)") (class "Default")
      (node (ref "Q57") (pin "D") (pinfunction "D_D") (pintype "passive"))
      (node (ref "Q58") (pin "G") (pinfunction "G_G") (pintype "passive"))
      (node (ref "R65") (pin "1") (pinfunction "1_1") (pintype "passive"))
      (node (ref "R66") (pin "1") (pinfunction "1_1") (pintype "passive"))
    )
    (net (code "79") (name "Net-(Q169-PadD)") (class "Default")
      (node (ref "Q169") (pin "D") (pinfunction "D_D") (pintype "passive"))
      (node (ref "Q170") (pin "G") (pinfunction "G_G") (pintype "passive"))
      (node (ref "R201") (pin "1") (pinfunction "1_1") (pintype "passive"))
      (node (ref "R202") (pin "1") (pinfunction "1_1") (pintype "passive"))
    )
    (net (code "80") (name "Net-(Q169-PadS)") (class "Default")
      (node (ref "Q169") (pin "S") (pinfunction "S_S") (pintype "passive"))
      (node (ref "Q171") (pin "D") (pinfunction "D_D") (pintype "passive"))
    )
    (net (code "81") (name "Net-(Q174-PadD)") (class "Default")
      (node (ref "Q174") (pin "D") (pinfunction "D_D") (pintype "passive"))
      (node (ref "Q175") (pin "G") (pinfunction "G_G") (pintype "passive"))
      (node (ref "R203") (pin "1") (pinfunction "1_1") (pintype "passive"))
      (node (ref "R204") (pin "1") (pinfunction "1_1") (pintype "passive"))
    )
    (net (code "82") (name "Net-(Q174-PadS)") (class "Default")
      (node (ref "Q174") (pin "S") (pinfunction "S_S") (pintype "passive"))
      (node (ref "Q176") (pin "D") (pinfunction "D_D") (pintype "passive"))
    )
    (net (code "83") (name "Net-(Q179-PadD)") (class "Default")
      (node (ref "Q179") (pin "D") (pinfunction "D_D") (pintype "passive"))
      (node (ref "Q180") (pin "G") (pinfunction "G_G") (pintype "passive"))
      (node (ref "R205") (pin "1") (pinfunction "1_1") (pintype "passive"))
      (node (ref "R206") (pin "1") (pinfunction "1_1") (pintype "passive"))
    )
    (net (code "84") (name "Net-(Q179-PadS)") (class "Default")
      (node (ref "Q179") (pin "S") (pinfunction "S_S") (pintype "passive"))
      (node (ref "Q181") (pin "D") (pinfunction "D_D") (pintype "passive"))
    )
    (net (code "85") (name "Net-(Q184-PadD)") (class "Default")
      (node (ref "Q184") (pin "D") (pinfunction "D_D") (pintype "passive"))
      (node (ref "Q185") (pin "G") (pinfunction "G_G") (pintype "passive"))
      (node (ref "R207") (pin "1") (pinfunction "1_1") (pintype "passive"))
      (node (ref "R208") (pin "1") (pinfunction "1_1") (pintype "passive"))
    )
    (net (code "86") (name "Net-(Q184-PadS)") (class "Default")
      (node (ref "Q184") (pin "S") (pinfunction "S_S") (pintype "passive"))
      (node (ref "Q186") (pin "D") (pinfunction "D_D") (pintype "passive"))
    )
    (net (code "87") (name "Net-(Q189-PadD)") (class "Default")
      (node (ref "Q189") (pin "D") (pinfunction "D_D") (pintype "passive"))
      (node (ref "Q190") (pin "G") (pinfunction "G_G") (pintype "passive"))
      (node (ref "R209") (pin "1") (pinfunction "1_1") (pintype "passive"))
      (node (ref "R210") (pin "1") (pinfunction "1_1") (pintype "passive"))
    )
    (net (code "88") (name "Net-(Q189-PadS)") (class "Default")
      (node (ref "Q189") (pin "S") (pinfunction "S_S") (pintype "passive"))
      (node (ref "Q191") (pin "D") (pinfunction "D_D") (pintype "passive"))
    )
    (net (code "89") (name "Net-(Q194-PadD)") (class "Default")
      (node (ref "Q194") (pin "D") (pinfunction "D_D") (pintype "passive"))
      (node (ref "Q195") (pin "G") (pinfunction "G_G") (pintype "passive"))
      (node (ref "R211") (pin "1") (pinfunction "1_1") (pintype "passive"))
      (node (ref "R212") (pin "1") (pinfunction "1_1") (pintype "passive"))
    )
    (net (code "90") (name "Net-(Q194-PadS)") (class "Default")
      (node (ref "Q194") (pin "S") (pinfunction "S_S") (pintype "passive"))
      (node (ref "Q196") (pin "D") (pinfunction "D_D") (pintype "passive"))
    )
    (net (code "91") (name "Net-(Q199-PadD)") (class "Default")
      (node (ref "Q199") (pin "D") (pinfunction "D_D") (pintype "passive"))
      (node (ref "Q200") (pin "G") (pinfunction "G_G") (pintype "passive"))
      (node (ref "R213") (pin "1") (pinfunction "1_1") (pintype "passive"))
      (node (ref "R214") (pin "1") (pinfunction "1_1") (pintype "passive"))
    )
    (net (code "92") (name "Net-(Q199-PadS)") (class "Default")
      (node (ref "Q199") (pin "S") (pinfunction "S_S") (pintype "passive"))
      (node (ref "Q201") (pin "D") (pinfunction "D_D") (pintype "passive"))
    )
    (net (code "93") (name "Net-(Q204-PadD)") (class "Default")
      (node (ref "Q204") (pin "D") (pinfunction "D_D") (pintype "passive"))
      (node (ref "Q205") (pin "G") (pinfunction "G_G") (pintype "passive"))
      (node (ref "R215") (pin "1") (pinfunction "1_1") (pintype "passive"))
      (node (ref "R216") (pin "1") (pinfunction "1_1") (pintype "passive"))
    )
    (net (code "94") (name "Net-(Q204-PadS)") (class "Default")
      (node (ref "Q204") (pin "S") (pinfunction "S_S") (pintype "passive"))
      (node (ref "Q206") (pin "D") (pinfunction "D_D") (pintype "passive"))
    )
    (net (code "95") (name "Net-(Q237-PadS)") (class "Default")
      (node (ref "Q237") (pin "S") (pinfunction "S_S") (pintype "passive"))
      (node (ref "Q239") (pin "D") (pinfunction "D_D") (pintype "passive"))
    )
    (net (code "96") (name "Net-(Q241-PadS)") (class "Default")
      (node (ref "Q241") (pin "S") (pinfunction "S_S") (pintype "passive"))
      (node (ref "Q243") (pin "D") (pinfunction "D_D") (pintype "passive"))
    )
    (net (code "97") (name "P0_A0") (class "Default")
      (node (ref "J2") (pin "5") (pinfunction "5_5") (pintype "bidirectional"))
      (node (ref "Q17") (pin "D") (pinfunction "D_D") (pintype "passive"))
      (node (ref "R25") (pin "1") (pinfunction "1_1") (pintype "passive"))
    )
    (net (code "98") (name "P0_A1") (class "Default")
      (node (ref "J2") (pin "6") (pinfunction "6_6") (pintype "bidirectional"))
      (node (ref "Q18") (pin "D") (pinfunction "D_D") (pintype "passive"))
      (node (ref "R26") (pin "1") (pinfunction "1_1") (pintype "passive"))
    )
    (net (code "99") (name "P0_A2") (class "Default")
      (node (ref "J2") (pin "7") (pinfunction "7_7") (pintype "bidirectional"))
      (node (ref "Q19") (pin "D") (pinfunction "D_D") (pintype "passive"))
      (node (ref "R27") (pin "1") (pinfunction "1_1") (pintype "passive"))
    )
    (net (code "100") (name "P0_A3") (class "Default")
      (node (ref "J2") (pin "8") (pinfunction "8_8") (pintype "bidirectional"))
      (node (ref "Q20") (pin "D") (pinfunction "D_D") (pintype "passive"))
      (node (ref "R28") (pin "1") (pinfunction "1_1") (pintype "passive"))
    )
    (net (code "101") (name "P0_A4") (class "Default")
      (node (ref "J2") (pin "9") (pinfunction "9_9") (pintype "bidirectional"))
      (node (ref "Q21") (pin "D") (pinfunction "D_D") (pintype "passive"))
      (node (ref "R29") (pin "1") (pinfunction "1_1") (pintype "passive"))
    )
    (net (code "102") (name "P0_A5") (class "Default")
      (node (ref "J2") (pin "10") (pinfunction "10_10") (pintype "bidirectional"))
      (node (ref "Q22") (pin "D") (pinfunction "D_D") (pintype "passive"))
      (node (ref "R30") (pin "1") (pinfunction "1_1") (pintype "passive"))
    )
    (net (code "103") (name "P0_A6") (class "Default")
      (node (ref "J2") (pin "11") (pinfunction "11_11") (pintype "bidirectional"))
      (node (ref "Q33") (pin "D") (pinfunction "D_D") (pintype "passive"))
      (node (ref "R41") (pin "1") (pinfunction "1_1") (pintype "passive"))
    )
    (net (code "104") (name "P0_A7") (class "Default")
      (node (ref "J2") (pin "12") (pinfunction "12_12") (pintype "bidirectional"))
      (node (ref "Q34") (pin "D") (pinfunction "D_D") (pintype "passive"))
      (node (ref "R42") (pin "1") (pinfunction "1_1") (pintype "passive"))
    )
    (net (code "105") (name "P0_A8") (class "Default")
      (node (ref "J2") (pin "13") (pinfunction "13_13") (pintype "bidirectional"))
      (node (ref "Q35") (pin "D") (pinfunction "D_D") (pintype "passive"))
      (node (ref "R43") (pin "1") (pinfunction "1_1") (pintype "passive"))
    )
    (net (code "106") (name "P0_A9") (class "Default")
      (node (ref "J2") (pin "14") (pinfunction "14_14") (pintype "bidirectional"))
      (node (ref "Q36") (pin "D") (pinfunction "D_D") (pintype "passive"))
      (node (ref "R44") (pin "1") (pinfunction "1_1") (pintype "passive"))
    )
    (net (code "107") (name "P0_A10") (class "Default")
      (node (ref "J2") (pin "15") (pinfunction "15_15") (pintype "bidirectional"))
      (node (ref "Q37") (pin "D") (pinfunction "D_D") (pintype "passive"))
      (node (ref "R45") (pin "1") (pinfunction "1_1") (pintype "passive"))
    )
    (net (code "108") (name "P0_A11") (class "Default")
      (node (ref "J2") (pin "16") (pinfunction "16_16") (pintype "bidirectional"))
      (node (ref "Q38") (pin "D") (pinfunction "D_D") (pintype "passive"))
      (node (ref "R46") (pin "1") (pinfunction "1_1") (pintype "passive"))
    )
    (net (code "109") (name "P0_A12") (class "Default")
      (node (ref "J2") (pin "17") (pinfunction "17_17") (pintype "bidirectional"))
      (node (ref "Q39") (pin "D") (pinfunction "D_D") (pintype "passive"))
      (node (ref "R47") (pin "1") (pinfunction "1_1") (pintype "passive"))
    )
    (net (code "110") (name "P0_A13") (class "Default")
      (node (ref "J2") (pin "18") (pinfunction "18_18") (pintype "bidirectional"))
      (node (ref "Q40") (pin "D") (pinfunction "D_D") (pintype "passive"))
      (node (ref "R48") (pin "1") (pinfunction "1_1") (pintype "passive"))
    )
    (net (code "111") (name "P0_A14") (class "Default")
      (node (ref "J2") (pin "19") (pinfunction "19_19") (pintype "bidirectional"))
      (node (ref "Q41") (pin "D") (pinfunction "D_D") (pintype "passive"))
      (node (ref "R49") (pin "1") (pinfunction "1_1") (pintype "passive"))
    )
    (net (code "112") (name "P0_A15") (class "Default")
      (node (ref "J2") (pin "20") (pinfunction "20_20") (pintype "bidirectional"))
      (node (ref "Q42") (pin "D") (pinfunction "D_D") (pintype "passive"))
      (node (ref "R50") (pin "1") (pinfunction "1_1") (pintype "passive"))
    )
    (net (code "113") (name "P0_CS") (class "Default")
      (node (ref "Q23") (pin "G") (pinfunction "G_G") (pintype "passive"))
      (node (ref "Q240") (pin "D") (pinfunction "D_D") (pintype "passive"))
      (node (ref "R246") (pin "1") (pinfunction "1_1") (pintype "passive"))
    )
    (net (code "114") (name "P0_CS_N") (class "Default")
      (node (ref "J2") (pin "1") (pinfunction "1_1") (pintype "bidirectional"))
      (node (ref "Q23") (pin "D") (pinfunction "D_D") (pintype "passive"))
      (node (ref "R31") (pin "1") (pinfunction "1_1") (pintype "passive"))
    )
    (net (code "115") (name "P0_RD0") (class "Default")
      (node (ref "J1") (pin "2") (pinfunction "2_2") (pintype "bidirectional"))
      (node (ref "Q1") (pin "G") (pinfunction "G_G") (pintype "passive"))
    )
    (net (code "116") (name "P0_RD0_B") (class "Default")
      (node (ref "Q169") (pin "G") (pinfunction "G_G") (pintype "passive"))
      (node (ref "Q2") (pin "D") (pinfunction "D_D") (pintype "passive"))
      (node (ref "R17") (pin "1") (pinfunction "1_1") (pintype "passive"))
    )
    (net (code "117") (name "P0_RD1") (class "Default")
      (node (ref "J1") (pin "3") (pinfunction "3_3") (pintype "bidirectional"))
      (node (ref "Q3") (pin "G") (pinfunction "G_G") (pintype "passive"))
    )
    (net (code "118") (name "P0_RD1_B") (class "Default")
      (node (ref "Q174") (pin "G") (pinfunction "G_G") (pintype "passive"))
      (node (ref "Q4") (pin "D") (pinfunction "D_D") (pintype "passive"))
      (node (ref "R18") (pin "1") (pinfunction "1_1") (pintype "passive"))
    )
    (net (code "119") (name "P0_RD2") (class "Default")
      (node (ref "J1") (pin "4") (pinfunction "4_4") (pintype "bidirectional"))
      (node (ref "Q5") (pin "G") (pinfunction "G_G") (pintype "passive"))
    )
    (net (code "120") (name "P0_RD2_B") (class "Default")
      (node (ref "Q179") (pin "G") (pinfunction "G_G") (pintype "passive"))
      (node (ref "Q6") (pin "D") (pinfunction "D_D") (pintype "passive"))
      (node (ref "R19") (pin "1") (pinfunction "1_1") (pintype "passive"))
    )
    (net (code "121") (name "P0_RD3") (class "Default")
      (node (ref "J1") (pin "5") (pinfunction "5_5") (pintype "bidirectional"))
      (node (ref "Q7") (pin "G") (pinfunction "G_G") (pintype "passive"))
    )
    (net (code "122") (name "P0_RD3_B") (class "Default")
      (node (ref "Q184") (pin "G") (pinfunction "G_G") (pintype "passive"))
      (node (ref "Q8") (pin "D") (pinfunction "D_D") (pintype "passive"))
      (node (ref "R20") (pin "1") (pinfunction "1_1") (pintype "passive"))
    )
    (net (code "123") (name "P0_RD4") (class "Default")
      (node (ref "J1") (pin "6") (pinfunction "6_6") (pintype "bidirectional"))
      (node (ref "Q9") (pin "G") (pinfunction "G_G") (pintype "passive"))
    )
    (net (code "124") (name "P0_RD4_B") (class "Default")
      (node (ref "Q10") (pin "D") (pinfunction "D_D") (pintype "passive"))
      (node (ref "Q189") (pin "G") (pinfunction "G_G") (pintype "passive"))
      (node (ref "R21") (pin "1") (pinfunction "1_1") (pintype "passive"))
    )
    (net (code "125") (name "P0_RD5") (class "Default")
      (node (ref "J1") (pin "7") (pinfunction "7_7") (pintype "bidirectional"))
      (node (ref "Q11") (pin "G") (pinfunction "G_G") (pintype "passive"))
    )
    (net (code "126") (name "P0_RD5_B") (class "Default")
      (node (ref "Q12") (pin "D") (pinfunction "D_D") (pintype "passive"))
      (node (ref "Q194") (pin "G") (pinfunction "G_G") (pintype "passive"))
      (node (ref "R22") (pin "1") (pinfunction "1_1") (pintype "passive"))
    )
    (net (code "127") (name "P0_RD6") (class "Default")
      (node (ref "J1") (pin "8") (pinfunction "8_8") (pintype "bidirectional"))
      (node (ref "Q13") (pin "G") (pinfunction "G_G") (pintype "passive"))
    )
    (net (code "128") (name "P0_RD6_B") (class "Default")
      (node (ref "Q14") (pin "D") (pinfunction "D_D") (pintype "passive"))
      (node (ref "Q199") (pin "G") (pinfunction "G_G") (pintype "passive"))
      (node (ref "R23") (pin "1") (pinfunction "1_1") (pintype "passive"))
    )
    (net (code "129") (name "P0_RD7") (class "Default")
      (node (ref "J1") (pin "9") (pinfunction "9_9") (pintype "bidirectional"))
      (node (ref "Q15") (pin "G") (pinfunction "G_G") (pintype "passive"))
    )
    (net (code "130") (name "P0_RD7_B") (class "Default")
      (node (ref "Q16") (pin "D") (pinfunction "D_D") (pintype "passive"))
      (node (ref "Q204") (pin "G") (pinfunction "G_G") (pintype "passive"))
      (node (ref "R24") (pin "1") (pinfunction "1_1") (pintype "passive"))
    )
    (net (code "131") (name "P0_WD0") (class "Default")
      (node (ref "J1") (pin "12") (pinfunction "12_12") (pintype "bidirectional"))
      (node (ref "Q25") (pin "D") (pinfunction "D_D") (pintype "passive"))
      (node (ref "R33") (pin "1") (pinfunction "1_1") (pintype "passive"))
    )
    (net (code "132") (name "P0_WD1") (class "Default")
      (node (ref "J1") (pin "13") (pinfunction "13_13") (pintype "bidirectional"))
      (node (ref "Q26") (pin "D") (pinfunction "D_D") (pintype "passive"))
      (node (ref "R34") (pin "1") (pinfunction "1_1") (pintype "passive"))
    )
    (net (code "133") (name "P0_WD2") (class "Default")
      (node (ref "J1") (pin "14") (pinfunction "14_14") (pintype "bidirectional"))
      (node (ref "Q27") (pin "D") (pinfunction "D_D") (pintype "passive"))
      (node (ref "R35") (pin "1") (pinfunction "1_1") (pintype "passive"))
    )
    (net (code "134") (name "P0_WD3") (class "Default")
      (node (ref "J1") (pin "15") (pinfunction "15_15") (pintype "bidirectional"))
      (node (ref "Q28") (pin "D") (pinfunction "D_D") (pintype "passive"))
      (node (ref "R36") (pin "1") (pinfunction "1_1") (pintype "passive"))
    )
    (net (code "135") (name "P0_WD4") (class "Default")
      (node (ref "J1") (pin "16") (pinfunction "16_16") (pintype "bidirectional"))
      (node (ref "Q29") (pin "D") (pinfunction "D_D") (pintype "passive"))
      (node (ref "R37") (pin "1") (pinfunction "1_1") (pintype "passive"))
    )
    (net (code "136") (name "P0_WD5") (class "Default")
      (node (ref "J1") (pin "17") (pinfunction "17_17") (pintype "bidirectional"))
      (node (ref "Q30") (pin "D") (pinfunction "D_D") (pintype "passive"))
      (node (ref "R38") (pin "1") (pinfunction "1_1") (pintype "passive"))
    )
    (net (code "137") (name "P0_WD6") (class "Default")
      (node (ref "J1") (pin "18") (pinfunction "18_18") (pintype "bidirectional"))
      (node (ref "Q31") (pin "D") (pinfunction "D_D") (pintype "passive"))
      (node (ref "R39") (pin "1") (pinfunction "1_1") (pintype "passive"))
    )
    (net (code "138") (name "P0_WD7") (class "Default")
      (node (ref "J1") (pin "19") (pinfunction "19_19") (pintype "bidirectional"))
      (node (ref "Q32") (pin "D") (pinfunction "D_D") (pintype "passive"))
      (node (ref "R40") (pin "1") (pinfunction "1_1") (pintype "passive"))
    )
    (net (code "139") (name "P0_WE_N") (class "Default")
      (node (ref "J2") (pin "3") (pinfunction "3_3") (pintype "bidirectional"))
      (node (ref "Q24") (pin "D") (pinfunction "D_D") (pintype "passive"))
      (node (ref "R32") (pin "1") (pinfunction "1_1") (pintype "passive"))
    )
    (net (code "140") (name "P1_A0") (class "Default")
      (node (ref "J4") (pin "5") (pinfunction "5_5") (pintype "bidirectional"))
      (node (ref "Q69") (pin "D") (pinfunction "D_D") (pintype "passive"))
      (node (ref "R85") (pin "1") (pinfunction "1_1") (pintype "passive"))
    )
    (net (code "141") (name "P1_A1") (class "Default")
      (node (ref "J4") (pin "6") (pinfunction "6_6") (pintype "bidirectional"))
      (node (ref "Q70") (pin "D") (pinfunction "D_D") (pintype "passive"))
      (node (ref "R86") (pin "1") (pinfunction "1_1") (pintype "passive"))
    )
    (net (code "142") (name "P1_A2") (class "Default")
      (node (ref "J4") (pin "7") (pinfunction "7_7") (pintype "bidirectional"))
      (node (ref "Q71") (pin "D") (pinfunction "D_D") (pintype "passive"))
      (node (ref "R87") (pin "1") (pinfunction "1_1") (pintype "passive"))
    )
    (net (code "143") (name "P1_A3") (class "Default")
      (node (ref "J4") (pin "8") (pinfunction "8_8") (pintype "bidirectional"))
      (node (ref "Q72") (pin "D") (pinfunction "D_D") (pintype "passive"))
      (node (ref "R88") (pin "1") (pinfunction "1_1") (pintype "passive"))
    )
    (net (code "144") (name "P1_A4") (class "Default")
      (node (ref "J4") (pin "9") (pinfunction "9_9") (pintype "bidirectional"))
      (node (ref "Q73") (pin "D") (pinfunction "D_D") (pintype "passive"))
      (node (ref "R89") (pin "1") (pinfunction "1_1") (pintype "passive"))
    )
    (net (code "145") (name "P1_A5") (class "Default")
      (node (ref "J4") (pin "10") (pinfunction "10_10") (pintype "bidirectional"))
      (node (ref "Q74") (pin "D") (pinfunction "D_D") (pintype "passive"))
      (node (ref "R90") (pin "1") (pinfunction "1_1") (pintype "passive"))
    )
    (net (code "146") (name "P1_A6") (class "Default")
      (node (ref "J4") (pin "11") (pinfunction "11_11") (pintype "bidirectional"))
      (node (ref "Q75") (pin "D") (pinfunction "D_D") (pintype "passive"))
      (node (ref "R91") (pin "1") (pinfunction "1_1") (pintype "passive"))
    )
    (net (code "147") (name "P1_A7") (class "Default")
      (node (ref "J4") (pin "12") (pinfunction "12_12") (pintype "bidirectional"))
      (node (ref "Q76") (pin "D") (pinfunction "D_D") (pintype "passive"))
      (node (ref "R92") (pin "1") (pinfunction "1_1") (pintype "passive"))
    )
    (net (code "148") (name "P1_A8") (class "Default")
      (node (ref "J4") (pin "13") (pinfunction "13_13") (pintype "bidirectional"))
      (node (ref "Q77") (pin "D") (pinfunction "D_D") (pintype "passive"))
      (node (ref "R93") (pin "1") (pinfunction "1_1") (pintype "passive"))
    )
    (net (code "149") (name "P1_A9") (class "Default")
      (node (ref "J4") (pin "14") (pinfunction "14_14") (pintype "bidirectional"))
      (node (ref "Q78") (pin "D") (pinfunction "D_D") (pintype "passive"))
      (node (ref "R94") (pin "1") (pinfunction "1_1") (pintype "passive"))
    )
    (net (code "150") (name "P1_A10") (class "Default")
      (node (ref "J4") (pin "15") (pinfunction "15_15") (pintype "bidirectional"))
      (node (ref "Q79") (pin "D") (pinfunction "D_D") (pintype "passive"))
      (node (ref "R95") (pin "1") (pinfunction "1_1") (pintype "passive"))
    )
    (net (code "151") (name "P1_A11") (class "Default")
      (node (ref "J4") (pin "16") (pinfunction "16_16") (pintype "bidirectional"))
      (node (ref "Q80") (pin "D") (pinfunction "D_D") (pintype "passive"))
      (node (ref "R96") (pin "1") (pinfunction "1_1") (pintype "passive"))
    )
    (net (code "152") (name "P1_A12") (class "Default")
      (node (ref "J4") (pin "17") (pinfunction "17_17") (pintype "bidirectional"))
      (node (ref "Q81") (pin "D") (pinfunction "D_D") (pintype "passive"))
      (node (ref "R97") (pin "1") (pinfunction "1_1") (pintype "passive"))
    )
    (net (code "153") (name "P1_A13") (class "Default")
      (node (ref "J4") (pin "18") (pinfunction "18_18") (pintype "bidirectional"))
      (node (ref "Q82") (pin "D") (pinfunction "D_D") (pintype "passive"))
      (node (ref "R98") (pin "1") (pinfunction "1_1") (pintype "passive"))
    )
    (net (code "154") (name "P1_A14") (class "Default")
      (node (ref "J4") (pin "19") (pinfunction "19_19") (pintype "bidirectional"))
      (node (ref "Q83") (pin "D") (pinfunction "D_D") (pintype "passive"))
      (node (ref "R99") (pin "1") (pinfunction "1_1") (pintype "passive"))
    )
    (net (code "155") (name "P1_A15") (class "Default")
      (node (ref "J4") (pin "20") (pinfunction "20_20") (pintype "bidirectional"))
      (node (ref "Q84") (pin "D") (pinfunction "D_D") (pintype "passive"))
      (node (ref "R100") (pin "1") (pinfunction "1_1") (pintype "passive"))
    )
    (net (code "156") (name "P1_CS") (class "Default")
      (node (ref "Q244") (pin "D") (pinfunction "D_D") (pintype "passive"))
      (node (ref "Q59") (pin "G") (pinfunction "G_G") (pintype "passive"))
      (node (ref "R248") (pin "1") (pinfunction "1_1") (pintype "passive"))
    )
    (net (code "157") (name "P1_CS_N") (class "Default")
      (node (ref "J4") (pin "1") (pinfunction "1_1") (pintype "bidirectional"))
      (node (ref "Q59") (pin "D") (pinfunction "D_D") (pintype "passive"))
      (node (ref "R75") (pin "1") (pinfunction "1_1") (pintype "passive"))
    )
    (net (code "158") (name "P1_RD0") (class "Default")
      (node (ref "J3") (pin "2") (pinfunction "2_2") (pintype "bidirectional"))
      (node (ref "Q43") (pin "G") (pinfunction "G_G") (pintype "passive"))
    )
    (net (code "159") (name "P1_RD0_B") (class "Default")
      (node (ref "Q171") (pin "G") (pinfunction "G_G") (pintype "passive"))
      (node (ref "Q44") (pin "D") (pinfunction "D_D") (pintype "passive"))
      (node (ref "R67") (pin "1") (pinfunction "1_1") (pintype "passive"))
    )
    (net (code "160") (name "P1_RD1") (class "Default")
      (node (ref "J3") (pin "3") (pinfunction "3_3") (pintype "bidirectional"))
      (node (ref "Q45") (pin "G") (pinfunction "G_G") (pintype "passive"))
    )
    (net (code "161") (name "P1_RD1_B") (class "Default")
      (node (ref "Q176") (pin "G") (pinfunction "G_G") (pintype "passive"))
      (node (ref "Q46") (pin "D") (pinfunction "D_D") (pintype "passive"))
      (node (ref "R68") (pin "1") (pinfunction "1_1") (pintype "passive"))
    )
    (net (code "162") (name "P1_RD2") (class "Default")
      (node (ref "J3") (pin "4") (pinfunction "4_4") (pintype "bidirectional"))
      (node (ref "Q47") (pin "G") (pinfunction "G_G") (pintype "passive"))
    )
    (net (code "163") (name "P1_RD2_B") (class "Default")
      (node (ref "Q181") (pin "G") (pinfunction "G_G") (pintype "passive"))
      (node (ref "Q48") (pin "D") (pinfunction "D_D") (pintype "passive"))
      (node (ref "R69") (pin "1") (pinfunction "1_1") (pintype "passive"))
    )
    (net (code "164") (name "P1_RD3") (class "Default")
      (node (ref "J3") (pin "5") (pinfunction "5_5") (pintype "bidirectional"))
      (node (ref "Q49") (pin "G") (pinfunction "G_G") (pintype "passive"))
    )
    (net (code "165") (name "P1_RD3_B") (class "Default")
      (node (ref "Q186") (pin "G") (pinfunction "G_G") (pintype "passive"))
      (node (ref "Q50") (pin "D") (pinfunction "D_D") (pintype "passive"))
      (node (ref "R70") (pin "1") (pinfunction "1_1") (pintype "passive"))
    )
    (net (code "166") (name "P1_RD4") (class "Default")
      (node (ref "J3") (pin "6") (pinfunction "6_6") (pintype "bidirectional"))
      (node (ref "Q51") (pin "G") (pinfunction "G_G") (pintype "passive"))
    )
    (net (code "167") (name "P1_RD4_B") (class "Default")
      (node (ref "Q191") (pin "G") (pinfunction "G_G") (pintype "passive"))
      (node (ref "Q52") (pin "D") (pinfunction "D_D") (pintype "passive"))
      (node (ref "R71") (pin "1") (pinfunction "1_1") (pintype "passive"))
    )
    (net (code "168") (name "P1_RD5") (class "Default")
      (node (ref "J3") (pin "7") (pinfunction "7_7") (pintype "bidirectional"))
      (node (ref "Q53") (pin "G") (pinfunction "G_G") (pintype "passive"))
    )
    (net (code "169") (name "P1_RD5_B") (class "Default")
      (node (ref "Q196") (pin "G") (pinfunction "G_G") (pintype "passive"))
      (node (ref "Q54") (pin "D") (pinfunction "D_D") (pintype "passive"))
      (node (ref "R72") (pin "1") (pinfunction "1_1") (pintype "passive"))
    )
    (net (code "170") (name "P1_RD6") (class "Default")
      (node (ref "J3") (pin "8") (pinfunction "8_8") (pintype "bidirectional"))
      (node (ref "Q55") (pin "G") (pinfunction "G_G") (pintype "passive"))
    )
    (net (code "171") (name "P1_RD6_B") (class "Default")
      (node (ref "Q201") (pin "G") (pinfunction "G_G") (pintype "passive"))
      (node (ref "Q56") (pin "D") (pinfunction "D_D") (pintype "passive"))
      (node (ref "R73") (pin "1") (pinfunction "1_1") (pintype "passive"))
    )
    (net (code "172") (name "P1_RD7") (class "Default")
      (node (ref "J3") (pin "9") (pinfunction "9_9") (pintype "bidirectional"))
      (node (ref "Q57") (pin "G") (pinfunction "G_G") (pintype "passive"))
    )
    (net (code "173") (name "P1_RD7_B") (class "Default")
      (node (ref "Q206") (pin "G") (pinfunction "G_G") (pintype "passive"))
      (node (ref "Q58") (pin "D") (pinfunction "D_D") (pintype "passive"))
      (node (ref "R74") (pin "1") (pinfunction "1_1") (pintype "passive"))
    )
    (net (code "174") (name "P1_WD0") (class "Default")
      (node (ref "J3") (pin "12") (pinfunction "12_12") (pintype "bidirectional"))
      (node (ref "Q61") (pin "D") (pinfunction "D_D") (pintype "passive"))
      (node (ref "R77") (pin "1") (pinfunction "1_1") (pintype "passive"))
    )
    (net (code "175") (name "P1_WD1") (class "Default")
      (node (ref "J3") (pin "13") (pinfunction "13_13") (pintype "bidirectional"))
      (node (ref "Q62") (pin "D") (pinfunction "D_D") (pintype "passive"))
      (node (ref "R78") (pin "1") (pinfunction "1_1") (pintype "passive"))
    )
    (net (code "176") (name "P1_WD2") (class "Default")
      (node (ref "J3") (pin "14") (pinfunction "14_14") (pintype "bidirectional"))
      (node (ref "Q63") (pin "D") (pinfunction "D_D") (pintype "passive"))
      (node (ref "R79") (pin "1") (pinfunction "1_1") (pintype "passive"))
    )
    (net (code "177") (name "P1_WD3") (class "Default")
      (node (ref "J3") (pin "15") (pinfunction "15_15") (pintype "bidirectional"))
      (node (ref "Q64") (pin "D") (pinfunction "D_D") (pintype "passive"))
      (node (ref "R80") (pin "1") (pinfunction "1_1") (pintype "passive"))
    )
    (net (code "178") (name "P1_WD4") (class "Default")
      (node (ref "J3") (pin "16") (pinfunction "16_16") (pintype "bidirectional"))
      (node (ref "Q65") (pin "D") (pinfunction "D_D") (pintype "passive"))
      (node (ref "R81") (pin "1") (pinfunction "1_1") (pintype "passive"))
    )
    (net (code "179") (name "P1_WD5") (class "Default")
      (node (ref "J3") (pin "17") (pinfunction "17_17") (pintype "bidirectional"))
      (node (ref "Q66") (pin "D") (pinfunction "D_D") (pintype "passive"))
      (node (ref "R82") (pin "1") (pinfunction "1_1") (pintype "passive"))
    )
    (net (code "180") (name "P1_WD6") (class "Default")
      (node (ref "J3") (pin "18") (pinfunction "18_18") (pintype "bidirectional"))
      (node (ref "Q67") (pin "D") (pinfunction "D_D") (pintype "passive"))
      (node (ref "R83") (pin "1") (pinfunction "1_1") (pintype "passive"))
    )
    (net (code "181") (name "P1_WD7") (class "Default")
      (node (ref "J3") (pin "19") (pinfunction "19_19") (pintype "bidirectional"))
      (node (ref "Q68") (pin "D") (pinfunction "D_D") (pintype "passive"))
      (node (ref "R84") (pin "1") (pinfunction "1_1") (pintype "passive"))
    )
    (net (code "182") (name "P1_WE_N") (class "Default")
      (node (ref "J4") (pin "3") (pinfunction "3_3") (pintype "bidirectional"))
      (node (ref "Q60") (pin "D") (pinfunction "D_D") (pintype "passive"))
      (node (ref "R76") (pin "1") (pinfunction "1_1") (pintype "passive"))
    )
    (net (code "183") (name "RD0") (class "Default")
      (node (ref "J9") (pin "2") (pinfunction "2_2") (pintype "bidirectional"))
      (node (ref "Q170") (pin "D") (pinfunction "D_D") (pintype "passive"))
      (node (ref "R257") (pin "1") (pinfunction "1_1") (pintype "passive"))
    )
    (net (code "184") (name "RD1") (class "Default")
      (node (ref "J9") (pin "3") (pinfunction "3_3") (pintype "bidirectional"))
      (node (ref "Q175") (pin "D") (pinfunction "D_D") (pintype "passive"))
      (node (ref "R258") (pin "1") (pinfunction "1_1") (pintype "passive"))
    )
    (net (code "185") (name "RD2") (class "Default")
      (node (ref "J9") (pin "4") (pinfunction "4_4") (pintype "bidirectional"))
      (node (ref "Q180") (pin "D") (pinfunction "D_D") (pintype "passive"))
      (node (ref "R259") (pin "1") (pinfunction "1_1") (pintype "passive"))
    )
    (net (code "186") (name "RD3") (class "Default")
      (node (ref "J9") (pin "5") (pinfunction "5_5") (pintype "bidirectional"))
      (node (ref "Q185") (pin "D") (pinfunction "D_D") (pintype "passive"))
      (node (ref "R260") (pin "1") (pinfunction "1_1") (pintype "passive"))
    )
    (net (code "187") (name "RD4") (class "Default")
      (node (ref "J9") (pin "6") (pinfunction "6_6") (pintype "bidirectional"))
      (node (ref "Q190") (pin "D") (pinfunction "D_D") (pintype "passive"))
      (node (ref "R253") (pin "1") (pinfunction "1_1") (pintype "passive"))
    )
    (net (code "188") (name "RD5") (class "Default")
      (node (ref "J9") (pin "7") (pinfunction "7_7") (pintype "bidirectional"))
      (node (ref "Q195") (pin "D") (pinfunction "D_D") (pintype "passive"))
      (node (ref "R254") (pin "1") (pinfunction "1_1") (pintype "passive"))
    )
    (net (code "189") (name "RD6") (class "Default")
      (node (ref "J9") (pin "8") (pinfunction "8_8") (pintype "bidirectional"))
      (node (ref "Q200") (pin "D") (pinfunction "D_D") (pintype "passive"))
      (node (ref "R255") (pin "1") (pinfunction "1_1") (pintype "passive"))
    )
    (net (code "190") (name "RD7") (class "Default")
      (node (ref "J9") (pin "9") (pinfunction "9_9") (pintype "bidirectional"))
      (node (ref "Q205") (pin "D") (pinfunction "D_D") (pintype "passive"))
      (node (ref "R256") (pin "1") (pinfunction "1_1") (pintype "passive"))
    )
    (net (code "191") (name "SEL_A0") (class "Default")
      (node (ref "Q233") (pin "D") (pinfunction "D_D") (pintype "passive"))
      (node (ref "Q241") (pin "G") (pinfunction "G_G") (pintype "passive"))
      (node (ref "R241") (pin "1") (pinfunction "1_1") (pintype "passive"))
    )
    (net (code "192") (name "SEL_A0_N") (class "Default")
      (node (ref "Q233") (pin "G") (pinfunction "G_G") (pintype "passive"))
      (node (ref "Q237") (pin "G") (pinfunction "G_G") (pintype "passive"))
      (node (ref "TP1") (pin "P$1") (pinfunction "P$1_P$1") (pintype "bidirectional"))
    )
    (net (code "193") (name "WD0") (class "Default")
      (node (ref "J9") (pin "12") (pinfunction "12_12") (pintype "bidirectional"))
      (node (ref "Q209") (pin "G") (pinfunction "G_G") (pintype "passive"))
    )
    (net (code "194") (name "WD0_N") (class "Default")
      (node (ref "Q209") (pin "D") (pinfunction "D_D") (pintype "passive"))
      (node (ref "Q25") (pin "G") (pinfunction "G_G") (pintype "passive"))
      (node (ref "Q61") (pin "G") (pinfunction "G_G") (pintype "passive"))
      (node (ref "R217") (pin "1") (pinfunction "1_1") (pintype "passive"))
    )
    (net (code "195") (name "WD1") (class "Default")
      (node (ref "J9") (pin "13") (pinfunction "13_13") (pintype "bidirectional"))
      (node (ref "Q210") (pin "G") (pinfunction "G_G") (pintype "passive"))
    )
    (net (code "196") (name "WD1_N") (class "Default")
      (node (ref "Q210") (pin "D") (pinfunction "D_D") (pintype "passive"))
      (node (ref "Q26") (pin "G") (pinfunction "G_G") (pintype "passive"))
      (node (ref "Q62") (pin "G") (pinfunction "G_G") (pintype "passive"))
      (node (ref "R218") (pin "1") (pinfunction "1_1") (pintype "passive"))
    )
    (net (code "197") (name "WD2") (class "Default")
      (node (ref "J9") (pin "14") (pinfunction "14_14") (pintype "bidirectional"))
      (node (ref "Q211") (pin "G") (pinfunction "G_G") (pintype "passive"))
    )
    (net (code "198") (name "WD2_N") (class "Default")
      (node (ref "Q211") (pin "D") (pinfunction "D_D") (pintype "passive"))
      (node (ref "Q27") (pin "G") (pinfunction "G_G") (pintype "passive"))
      (node (ref "Q63") (pin "G") (pinfunction "G_G") (pintype "passive"))
      (node (ref "R219") (pin "1") (pinfunction "1_1") (pintype "passive"))
    )
    (net (code "199") (name "WD3") (class "Default")
      (node (ref "J9") (pin "15") (pinfunction "15_15") (pintype "bidirectional"))
      (node (ref "Q212") (pin "G") (pinfunction "G_G") (pintype "passive"))
    )
    (net (code "200") (name "WD3_N") (class "Default")
      (node (ref "Q212") (pin "D") (pinfunction "D_D") (pintype "passive"))
      (node (ref "Q28") (pin "G") (pinfunction "G_G") (pintype "passive"))
      (node (ref "Q64") (pin "G") (pinfunction "G_G") (pintype "passive"))
      (node (ref "R220") (pin "1") (pinfunction "1_1") (pintype "passive"))
    )
    (net (code "201") (name "WD4") (class "Default")
      (node (ref "J9") (pin "16") (pinfunction "16_16") (pintype "bidirectional"))
      (node (ref "Q213") (pin "G") (pinfunction "G_G") (pintype "passive"))
    )
    (net (code "202") (name "WD4_N") (class "Default")
      (node (ref "Q213") (pin "D") (pinfunction "D_D") (pintype "passive"))
      (node (ref "Q29") (pin "G") (pinfunction "G_G") (pintype "passive"))
      (node (ref "Q65") (pin "G") (pinfunction "G_G") (pintype "passive"))
      (node (ref "R221") (pin "1") (pinfunction "1_1") (pintype "passive"))
    )
    (net (code "203") (name "WD5") (class "Default")
      (node (ref "J9") (pin "17") (pinfunction "17_17") (pintype "bidirectional"))
      (node (ref "Q214") (pin "G") (pinfunction "G_G") (pintype "passive"))
    )
    (net (code "204") (name "WD5_N") (class "Default")
      (node (ref "Q214") (pin "D") (pinfunction "D_D") (pintype "passive"))
      (node (ref "Q30") (pin "G") (pinfunction "G_G") (pintype "passive"))
      (node (ref "Q66") (pin "G") (pinfunction "G_G") (pintype "passive"))
      (node (ref "R222") (pin "1") (pinfunction "1_1") (pintype "passive"))
    )
    (net (code "205") (name "WD6") (class "Default")
      (node (ref "J9") (pin "18") (pinfunction "18_18") (pintype "bidirectional"))
      (node (ref "Q215") (pin "G") (pinfunction "G_G") (pintype "passive"))
    )
    (net (code "206") (name "WD6_N") (class "Default")
      (node (ref "Q215") (pin "D") (pinfunction "D_D") (pintype "passive"))
      (node (ref "Q31") (pin "G") (pinfunction "G_G") (pintype "passive"))
      (node (ref "Q67") (pin "G") (pinfunction "G_G") (pintype "passive"))
      (node (ref "R223") (pin "1") (pinfunction "1_1") (pintype "passive"))
    )
    (net (code "207") (name "WD7") (class "Default")
      (node (ref "J9") (pin "19") (pinfunction "19_19") (pintype "bidirectional"))
      (node (ref "Q216") (pin "G") (pinfunction "G_G") (pintype "passive"))
    )
    (net (code "208") (name "WD7_N") (class "Default")
      (node (ref "Q216") (pin "D") (pinfunction "D_D") (pintype "passive"))
      (node (ref "Q32") (pin "G") (pinfunction "G_G") (pintype "passive"))
      (node (ref "Q68") (pin "G") (pinfunction "G_G") (pintype "passive"))
      (node (ref "R224") (pin "1") (pinfunction "1_1") (pintype "passive"))
    )
    (net (code "209") (name "WE") (class "Default")
      (node (ref "Q236") (pin "D") (pinfunction "D_D") (pintype "passive"))
      (node (ref "Q24") (pin "G") (pinfunction "G_G") (pintype "passive"))
      (node (ref "Q60") (pin "G") (pinfunction "G_G") (pintype "passive"))
      (node (ref "R244") (pin "1") (pinfunction "1_1") (pintype "passive"))
    )
    (net (code "210") (name "WE_N") (class "Default")
      (node (ref "J10") (pin "3") (pinfunction "3_3") (pintype "bidirectional"))
      (node (ref "Q236") (pin "G") (pinfunction "G_G") (pintype "passive"))
    )
  )
)
